# 5409057.net
KiCad netlist of a schematic drawn in EAGLE
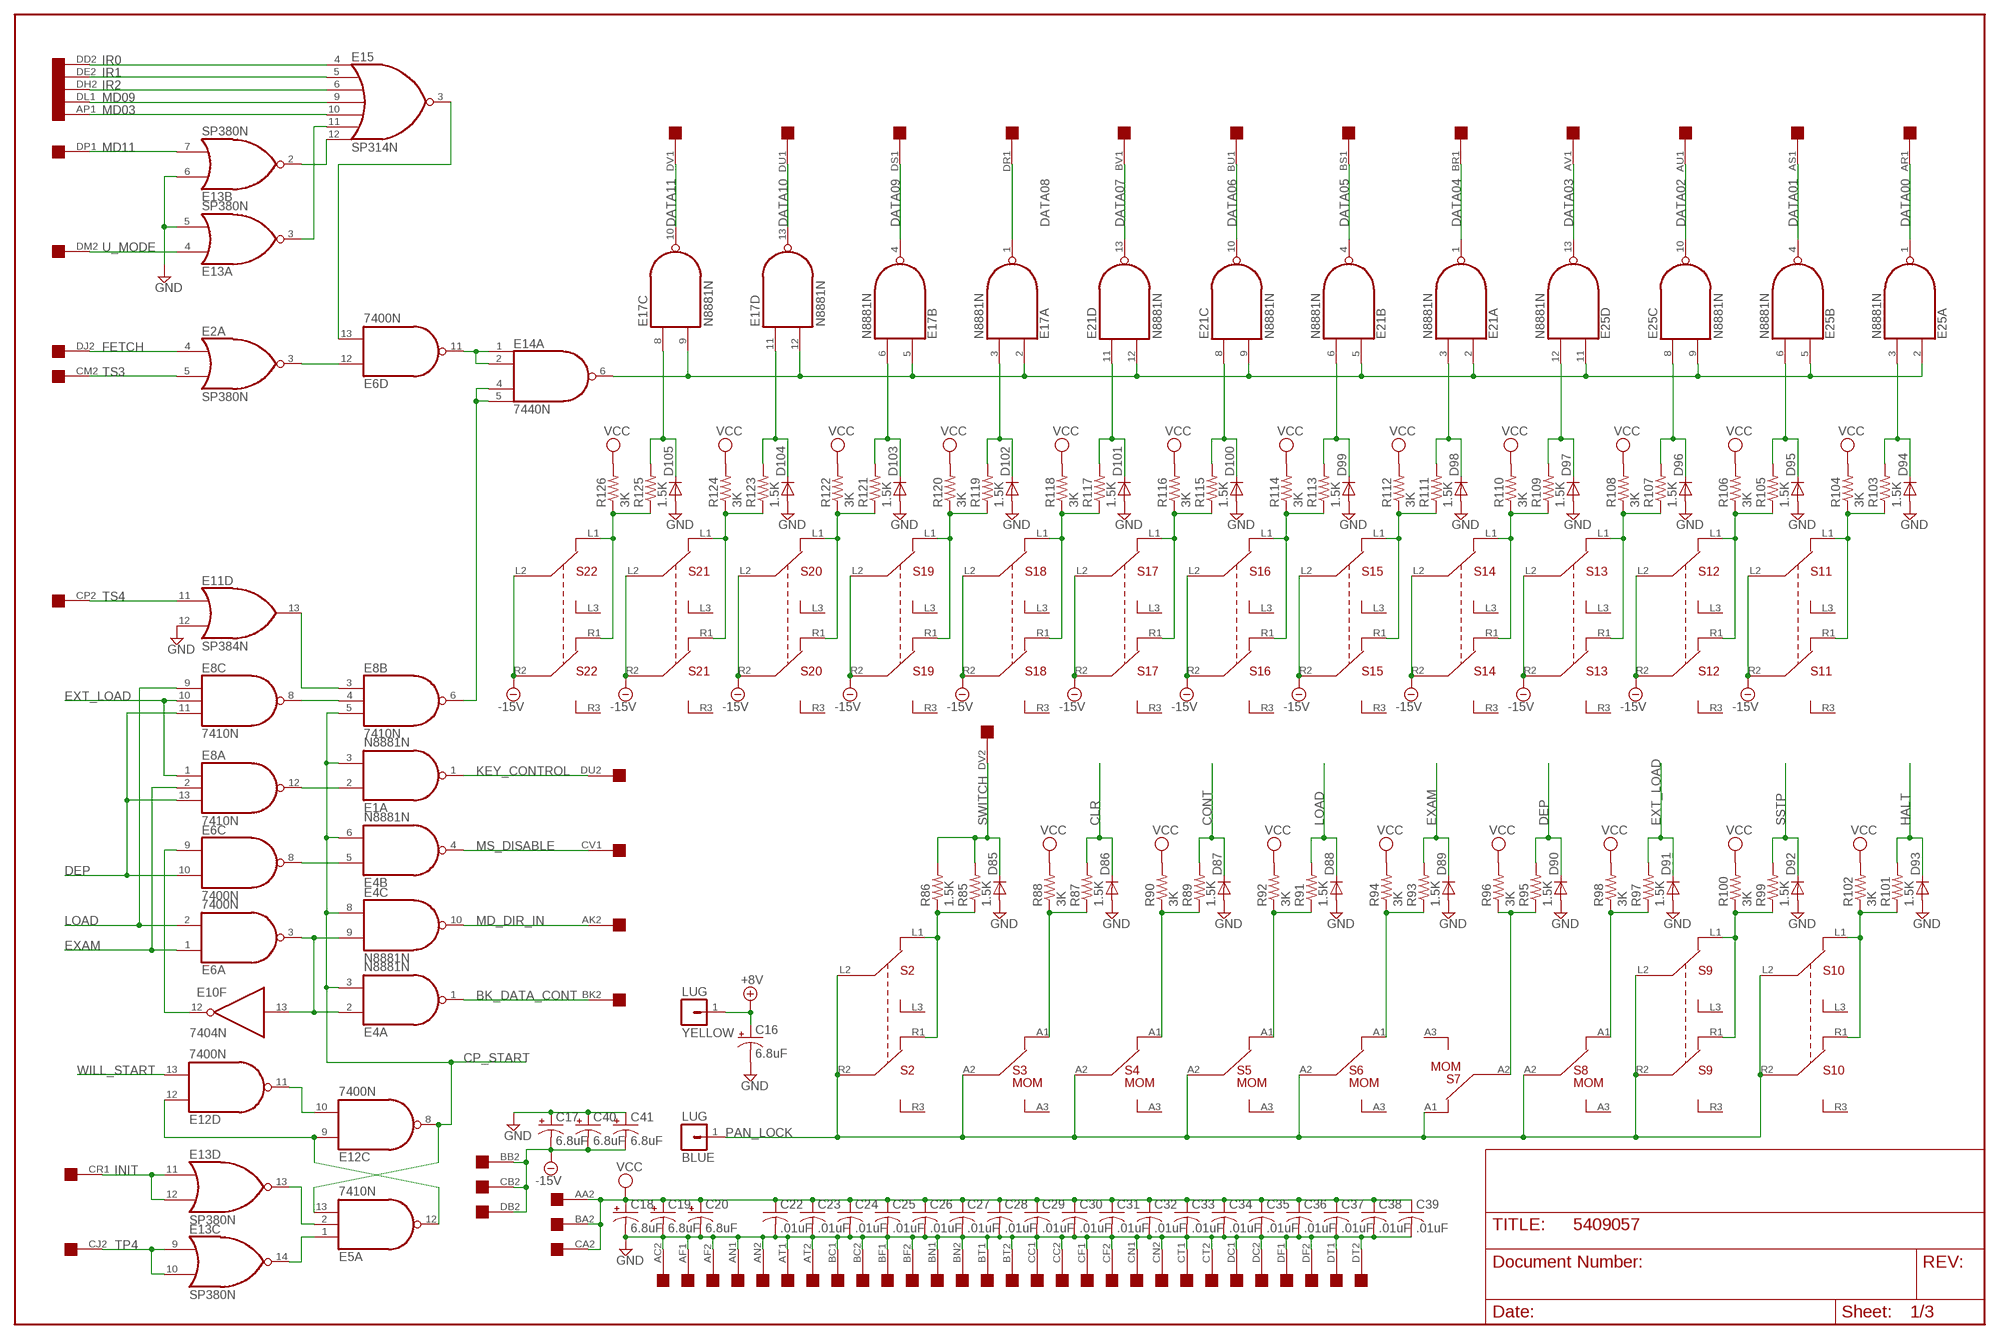
[diagram p0: schematic, sheet 1]
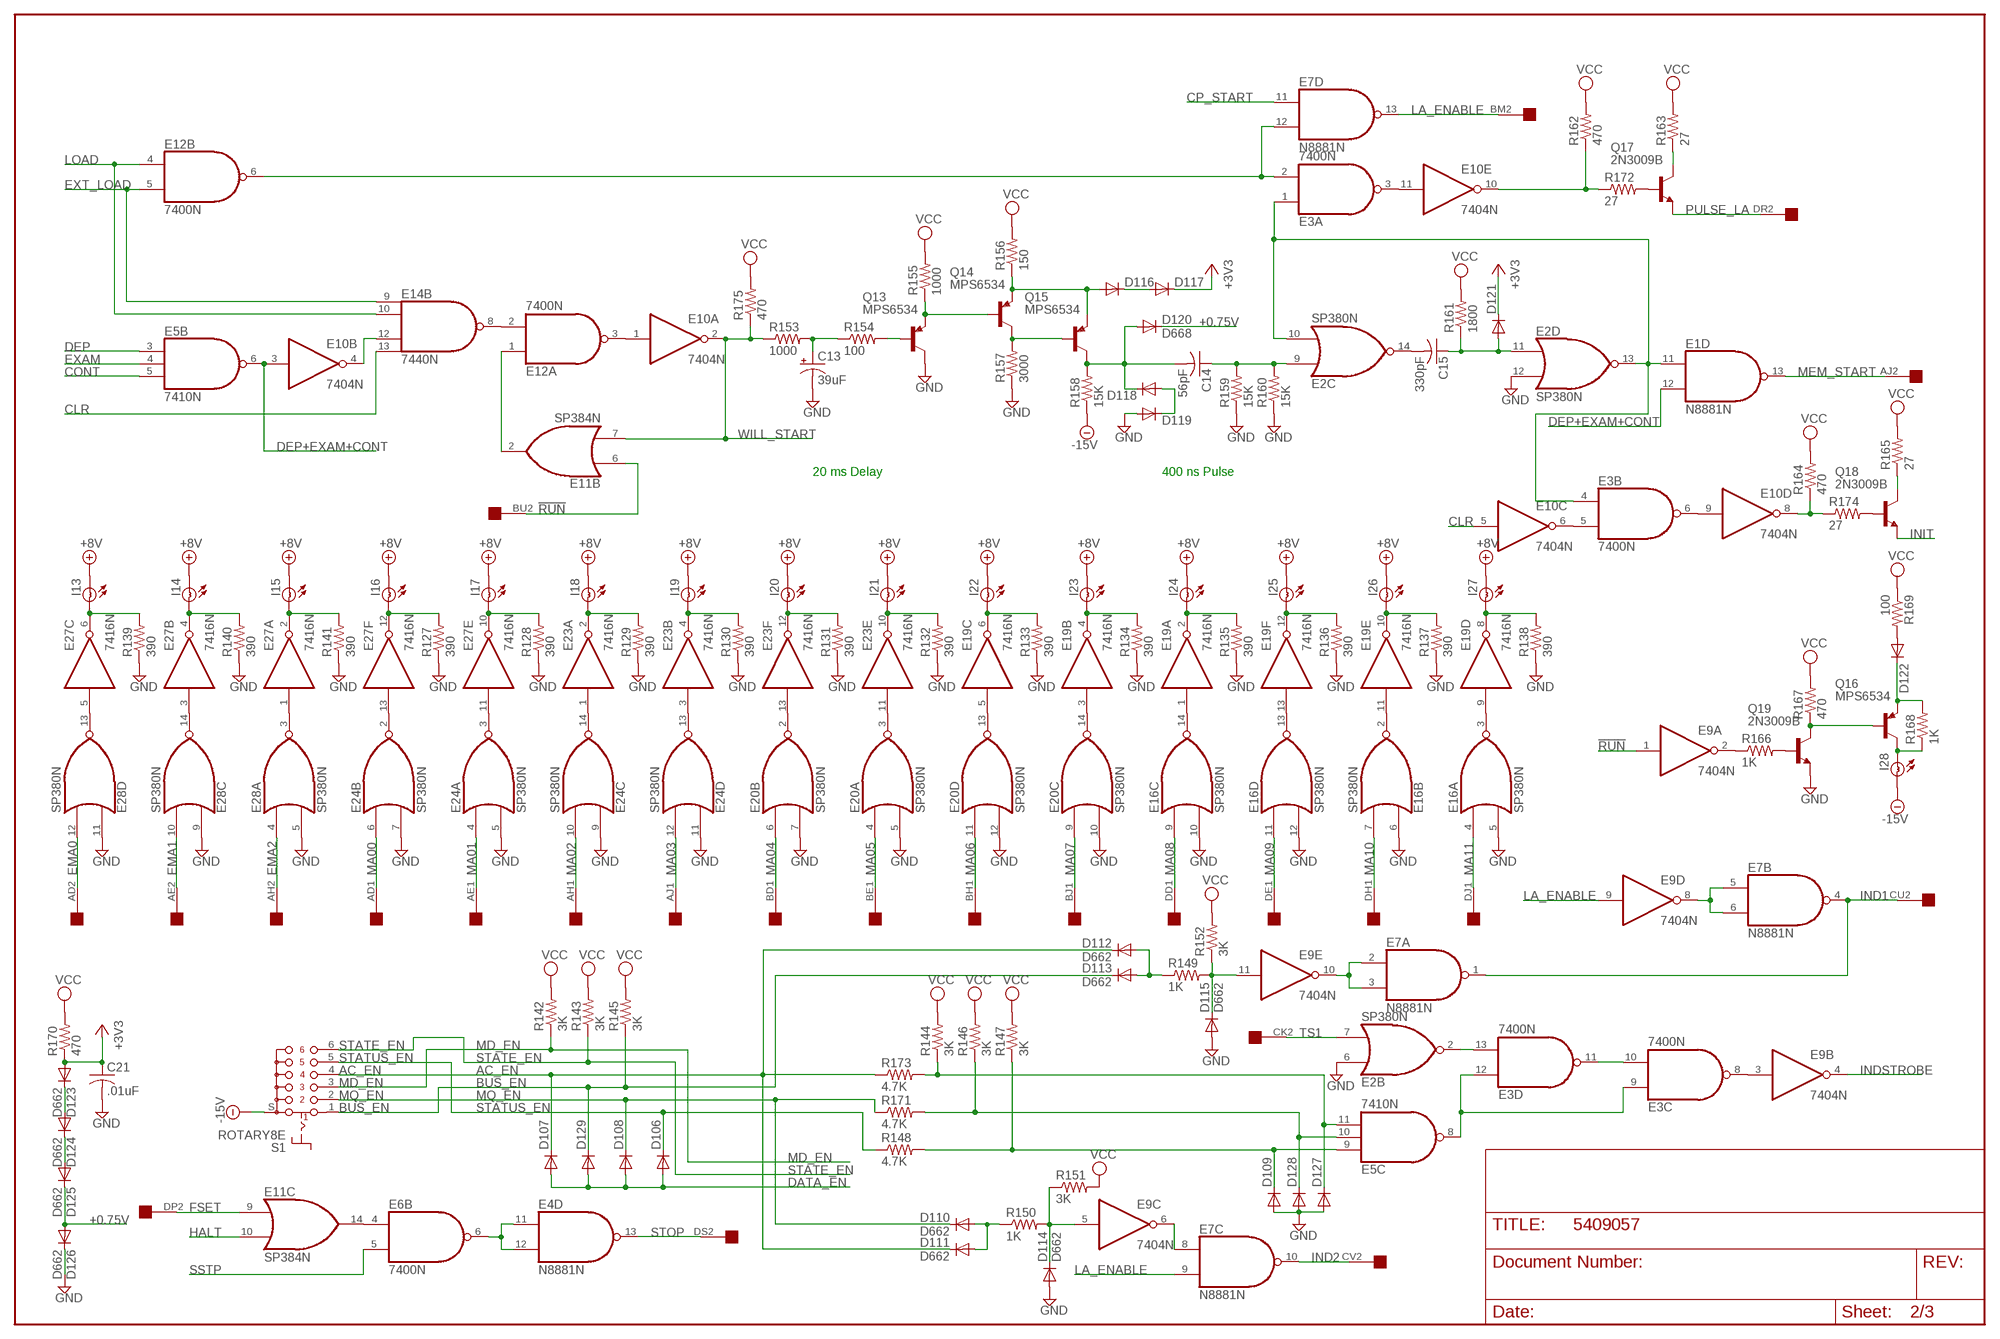
[diagram p1: schematic, sheet 2]
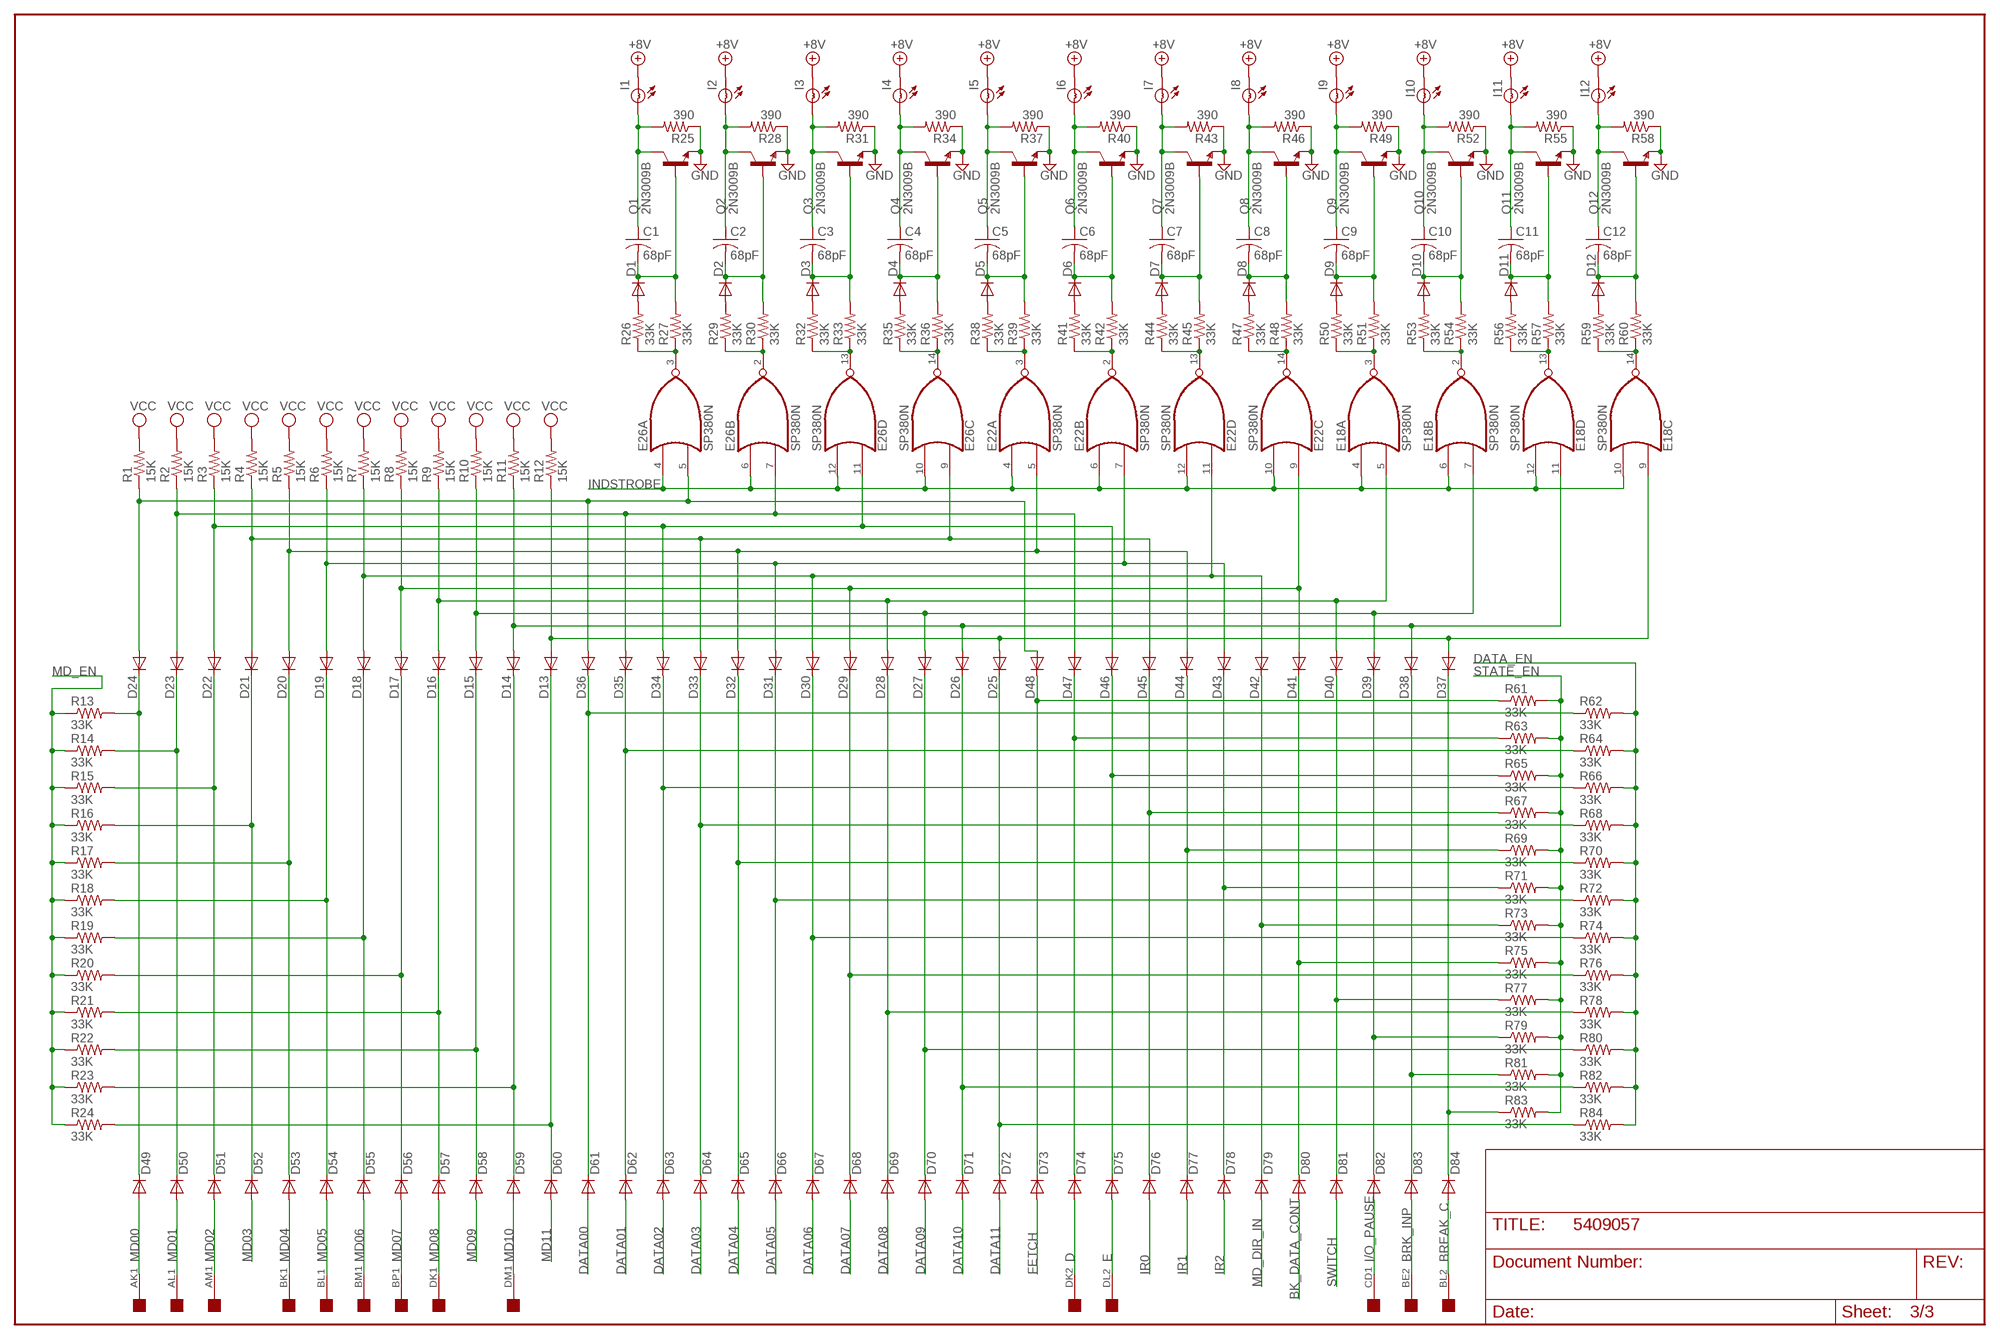
[diagram p2: schematic, sheet 3]

(export (version "E")
  (design (tool "Eeschema 10.0.6"))
  (components
    (comp (ref "C1")
      (value "68pF")
      (footprint "eagle-import:C050-025X075")
      (libsource (lib "eagle-import") (part "C-US050-025X075"))
    )
    (comp (ref "C2")
      (value "68pF")
      (footprint "eagle-import:C050-025X075")
      (libsource (lib "eagle-import") (part "C-US050-025X075"))
    )
    (comp (ref "C3")
      (value "68pF")
      (footprint "eagle-import:C050-025X075")
      (libsource (lib "eagle-import") (part "C-US050-025X075"))
    )
    (comp (ref "C4")
      (value "68pF")
      (footprint "eagle-import:C050-025X075")
      (libsource (lib "eagle-import") (part "C-US050-025X075"))
    )
    (comp (ref "C5")
      (value "68pF")
      (footprint "eagle-import:C050-025X075")
      (libsource (lib "eagle-import") (part "C-US050-025X075"))
    )
    (comp (ref "C6")
      (value "68pF")
      (footprint "eagle-import:C050-025X075")
      (libsource (lib "eagle-import") (part "C-US050-025X075"))
    )
    (comp (ref "C7")
      (value "68pF")
      (footprint "eagle-import:C050-025X075")
      (libsource (lib "eagle-import") (part "C-US050-025X075"))
    )
    (comp (ref "C8")
      (value "68pF")
      (footprint "eagle-import:C050-025X075")
      (libsource (lib "eagle-import") (part "C-US050-025X075"))
    )
    (comp (ref "C9")
      (value "68pF")
      (footprint "eagle-import:C050-025X075")
      (libsource (lib "eagle-import") (part "C-US050-025X075"))
    )
    (comp (ref "C10")
      (value "68pF")
      (footprint "eagle-import:C050-025X075")
      (libsource (lib "eagle-import") (part "C-US050-025X075"))
    )
    (comp (ref "C11")
      (value "68pF")
      (footprint "eagle-import:C050-025X075")
      (libsource (lib "eagle-import") (part "C-US050-025X075"))
    )
    (comp (ref "C12")
      (value "68pF")
      (footprint "eagle-import:C050-025X075")
      (libsource (lib "eagle-import") (part "C-US050-025X075"))
    )
    (comp (ref "D1")
      (value "1N4148")
      (footprint "eagle-import:DO35-10")
      (libsource (lib "eagle-import") (part "1N4148"))
    )
    (comp (ref "D2")
      (value "1N4148")
      (footprint "eagle-import:DO35-10")
      (libsource (lib "eagle-import") (part "1N4148"))
    )
    (comp (ref "D3")
      (value "1N4148")
      (footprint "eagle-import:DO35-10")
      (libsource (lib "eagle-import") (part "1N4148"))
    )
    (comp (ref "D4")
      (value "1N4148")
      (footprint "eagle-import:DO35-10")
      (libsource (lib "eagle-import") (part "1N4148"))
    )
    (comp (ref "D5")
      (value "1N4148")
      (footprint "eagle-import:DO35-10")
      (libsource (lib "eagle-import") (part "1N4148"))
    )
    (comp (ref "D6")
      (value "1N4148")
      (footprint "eagle-import:DO35-10")
      (libsource (lib "eagle-import") (part "1N4148"))
    )
    (comp (ref "D7")
      (value "1N4148")
      (footprint "eagle-import:DO35-10")
      (libsource (lib "eagle-import") (part "1N4148"))
    )
    (comp (ref "D8")
      (value "1N4148")
      (footprint "eagle-import:DO35-10")
      (libsource (lib "eagle-import") (part "1N4148"))
    )
    (comp (ref "D9")
      (value "1N4148")
      (footprint "eagle-import:DO35-10")
      (libsource (lib "eagle-import") (part "1N4148"))
    )
    (comp (ref "D10")
      (value "1N4148")
      (footprint "eagle-import:DO35-10")
      (libsource (lib "eagle-import") (part "1N4148"))
    )
    (comp (ref "D11")
      (value "1N4148")
      (footprint "eagle-import:DO35-10")
      (libsource (lib "eagle-import") (part "1N4148"))
    )
    (comp (ref "D12")
      (value "1N4148")
      (footprint "eagle-import:DO35-10")
      (libsource (lib "eagle-import") (part "1N4148"))
    )
    (comp (ref "D13")
      (value "1N4148")
      (footprint "eagle-import:DO35-10")
      (libsource (lib "eagle-import") (part "1N4148"))
    )
    (comp (ref "D14")
      (value "1N4148")
      (footprint "eagle-import:DO35-10")
      (libsource (lib "eagle-import") (part "1N4148"))
    )
    (comp (ref "D15")
      (value "1N4148")
      (footprint "eagle-import:DO35-10")
      (libsource (lib "eagle-import") (part "1N4148"))
    )
    (comp (ref "D16")
      (value "1N4148")
      (footprint "eagle-import:DO35-10")
      (libsource (lib "eagle-import") (part "1N4148"))
    )
    (comp (ref "D17")
      (value "1N4148")
      (footprint "eagle-import:DO35-10")
      (libsource (lib "eagle-import") (part "1N4148"))
    )
    (comp (ref "D18")
      (value "1N4148")
      (footprint "eagle-import:DO35-10")
      (libsource (lib "eagle-import") (part "1N4148"))
    )
    (comp (ref "D19")
      (value "1N4148")
      (footprint "eagle-import:DO35-10")
      (libsource (lib "eagle-import") (part "1N4148"))
    )
    (comp (ref "D20")
      (value "1N4148")
      (footprint "eagle-import:DO35-10")
      (libsource (lib "eagle-import") (part "1N4148"))
    )
    (comp (ref "D21")
      (value "1N4148")
      (footprint "eagle-import:DO35-10")
      (libsource (lib "eagle-import") (part "1N4148"))
    )
    (comp (ref "D22")
      (value "1N4148")
      (footprint "eagle-import:DO35-10")
      (libsource (lib "eagle-import") (part "1N4148"))
    )
    (comp (ref "D23")
      (value "1N4148")
      (footprint "eagle-import:DO35-10")
      (libsource (lib "eagle-import") (part "1N4148"))
    )
    (comp (ref "D24")
      (value "1N4148")
      (footprint "eagle-import:DO35-10")
      (libsource (lib "eagle-import") (part "1N4148"))
    )
    (comp (ref "D25")
      (value "1N4148")
      (footprint "eagle-import:DO35-10")
      (libsource (lib "eagle-import") (part "1N4148"))
    )
    (comp (ref "D26")
      (value "1N4148")
      (footprint "eagle-import:DO35-10")
      (libsource (lib "eagle-import") (part "1N4148"))
    )
    (comp (ref "D27")
      (value "1N4148")
      (footprint "eagle-import:DO35-10")
      (libsource (lib "eagle-import") (part "1N4148"))
    )
    (comp (ref "D28")
      (value "1N4148")
      (footprint "eagle-import:DO35-10")
      (libsource (lib "eagle-import") (part "1N4148"))
    )
    (comp (ref "D29")
      (value "1N4148")
      (footprint "eagle-import:DO35-10")
      (libsource (lib "eagle-import") (part "1N4148"))
    )
    (comp (ref "D30")
      (value "1N4148")
      (footprint "eagle-import:DO35-10")
      (libsource (lib "eagle-import") (part "1N4148"))
    )
    (comp (ref "D31")
      (value "1N4148")
      (footprint "eagle-import:DO35-10")
      (libsource (lib "eagle-import") (part "1N4148"))
    )
    (comp (ref "D32")
      (value "1N4148")
      (footprint "eagle-import:DO35-10")
      (libsource (lib "eagle-import") (part "1N4148"))
    )
    (comp (ref "D33")
      (value "1N4148")
      (footprint "eagle-import:DO35-10")
      (libsource (lib "eagle-import") (part "1N4148"))
    )
    (comp (ref "D34")
      (value "1N4148")
      (footprint "eagle-import:DO35-10")
      (libsource (lib "eagle-import") (part "1N4148"))
    )
    (comp (ref "D35")
      (value "1N4148")
      (footprint "eagle-import:DO35-10")
      (libsource (lib "eagle-import") (part "1N4148"))
    )
    (comp (ref "D36")
      (value "1N4148")
      (footprint "eagle-import:DO35-10")
      (libsource (lib "eagle-import") (part "1N4148"))
    )
    (comp (ref "D37")
      (value "1N4148")
      (footprint "eagle-import:DO35-10")
      (libsource (lib "eagle-import") (part "1N4148"))
    )
    (comp (ref "D38")
      (value "1N4148")
      (footprint "eagle-import:DO35-10")
      (libsource (lib "eagle-import") (part "1N4148"))
    )
    (comp (ref "D39")
      (value "1N4148")
      (footprint "eagle-import:DO35-10")
      (libsource (lib "eagle-import") (part "1N4148"))
    )
    (comp (ref "D40")
      (value "1N4148")
      (footprint "eagle-import:DO35-10")
      (libsource (lib "eagle-import") (part "1N4148"))
    )
    (comp (ref "D41")
      (value "1N4148")
      (footprint "eagle-import:DO35-10")
      (libsource (lib "eagle-import") (part "1N4148"))
    )
    (comp (ref "D42")
      (value "1N4148")
      (footprint "eagle-import:DO35-10")
      (libsource (lib "eagle-import") (part "1N4148"))
    )
    (comp (ref "D43")
      (value "1N4148")
      (footprint "eagle-import:DO35-10")
      (libsource (lib "eagle-import") (part "1N4148"))
    )
    (comp (ref "D44")
      (value "1N4148")
      (footprint "eagle-import:DO35-10")
      (libsource (lib "eagle-import") (part "1N4148"))
    )
    (comp (ref "D45")
      (value "1N4148")
      (footprint "eagle-import:DO35-10")
      (libsource (lib "eagle-import") (part "1N4148"))
    )
    (comp (ref "D46")
      (value "1N4148")
      (footprint "eagle-import:DO35-10")
      (libsource (lib "eagle-import") (part "1N4148"))
    )
    (comp (ref "D47")
      (value "1N4148")
      (footprint "eagle-import:DO35-10")
      (libsource (lib "eagle-import") (part "1N4148"))
    )
    (comp (ref "D48")
      (value "1N4148")
      (footprint "eagle-import:DO35-10")
      (libsource (lib "eagle-import") (part "1N4148"))
    )
    (comp (ref "D49")
      (value "1N4148")
      (footprint "eagle-import:DO35-10")
      (libsource (lib "eagle-import") (part "1N4148"))
    )
    (comp (ref "D50")
      (value "1N4148")
      (footprint "eagle-import:DO35-10")
      (libsource (lib "eagle-import") (part "1N4148"))
    )
    (comp (ref "D51")
      (value "1N4148")
      (footprint "eagle-import:DO35-10")
      (libsource (lib "eagle-import") (part "1N4148"))
    )
    (comp (ref "D52")
      (value "1N4148")
      (footprint "eagle-import:DO35-10")
      (libsource (lib "eagle-import") (part "1N4148"))
    )
    (comp (ref "D53")
      (value "1N4148")
      (footprint "eagle-import:DO35-10")
      (libsource (lib "eagle-import") (part "1N4148"))
    )
    (comp (ref "D54")
      (value "1N4148")
      (footprint "eagle-import:DO35-10")
      (libsource (lib "eagle-import") (part "1N4148"))
    )
    (comp (ref "D55")
      (value "1N4148")
      (footprint "eagle-import:DO35-10")
      (libsource (lib "eagle-import") (part "1N4148"))
    )
    (comp (ref "D56")
      (value "1N4148")
      (footprint "eagle-import:DO35-10")
      (libsource (lib "eagle-import") (part "1N4148"))
    )
    (comp (ref "D57")
      (value "1N4148")
      (footprint "eagle-import:DO35-10")
      (libsource (lib "eagle-import") (part "1N4148"))
    )
    (comp (ref "D58")
      (value "1N4148")
      (footprint "eagle-import:DO35-10")
      (libsource (lib "eagle-import") (part "1N4148"))
    )
    (comp (ref "D59")
      (value "1N4148")
      (footprint "eagle-import:DO35-10")
      (libsource (lib "eagle-import") (part "1N4148"))
    )
    (comp (ref "D60")
      (value "1N4148")
      (footprint "eagle-import:DO35-10")
      (libsource (lib "eagle-import") (part "1N4148"))
    )
    (comp (ref "D61")
      (value "1N4148")
      (footprint "eagle-import:DO35-10")
      (libsource (lib "eagle-import") (part "1N4148"))
    )
    (comp (ref "D62")
      (value "1N4148")
      (footprint "eagle-import:DO35-10")
      (libsource (lib "eagle-import") (part "1N4148"))
    )
    (comp (ref "D63")
      (value "1N4148")
      (footprint "eagle-import:DO35-10")
      (libsource (lib "eagle-import") (part "1N4148"))
    )
    (comp (ref "D64")
      (value "1N4148")
      (footprint "eagle-import:DO35-10")
      (libsource (lib "eagle-import") (part "1N4148"))
    )
    (comp (ref "D65")
      (value "1N4148")
      (footprint "eagle-import:DO35-10")
      (libsource (lib "eagle-import") (part "1N4148"))
    )
    (comp (ref "D66")
      (value "1N4148")
      (footprint "eagle-import:DO35-10")
      (libsource (lib "eagle-import") (part "1N4148"))
    )
    (comp (ref "D67")
      (value "1N4148")
      (footprint "eagle-import:DO35-10")
      (libsource (lib "eagle-import") (part "1N4148"))
    )
    (comp (ref "D68")
      (value "1N4148")
      (footprint "eagle-import:DO35-10")
      (libsource (lib "eagle-import") (part "1N4148"))
    )
    (comp (ref "D69")
      (value "1N4148")
      (footprint "eagle-import:DO35-10")
      (libsource (lib "eagle-import") (part "1N4148"))
    )
    (comp (ref "D70")
      (value "1N4148")
      (footprint "eagle-import:DO35-10")
      (libsource (lib "eagle-import") (part "1N4148"))
    )
    (comp (ref "D71")
      (value "1N4148")
      (footprint "eagle-import:DO35-10")
      (libsource (lib "eagle-import") (part "1N4148"))
    )
    (comp (ref "D72")
      (value "1N4148")
      (footprint "eagle-import:DO35-10")
      (libsource (lib "eagle-import") (part "1N4148"))
    )
    (comp (ref "D73")
      (value "1N4148")
      (footprint "eagle-import:DO35-10")
      (libsource (lib "eagle-import") (part "1N4148"))
    )
    (comp (ref "D74")
      (value "1N4148")
      (footprint "eagle-import:DO35-10")
      (libsource (lib "eagle-import") (part "1N4148"))
    )
    (comp (ref "D75")
      (value "1N4148")
      (footprint "eagle-import:DO35-10")
      (libsource (lib "eagle-import") (part "1N4148"))
    )
    (comp (ref "D76")
      (value "1N4148")
      (footprint "eagle-import:DO35-10")
      (libsource (lib "eagle-import") (part "1N4148"))
    )
    (comp (ref "D77")
      (value "1N4148")
      (footprint "eagle-import:DO35-10")
      (libsource (lib "eagle-import") (part "1N4148"))
    )
    (comp (ref "D78")
      (value "1N4148")
      (footprint "eagle-import:DO35-10")
      (libsource (lib "eagle-import") (part "1N4148"))
    )
    (comp (ref "D79")
      (value "1N4148")
      (footprint "eagle-import:DO35-10")
      (libsource (lib "eagle-import") (part "1N4148"))
    )
    (comp (ref "D80")
      (value "1N4148")
      (footprint "eagle-import:DO35-10")
      (libsource (lib "eagle-import") (part "1N4148"))
    )
    (comp (ref "D81")
      (value "1N4148")
      (footprint "eagle-import:DO35-10")
      (libsource (lib "eagle-import") (part "1N4148"))
    )
    (comp (ref "D82")
      (value "1N4148")
      (footprint "eagle-import:DO35-10")
      (libsource (lib "eagle-import") (part "1N4148"))
    )
    (comp (ref "D83")
      (value "1N4148")
      (footprint "eagle-import:DO35-10")
      (libsource (lib "eagle-import") (part "1N4148"))
    )
    (comp (ref "D84")
      (value "1N4148")
      (footprint "eagle-import:DO35-10")
      (libsource (lib "eagle-import") (part "1N4148"))
    )
    (comp (ref "E18")
      (value "SP380N")
      (footprint "eagle-import:DIL14")
      (libsource (lib "eagle-import") (part "SP380N"))
    )
    (comp (ref "E22")
      (value "SP380N")
      (footprint "eagle-import:DIL14")
      (libsource (lib "eagle-import") (part "SP380N"))
    )
    (comp (ref "E26")
      (value "SP380N")
      (footprint "eagle-import:DIL14")
      (libsource (lib "eagle-import") (part "SP380N"))
    )
    (comp (ref "I1")
      (value "BULB")
      (footprint "eagle-import:BULB")
      (libsource (lib "eagle-import") (part "BULB"))
    )
    (comp (ref "I2")
      (value "BULB")
      (footprint "eagle-import:BULB")
      (libsource (lib "eagle-import") (part "BULB"))
    )
    (comp (ref "I3")
      (value "BULB")
      (footprint "eagle-import:BULB")
      (libsource (lib "eagle-import") (part "BULB"))
    )
    (comp (ref "I4")
      (value "BULB")
      (footprint "eagle-import:BULB")
      (libsource (lib "eagle-import") (part "BULB"))
    )
    (comp (ref "I5")
      (value "BULB")
      (footprint "eagle-import:BULB")
      (libsource (lib "eagle-import") (part "BULB"))
    )
    (comp (ref "I6")
      (value "BULB")
      (footprint "eagle-import:BULB")
      (libsource (lib "eagle-import") (part "BULB"))
    )
    (comp (ref "I7")
      (value "BULB")
      (footprint "eagle-import:BULB")
      (libsource (lib "eagle-import") (part "BULB"))
    )
    (comp (ref "I8")
      (value "BULB")
      (footprint "eagle-import:BULB")
      (libsource (lib "eagle-import") (part "BULB"))
    )
    (comp (ref "I9")
      (value "BULB")
      (footprint "eagle-import:BULB")
      (libsource (lib "eagle-import") (part "BULB"))
    )
    (comp (ref "I10")
      (value "BULB")
      (footprint "eagle-import:BULB")
      (libsource (lib "eagle-import") (part "BULB"))
    )
    (comp (ref "I11")
      (value "BULB")
      (footprint "eagle-import:BULB")
      (libsource (lib "eagle-import") (part "BULB"))
    )
    (comp (ref "I12")
      (value "BULB")
      (footprint "eagle-import:BULB")
      (libsource (lib "eagle-import") (part "BULB"))
    )
    (comp (ref "Q1")
      (value "2N3009B")
      (footprint "eagle-import:TO39")
      (libsource (lib "eagle-import") (part "2N3019"))
    )
    (comp (ref "Q2")
      (value "2N3009B")
      (footprint "eagle-import:TO39")
      (libsource (lib "eagle-import") (part "2N3019"))
    )
    (comp (ref "Q3")
      (value "2N3009B")
      (footprint "eagle-import:TO39")
      (libsource (lib "eagle-import") (part "2N3019"))
    )
    (comp (ref "Q4")
      (value "2N3009B")
      (footprint "eagle-import:TO39")
      (libsource (lib "eagle-import") (part "2N3019"))
    )
    (comp (ref "Q5")
      (value "2N3009B")
      (footprint "eagle-import:TO39")
      (libsource (lib "eagle-import") (part "2N3019"))
    )
    (comp (ref "Q6")
      (value "2N3009B")
      (footprint "eagle-import:TO39")
      (libsource (lib "eagle-import") (part "2N3019"))
    )
    (comp (ref "Q7")
      (value "2N3009B")
      (footprint "eagle-import:TO39")
      (libsource (lib "eagle-import") (part "2N3019"))
    )
    (comp (ref "Q8")
      (value "2N3009B")
      (footprint "eagle-import:TO39")
      (libsource (lib "eagle-import") (part "2N3019"))
    )
    (comp (ref "Q9")
      (value "2N3009B")
      (footprint "eagle-import:TO39")
      (libsource (lib "eagle-import") (part "2N3019"))
    )
    (comp (ref "Q10")
      (value "2N3009B")
      (footprint "eagle-import:TO39")
      (libsource (lib "eagle-import") (part "2N3019"))
    )
    (comp (ref "Q11")
      (value "2N3009B")
      (footprint "eagle-import:TO39")
      (libsource (lib "eagle-import") (part "2N3019"))
    )
    (comp (ref "Q12")
      (value "2N3009B")
      (footprint "eagle-import:TO39")
      (libsource (lib "eagle-import") (part "2N3019"))
    )
    (comp (ref "R1")
      (value "15K")
      (footprint "eagle-import:0207_10")
      (libsource (lib "eagle-import") (part "R-US_0207/10"))
    )
    (comp (ref "R2")
      (value "15K")
      (footprint "eagle-import:0207_10")
      (libsource (lib "eagle-import") (part "R-US_0207/10"))
    )
    (comp (ref "R3")
      (value "15K")
      (footprint "eagle-import:0207_10")
      (libsource (lib "eagle-import") (part "R-US_0207/10"))
    )
    (comp (ref "R4")
      (value "15K")
      (footprint "eagle-import:0207_10")
      (libsource (lib "eagle-import") (part "R-US_0207/10"))
    )
    (comp (ref "R5")
      (value "15K")
      (footprint "eagle-import:0207_10")
      (libsource (lib "eagle-import") (part "R-US_0207/10"))
    )
    (comp (ref "R6")
      (value "15K")
      (footprint "eagle-import:0207_10")
      (libsource (lib "eagle-import") (part "R-US_0207/10"))
    )
    (comp (ref "R7")
      (value "15K")
      (footprint "eagle-import:0207_10")
      (libsource (lib "eagle-import") (part "R-US_0207/10"))
    )
    (comp (ref "R8")
      (value "15K")
      (footprint "eagle-import:0207_10")
      (libsource (lib "eagle-import") (part "R-US_0207/10"))
    )
    (comp (ref "R9")
      (value "15K")
      (footprint "eagle-import:0207_10")
      (libsource (lib "eagle-import") (part "R-US_0207/10"))
    )
    (comp (ref "R10")
      (value "15K")
      (footprint "eagle-import:0207_10")
      (libsource (lib "eagle-import") (part "R-US_0207/10"))
    )
    (comp (ref "R11")
      (value "15K")
      (footprint "eagle-import:0207_10")
      (libsource (lib "eagle-import") (part "R-US_0207/10"))
    )
    (comp (ref "R12")
      (value "15K")
      (footprint "eagle-import:0207_10")
      (libsource (lib "eagle-import") (part "R-US_0207/10"))
    )
    (comp (ref "R13")
      (value "33K")
      (footprint "eagle-import:0207_10")
      (libsource (lib "eagle-import") (part "R-US_0207/10"))
    )
    (comp (ref "R14")
      (value "33K")
      (footprint "eagle-import:0207_10")
      (libsource (lib "eagle-import") (part "R-US_0207/10"))
    )
    (comp (ref "R15")
      (value "33K")
      (footprint "eagle-import:0207_10")
      (libsource (lib "eagle-import") (part "R-US_0207/10"))
    )
    (comp (ref "R16")
      (value "33K")
      (footprint "eagle-import:0207_10")
      (libsource (lib "eagle-import") (part "R-US_0207/10"))
    )
    (comp (ref "R17")
      (value "33K")
      (footprint "eagle-import:0207_10")
      (libsource (lib "eagle-import") (part "R-US_0207/10"))
    )
    (comp (ref "R18")
      (value "33K")
      (footprint "eagle-import:0207_10")
      (libsource (lib "eagle-import") (part "R-US_0207/10"))
    )
    (comp (ref "R19")
      (value "33K")
      (footprint "eagle-import:0207_10")
      (libsource (lib "eagle-import") (part "R-US_0207/10"))
    )
    (comp (ref "R20")
      (value "33K")
      (footprint "eagle-import:0207_10")
      (libsource (lib "eagle-import") (part "R-US_0207/10"))
    )
    (comp (ref "R21")
      (value "33K")
      (footprint "eagle-import:0207_10")
      (libsource (lib "eagle-import") (part "R-US_0207/10"))
    )
    (comp (ref "R22")
      (value "33K")
      (footprint "eagle-import:0207_10")
      (libsource (lib "eagle-import") (part "R-US_0207/10"))
    )
    (comp (ref "R23")
      (value "33K")
      (footprint "eagle-import:0207_10")
      (libsource (lib "eagle-import") (part "R-US_0207/10"))
    )
    (comp (ref "R24")
      (value "33K")
      (footprint "eagle-import:0207_10")
      (libsource (lib "eagle-import") (part "R-US_0207/10"))
    )
    (comp (ref "R25")
      (value "390")
      (footprint "eagle-import:0207_10")
      (libsource (lib "eagle-import") (part "R-US_0207/10"))
    )
    (comp (ref "R26")
      (value "33K")
      (footprint "eagle-import:0207_10")
      (libsource (lib "eagle-import") (part "R-US_0207/10"))
    )
    (comp (ref "R27")
      (value "33K")
      (footprint "eagle-import:0207_10")
      (libsource (lib "eagle-import") (part "R-US_0207/10"))
    )
    (comp (ref "R28")
      (value "390")
      (footprint "eagle-import:0207_10")
      (libsource (lib "eagle-import") (part "R-US_0207/10"))
    )
    (comp (ref "R29")
      (value "33K")
      (footprint "eagle-import:0207_10")
      (libsource (lib "eagle-import") (part "R-US_0207/10"))
    )
    (comp (ref "R30")
      (value "33K")
      (footprint "eagle-import:0207_10")
      (libsource (lib "eagle-import") (part "R-US_0207/10"))
    )
    (comp (ref "R31")
      (value "390")
      (footprint "eagle-import:0207_10")
      (libsource (lib "eagle-import") (part "R-US_0207/10"))
    )
    (comp (ref "R32")
      (value "33K")
      (footprint "eagle-import:0207_10")
      (libsource (lib "eagle-import") (part "R-US_0207/10"))
    )
    (comp (ref "R33")
      (value "33K")
      (footprint "eagle-import:0207_10")
      (libsource (lib "eagle-import") (part "R-US_0207/10"))
    )
    (comp (ref "R34")
      (value "390")
      (footprint "eagle-import:0207_10")
      (libsource (lib "eagle-import") (part "R-US_0207/10"))
    )
    (comp (ref "R35")
      (value "33K")
      (footprint "eagle-import:0207_10")
      (libsource (lib "eagle-import") (part "R-US_0207/10"))
    )
    (comp (ref "R36")
      (value "33K")
      (footprint "eagle-import:0207_10")
      (libsource (lib "eagle-import") (part "R-US_0207/10"))
    )
    (comp (ref "R37")
      (value "390")
      (footprint "eagle-import:0207_10")
      (libsource (lib "eagle-import") (part "R-US_0207/10"))
    )
    (comp (ref "R38")
      (value "33K")
      (footprint "eagle-import:0207_10")
      (libsource (lib "eagle-import") (part "R-US_0207/10"))
    )
    (comp (ref "R39")
      (value "33K")
      (footprint "eagle-import:0207_10")
      (libsource (lib "eagle-import") (part "R-US_0207/10"))
    )
    (comp (ref "R40")
      (value "390")
      (footprint "eagle-import:0207_10")
      (libsource (lib "eagle-import") (part "R-US_0207/10"))
    )
    (comp (ref "R41")
      (value "33K")
      (footprint "eagle-import:0207_10")
      (libsource (lib "eagle-import") (part "R-US_0207/10"))
    )
    (comp (ref "R42")
      (value "33K")
      (footprint "eagle-import:0207_10")
      (libsource (lib "eagle-import") (part "R-US_0207/10"))
    )
    (comp (ref "R43")
      (value "390")
      (footprint "eagle-import:0207_10")
      (libsource (lib "eagle-import") (part "R-US_0207/10"))
    )
    (comp (ref "R44")
      (value "33K")
      (footprint "eagle-import:0207_10")
      (libsource (lib "eagle-import") (part "R-US_0207/10"))
    )
    (comp (ref "R45")
      (value "33K")
      (footprint "eagle-import:0207_10")
      (libsource (lib "eagle-import") (part "R-US_0207/10"))
    )
    (comp (ref "R46")
      (value "390")
      (footprint "eagle-import:0207_10")
      (libsource (lib "eagle-import") (part "R-US_0207/10"))
    )
    (comp (ref "R47")
      (value "33K")
      (footprint "eagle-import:0207_10")
      (libsource (lib "eagle-import") (part "R-US_0207/10"))
    )
    (comp (ref "R48")
      (value "33K")
      (footprint "eagle-import:0207_10")
      (libsource (lib "eagle-import") (part "R-US_0207/10"))
    )
    (comp (ref "R49")
      (value "390")
      (footprint "eagle-import:0207_10")
      (libsource (lib "eagle-import") (part "R-US_0207/10"))
    )
    (comp (ref "R50")
      (value "33K")
      (footprint "eagle-import:0207_10")
      (libsource (lib "eagle-import") (part "R-US_0207/10"))
    )
    (comp (ref "R51")
      (value "33K")
      (footprint "eagle-import:0207_10")
      (libsource (lib "eagle-import") (part "R-US_0207/10"))
    )
    (comp (ref "R52")
      (value "390")
      (footprint "eagle-import:0207_10")
      (libsource (lib "eagle-import") (part "R-US_0207/10"))
    )
    (comp (ref "R53")
      (value "33K")
      (footprint "eagle-import:0207_10")
      (libsource (lib "eagle-import") (part "R-US_0207/10"))
    )
    (comp (ref "R54")
      (value "33K")
      (footprint "eagle-import:0207_10")
      (libsource (lib "eagle-import") (part "R-US_0207/10"))
    )
    (comp (ref "R55")
      (value "390")
      (footprint "eagle-import:0207_10")
      (libsource (lib "eagle-import") (part "R-US_0207/10"))
    )
    (comp (ref "R56")
      (value "33K")
      (footprint "eagle-import:0207_10")
      (libsource (lib "eagle-import") (part "R-US_0207/10"))
    )
    (comp (ref "R57")
      (value "33K")
      (footprint "eagle-import:0207_10")
      (libsource (lib "eagle-import") (part "R-US_0207/10"))
    )
    (comp (ref "R58")
      (value "390")
      (footprint "eagle-import:0207_10")
      (libsource (lib "eagle-import") (part "R-US_0207/10"))
    )
    (comp (ref "R59")
      (value "33K")
      (footprint "eagle-import:0207_10")
      (libsource (lib "eagle-import") (part "R-US_0207/10"))
    )
    (comp (ref "R60")
      (value "33K")
      (footprint "eagle-import:0207_10")
      (libsource (lib "eagle-import") (part "R-US_0207/10"))
    )
    (comp (ref "R61")
      (value "33K")
      (footprint "eagle-import:0207_10")
      (libsource (lib "eagle-import") (part "R-US_0207/10"))
    )
    (comp (ref "R62")
      (value "33K")
      (footprint "eagle-import:0207_10")
      (libsource (lib "eagle-import") (part "R-US_0207/10"))
    )
    (comp (ref "R63")
      (value "33K")
      (footprint "eagle-import:0207_10")
      (libsource (lib "eagle-import") (part "R-US_0207/10"))
    )
    (comp (ref "R64")
      (value "33K")
      (footprint "eagle-import:0207_10")
      (libsource (lib "eagle-import") (part "R-US_0207/10"))
    )
    (comp (ref "R65")
      (value "33K")
      (footprint "eagle-import:0207_10")
      (libsource (lib "eagle-import") (part "R-US_0207/10"))
    )
    (comp (ref "R66")
      (value "33K")
      (footprint "eagle-import:0207_10")
      (libsource (lib "eagle-import") (part "R-US_0207/10"))
    )
    (comp (ref "R67")
      (value "33K")
      (footprint "eagle-import:0207_10")
      (libsource (lib "eagle-import") (part "R-US_0207/10"))
    )
    (comp (ref "R68")
      (value "33K")
      (footprint "eagle-import:0207_10")
      (libsource (lib "eagle-import") (part "R-US_0207/10"))
    )
    (comp (ref "R69")
      (value "33K")
      (footprint "eagle-import:0207_10")
      (libsource (lib "eagle-import") (part "R-US_0207/10"))
    )
    (comp (ref "R70")
      (value "33K")
      (footprint "eagle-import:0207_10")
      (libsource (lib "eagle-import") (part "R-US_0207/10"))
    )
    (comp (ref "R71")
      (value "33K")
      (footprint "eagle-import:0207_10")
      (libsource (lib "eagle-import") (part "R-US_0207/10"))
    )
    (comp (ref "R72")
      (value "33K")
      (footprint "eagle-import:0207_10")
      (libsource (lib "eagle-import") (part "R-US_0207/10"))
    )
    (comp (ref "R73")
      (value "33K")
      (footprint "eagle-import:0207_10")
      (libsource (lib "eagle-import") (part "R-US_0207/10"))
    )
    (comp (ref "R74")
      (value "33K")
      (footprint "eagle-import:0207_10")
      (libsource (lib "eagle-import") (part "R-US_0207/10"))
    )
    (comp (ref "R75")
      (value "33K")
      (footprint "eagle-import:0207_10")
      (libsource (lib "eagle-import") (part "R-US_0207/10"))
    )
    (comp (ref "R76")
      (value "33K")
      (footprint "eagle-import:0207_10")
      (libsource (lib "eagle-import") (part "R-US_0207/10"))
    )
    (comp (ref "R77")
      (value "33K")
      (footprint "eagle-import:0207_10")
      (libsource (lib "eagle-import") (part "R-US_0207/10"))
    )
    (comp (ref "R78")
      (value "33K")
      (footprint "eagle-import:0207_10")
      (libsource (lib "eagle-import") (part "R-US_0207/10"))
    )
    (comp (ref "R79")
      (value "33K")
      (footprint "eagle-import:0207_10")
      (libsource (lib "eagle-import") (part "R-US_0207/10"))
    )
    (comp (ref "R80")
      (value "33K")
      (footprint "eagle-import:0207_10")
      (libsource (lib "eagle-import") (part "R-US_0207/10"))
    )
    (comp (ref "R81")
      (value "33K")
      (footprint "eagle-import:0207_10")
      (libsource (lib "eagle-import") (part "R-US_0207/10"))
    )
    (comp (ref "R82")
      (value "33K")
      (footprint "eagle-import:0207_10")
      (libsource (lib "eagle-import") (part "R-US_0207/10"))
    )
    (comp (ref "R83")
      (value "33K")
      (footprint "eagle-import:0207_10")
      (libsource (lib "eagle-import") (part "R-US_0207/10"))
    )
    (comp (ref "R84")
      (value "33K")
      (footprint "eagle-import:0207_10")
      (libsource (lib "eagle-import") (part "R-US_0207/10"))
    )
    (comp (ref "U$2")
      (value "QUAD")
      (footprint "eagle-import:EDGE-CON8")
      (libsource (lib "eagle-import") (part "QUAD"))
    )
    (comp (ref "C13")
      (value "39uF")
      (footprint "eagle-import:E12-8")
      (libsource (lib "eagle-import") (part "CPOL-USE20-8AXIAL"))
    )
    (comp (ref "C14")
      (value "56pF")
      (footprint "eagle-import:C050-025X075")
      (libsource (lib "eagle-import") (part "C-US050-025X075"))
    )
    (comp (ref "C15")
      (value "330pF")
      (footprint "eagle-import:C050-025X075")
      (libsource (lib "eagle-import") (part "C-US050-025X075"))
    )
    (comp (ref "C21")
      (value ".01uF")
      (footprint "eagle-import:C050-025X075")
      (libsource (lib "eagle-import") (part "C-US050-025X075"))
    )
    (comp (ref "D106")
      (value "1N4148")
      (footprint "eagle-import:DO35-10")
      (libsource (lib "eagle-import") (part "1N4148"))
    )
    (comp (ref "D107")
      (value "1N4148")
      (footprint "eagle-import:DO35-10")
      (libsource (lib "eagle-import") (part "1N4148"))
    )
    (comp (ref "D108")
      (value "1N4148")
      (footprint "eagle-import:DO35-10")
      (libsource (lib "eagle-import") (part "1N4148"))
    )
    (comp (ref "D109")
      (value "1N4148")
      (footprint "eagle-import:DO35-10")
      (libsource (lib "eagle-import") (part "1N4148"))
    )
    (comp (ref "D110")
      (value "D662")
      (footprint "eagle-import:DO35-10")
      (libsource (lib "eagle-import") (part "1N4148"))
    )
    (comp (ref "D111")
      (value "D662")
      (footprint "eagle-import:DO35-10")
      (libsource (lib "eagle-import") (part "1N4148"))
    )
    (comp (ref "D112")
      (value "D662")
      (footprint "eagle-import:DO35-10")
      (libsource (lib "eagle-import") (part "1N4148"))
    )
    (comp (ref "D113")
      (value "D662")
      (footprint "eagle-import:DO35-10")
      (libsource (lib "eagle-import") (part "1N4148"))
    )
    (comp (ref "D114")
      (value "D662")
      (footprint "eagle-import:DO35-10")
      (libsource (lib "eagle-import") (part "1N4148"))
    )
    (comp (ref "D115")
      (value "D662")
      (footprint "eagle-import:DO35-10")
      (libsource (lib "eagle-import") (part "1N4148"))
    )
    (comp (ref "D116")
      (value "1N4148")
      (footprint "eagle-import:DO35-10")
      (libsource (lib "eagle-import") (part "1N4148"))
    )
    (comp (ref "D117")
      (value "1N4148")
      (footprint "eagle-import:DO35-10")
      (libsource (lib "eagle-import") (part "1N4148"))
    )
    (comp (ref "D118")
      (value "1N4148")
      (footprint "eagle-import:DO35-10")
      (libsource (lib "eagle-import") (part "1N4148"))
    )
    (comp (ref "D119")
      (value "1N4148")
      (footprint "eagle-import:DO35-10")
      (libsource (lib "eagle-import") (part "1N4148"))
    )
    (comp (ref "D120")
      (value "D668")
      (footprint "eagle-import:DO35-10")
      (libsource (lib "eagle-import") (part "1N4148"))
    )
    (comp (ref "D121")
      (value "1N4148")
      (footprint "eagle-import:DO35-10")
      (libsource (lib "eagle-import") (part "1N4148"))
    )
    (comp (ref "D122")
      (value "1N4148")
      (footprint "eagle-import:DO35-10")
      (libsource (lib "eagle-import") (part "1N4148"))
    )
    (comp (ref "D123")
      (value "D662")
      (footprint "eagle-import:DO35-10")
      (libsource (lib "eagle-import") (part "1N4148"))
    )
    (comp (ref "D124")
      (value "D662")
      (footprint "eagle-import:DO35-10")
      (libsource (lib "eagle-import") (part "1N4148"))
    )
    (comp (ref "D125")
      (value "D662")
      (footprint "eagle-import:DO35-10")
      (libsource (lib "eagle-import") (part "1N4148"))
    )
    (comp (ref "D126")
      (value "D662")
      (footprint "eagle-import:DO35-10")
      (libsource (lib "eagle-import") (part "1N4148"))
    )
    (comp (ref "D127")
      (value "1N4148")
      (footprint "eagle-import:DO35-10")
      (libsource (lib "eagle-import") (part "1N4148"))
    )
    (comp (ref "D128")
      (value "1N4148")
      (footprint "eagle-import:DO35-10")
      (libsource (lib "eagle-import") (part "1N4148"))
    )
    (comp (ref "D129")
      (value "1N4148")
      (footprint "eagle-import:DO35-10")
      (libsource (lib "eagle-import") (part "1N4148"))
    )
    (comp (ref "E1")
      (value "N8881N")
      (footprint "eagle-import:DIL14")
      (libsource (lib "eagle-import") (part "N8881N"))
    )
    (comp (ref "E2")
      (value "SP380N")
      (footprint "eagle-import:DIL14")
      (libsource (lib "eagle-import") (part "SP380N"))
    )
    (comp (ref "E3")
      (value "7400N")
      (footprint "eagle-import:DIL14")
      (libsource (lib "eagle-import") (part "7400N"))
    )
    (comp (ref "E4")
      (value "N8881N")
      (footprint "eagle-import:DIL14")
      (libsource (lib "eagle-import") (part "N8881N"))
    )
    (comp (ref "E5")
      (value "7410N")
      (footprint "eagle-import:DIL14")
      (libsource (lib "eagle-import") (part "7410N"))
    )
    (comp (ref "E6")
      (value "7400N")
      (footprint "eagle-import:DIL14")
      (libsource (lib "eagle-import") (part "7400N"))
    )
    (comp (ref "E7")
      (value "N8881N")
      (footprint "eagle-import:DIL14")
      (libsource (lib "eagle-import") (part "N8881N"))
    )
    (comp (ref "E9")
      (value "7404N")
      (footprint "eagle-import:DIL14")
      (libsource (lib "eagle-import") (part "7404N"))
    )
    (comp (ref "E10")
      (value "7404N")
      (footprint "eagle-import:DIL14")
      (libsource (lib "eagle-import") (part "7404N"))
    )
    (comp (ref "E11")
      (value "SP384N")
      (footprint "eagle-import:DIL14")
      (libsource (lib "eagle-import") (part "SP384N"))
    )
    (comp (ref "E12")
      (value "7400N")
      (footprint "eagle-import:DIL14")
      (libsource (lib "eagle-import") (part "7400N"))
    )
    (comp (ref "E14")
      (value "7440N")
      (footprint "eagle-import:DIL14")
      (libsource (lib "eagle-import") (part "7420NS"))
    )
    (comp (ref "E16")
      (value "SP380N")
      (footprint "eagle-import:DIL14")
      (libsource (lib "eagle-import") (part "SP380N"))
    )
    (comp (ref "E19")
      (value "7416N")
      (footprint "eagle-import:DIL14")
      (libsource (lib "eagle-import") (part "7416N"))
    )
    (comp (ref "E20")
      (value "SP380N")
      (footprint "eagle-import:DIL14")
      (libsource (lib "eagle-import") (part "SP380N"))
    )
    (comp (ref "E23")
      (value "7416N")
      (footprint "eagle-import:DIL14")
      (libsource (lib "eagle-import") (part "7416N"))
    )
    (comp (ref "E24")
      (value "SP380N")
      (footprint "eagle-import:DIL14")
      (libsource (lib "eagle-import") (part "SP380N"))
    )
    (comp (ref "E27")
      (value "7416N")
      (footprint "eagle-import:DIL14")
      (libsource (lib "eagle-import") (part "7416N"))
    )
    (comp (ref "E28")
      (value "SP380N")
      (footprint "eagle-import:DIL14")
      (libsource (lib "eagle-import") (part "SP380N"))
    )
    (comp (ref "I13")
      (value "BULB")
      (footprint "eagle-import:BULB")
      (libsource (lib "eagle-import") (part "BULB"))
    )
    (comp (ref "I14")
      (value "BULB")
      (footprint "eagle-import:BULB")
      (libsource (lib "eagle-import") (part "BULB"))
    )
    (comp (ref "I15")
      (value "BULB")
      (footprint "eagle-import:BULB")
      (libsource (lib "eagle-import") (part "BULB"))
    )
    (comp (ref "I16")
      (value "BULB")
      (footprint "eagle-import:BULB")
      (libsource (lib "eagle-import") (part "BULB"))
    )
    (comp (ref "I17")
      (value "BULB")
      (footprint "eagle-import:BULB")
      (libsource (lib "eagle-import") (part "BULB"))
    )
    (comp (ref "I18")
      (value "BULB")
      (footprint "eagle-import:BULB")
      (libsource (lib "eagle-import") (part "BULB"))
    )
    (comp (ref "I19")
      (value "BULB")
      (footprint "eagle-import:BULB")
      (libsource (lib "eagle-import") (part "BULB"))
    )
    (comp (ref "I20")
      (value "BULB")
      (footprint "eagle-import:BULB")
      (libsource (lib "eagle-import") (part "BULB"))
    )
    (comp (ref "I21")
      (value "BULB")
      (footprint "eagle-import:BULB")
      (libsource (lib "eagle-import") (part "BULB"))
    )
    (comp (ref "I22")
      (value "BULB")
      (footprint "eagle-import:BULB")
      (libsource (lib "eagle-import") (part "BULB"))
    )
    (comp (ref "I23")
      (value "BULB")
      (footprint "eagle-import:BULB")
      (libsource (lib "eagle-import") (part "BULB"))
    )
    (comp (ref "I24")
      (value "BULB")
      (footprint "eagle-import:BULB")
      (libsource (lib "eagle-import") (part "BULB"))
    )
    (comp (ref "I25")
      (value "BULB")
      (footprint "eagle-import:BULB")
      (libsource (lib "eagle-import") (part "BULB"))
    )
    (comp (ref "I26")
      (value "BULB")
      (footprint "eagle-import:BULB")
      (libsource (lib "eagle-import") (part "BULB"))
    )
    (comp (ref "I27")
      (value "BULB")
      (footprint "eagle-import:BULB")
      (libsource (lib "eagle-import") (part "BULB"))
    )
    (comp (ref "I28")
      (value "BULB")
      (footprint "eagle-import:BULB")
      (libsource (lib "eagle-import") (part "BULB"))
    )
    (comp (ref "Q13")
      (value "MPS6534")
      (footprint "eagle-import:TO39")
      (libsource (lib "eagle-import") (part "2N3637"))
    )
    (comp (ref "Q14")
      (value "MPS6534")
      (footprint "eagle-import:TO39")
      (libsource (lib "eagle-import") (part "2N3637"))
    )
    (comp (ref "Q15")
      (value "MPS6534")
      (footprint "eagle-import:TO39")
      (libsource (lib "eagle-import") (part "2N3637"))
    )
    (comp (ref "Q16")
      (value "MPS6534")
      (footprint "eagle-import:TO39")
      (libsource (lib "eagle-import") (part "2N3637"))
    )
    (comp (ref "Q17")
      (value "2N3009B")
      (footprint "eagle-import:TO39")
      (libsource (lib "eagle-import") (part "2N3019"))
    )
    (comp (ref "Q18")
      (value "2N3009B")
      (footprint "eagle-import:TO39")
      (libsource (lib "eagle-import") (part "2N3019"))
    )
    (comp (ref "Q19")
      (value "2N3009B")
      (footprint "eagle-import:TO39")
      (libsource (lib "eagle-import") (part "2N3019"))
    )
    (comp (ref "R127")
      (value "390")
      (footprint "eagle-import:0207_10")
      (libsource (lib "eagle-import") (part "R-US_0207/10"))
    )
    (comp (ref "R128")
      (value "390")
      (footprint "eagle-import:0207_10")
      (libsource (lib "eagle-import") (part "R-US_0207/10"))
    )
    (comp (ref "R129")
      (value "390")
      (footprint "eagle-import:0207_10")
      (libsource (lib "eagle-import") (part "R-US_0207/10"))
    )
    (comp (ref "R130")
      (value "390")
      (footprint "eagle-import:0207_10")
      (libsource (lib "eagle-import") (part "R-US_0207/10"))
    )
    (comp (ref "R131")
      (value "390")
      (footprint "eagle-import:0207_10")
      (libsource (lib "eagle-import") (part "R-US_0207/10"))
    )
    (comp (ref "R132")
      (value "390")
      (footprint "eagle-import:0207_10")
      (libsource (lib "eagle-import") (part "R-US_0207/10"))
    )
    (comp (ref "R133")
      (value "390")
      (footprint "eagle-import:0207_10")
      (libsource (lib "eagle-import") (part "R-US_0207/10"))
    )
    (comp (ref "R134")
      (value "390")
      (footprint "eagle-import:0207_10")
      (libsource (lib "eagle-import") (part "R-US_0207/10"))
    )
    (comp (ref "R135")
      (value "390")
      (footprint "eagle-import:0207_10")
      (libsource (lib "eagle-import") (part "R-US_0207/10"))
    )
    (comp (ref "R136")
      (value "390")
      (footprint "eagle-import:0207_10")
      (libsource (lib "eagle-import") (part "R-US_0207/10"))
    )
    (comp (ref "R137")
      (value "390")
      (footprint "eagle-import:0207_10")
      (libsource (lib "eagle-import") (part "R-US_0207/10"))
    )
    (comp (ref "R138")
      (value "390")
      (footprint "eagle-import:0207_10")
      (libsource (lib "eagle-import") (part "R-US_0207/10"))
    )
    (comp (ref "R139")
      (value "390")
      (footprint "eagle-import:0207_10")
      (libsource (lib "eagle-import") (part "R-US_0207/10"))
    )
    (comp (ref "R140")
      (value "390")
      (footprint "eagle-import:0207_10")
      (libsource (lib "eagle-import") (part "R-US_0207/10"))
    )
    (comp (ref "R141")
      (value "390")
      (footprint "eagle-import:0207_10")
      (libsource (lib "eagle-import") (part "R-US_0207/10"))
    )
    (comp (ref "R142")
      (value "3K")
      (footprint "eagle-import:0207_10")
      (libsource (lib "eagle-import") (part "R-US_0207/10"))
    )
    (comp (ref "R143")
      (value "3K")
      (footprint "eagle-import:0207_10")
      (libsource (lib "eagle-import") (part "R-US_0207/10"))
    )
    (comp (ref "R144")
      (value "3K")
      (footprint "eagle-import:0207_10")
      (libsource (lib "eagle-import") (part "R-US_0207/10"))
    )
    (comp (ref "R145")
      (value "3K")
      (footprint "eagle-import:0207_10")
      (libsource (lib "eagle-import") (part "R-US_0207/10"))
    )
    (comp (ref "R146")
      (value "3K")
      (footprint "eagle-import:0207_10")
      (libsource (lib "eagle-import") (part "R-US_0207/10"))
    )
    (comp (ref "R147")
      (value "3K")
      (footprint "eagle-import:0207_10")
      (libsource (lib "eagle-import") (part "R-US_0207/10"))
    )
    (comp (ref "R148")
      (value "4.7K")
      (footprint "eagle-import:0207_10")
      (libsource (lib "eagle-import") (part "R-US_0207/10"))
    )
    (comp (ref "R149")
      (value "1K")
      (footprint "eagle-import:0207_10")
      (libsource (lib "eagle-import") (part "R-US_0207/10"))
    )
    (comp (ref "R150")
      (value "1K")
      (footprint "eagle-import:0207_10")
      (libsource (lib "eagle-import") (part "R-US_0207/10"))
    )
    (comp (ref "R151")
      (value "3K")
      (footprint "eagle-import:0207_10")
      (libsource (lib "eagle-import") (part "R-US_0207/10"))
    )
    (comp (ref "R152")
      (value "3K")
      (footprint "eagle-import:0207_10")
      (libsource (lib "eagle-import") (part "R-US_0207/10"))
    )
    (comp (ref "R153")
      (value "1000")
      (footprint "eagle-import:0207_10")
      (libsource (lib "eagle-import") (part "R-US_0207/10"))
    )
    (comp (ref "R154")
      (value "100")
      (footprint "eagle-import:0207_10")
      (libsource (lib "eagle-import") (part "R-US_0207/10"))
    )
    (comp (ref "R155")
      (value "1000")
      (footprint "eagle-import:0207_10")
      (libsource (lib "eagle-import") (part "R-US_0207/10"))
    )
    (comp (ref "R156")
      (value "150")
      (footprint "eagle-import:0207_10")
      (libsource (lib "eagle-import") (part "R-US_0207/10"))
    )
    (comp (ref "R157")
      (value "3000")
      (footprint "eagle-import:0207_10")
      (libsource (lib "eagle-import") (part "R-US_0207/10"))
    )
    (comp (ref "R158")
      (value "15K")
      (footprint "eagle-import:0207_10")
      (libsource (lib "eagle-import") (part "R-US_0207/10"))
    )
    (comp (ref "R159")
      (value "15K")
      (footprint "eagle-import:0207_10")
      (libsource (lib "eagle-import") (part "R-US_0207/10"))
    )
    (comp (ref "R160")
      (value "15K")
      (footprint "eagle-import:0207_10")
      (libsource (lib "eagle-import") (part "R-US_0207/10"))
    )
    (comp (ref "R161")
      (value "1800")
      (footprint "eagle-import:0207_10")
      (libsource (lib "eagle-import") (part "R-US_0207/10"))
    )
    (comp (ref "R162")
      (value "470")
      (footprint "eagle-import:0207_10")
      (libsource (lib "eagle-import") (part "R-US_0207/10"))
    )
    (comp (ref "R163")
      (value "27")
      (footprint "eagle-import:0207_10")
      (libsource (lib "eagle-import") (part "R-US_0207/10"))
    )
    (comp (ref "R164")
      (value "470")
      (footprint "eagle-import:0207_10")
      (libsource (lib "eagle-import") (part "R-US_0207/10"))
    )
    (comp (ref "R165")
      (value "27")
      (footprint "eagle-import:0207_10")
      (libsource (lib "eagle-import") (part "R-US_0207/10"))
    )
    (comp (ref "R166")
      (value "1K")
      (footprint "eagle-import:0207_10")
      (libsource (lib "eagle-import") (part "R-US_0207/10"))
    )
    (comp (ref "R167")
      (value "470")
      (footprint "eagle-import:0207_10")
      (libsource (lib "eagle-import") (part "R-US_0207/10"))
    )
    (comp (ref "R168")
      (value "1K")
      (footprint "eagle-import:0207_10")
      (libsource (lib "eagle-import") (part "R-US_0207/10"))
    )
    (comp (ref "R169")
      (value "100")
      (footprint "eagle-import:0207_10")
      (libsource (lib "eagle-import") (part "R-US_0207/10"))
    )
    (comp (ref "R170")
      (value "470")
      (footprint "eagle-import:0207_10")
      (libsource (lib "eagle-import") (part "R-US_0207/10"))
    )
    (comp (ref "R171")
      (value "4.7K")
      (footprint "eagle-import:0207_10")
      (libsource (lib "eagle-import") (part "R-US_0207/10"))
    )
    (comp (ref "R172")
      (value "27")
      (footprint "eagle-import:0207_10")
      (libsource (lib "eagle-import") (part "R-US_0207/10"))
    )
    (comp (ref "R173")
      (value "4.7K")
      (footprint "eagle-import:0207_10")
      (libsource (lib "eagle-import") (part "R-US_0207/10"))
    )
    (comp (ref "R174")
      (value "27")
      (footprint "eagle-import:0207_10")
      (libsource (lib "eagle-import") (part "R-US_0207/10"))
    )
    (comp (ref "R175")
      (value "470")
      (footprint "eagle-import:0204_7")
      (libsource (lib "eagle-import") (part "R-US_0204/7"))
    )
    (comp (ref "S1")
      (value "ROTARY8E")
      (footprint "eagle-import:ROTARY-8E")
      (libsource (lib "eagle-import") (part "ROTARY8E"))
    )
    (comp (ref "BLUE")
      (value "LUG")
      (footprint "eagle-import:SPADELUG")
      (libsource (lib "eagle-import") (part "LUG"))
    )
    (comp (ref "C16")
      (value "6.8uF")
      (footprint "eagle-import:E12-8")
      (libsource (lib "eagle-import") (part "CPOL-USE20-8AXIAL"))
    )
    (comp (ref "C17")
      (value "6.8uF")
      (footprint "eagle-import:E12-8")
      (libsource (lib "eagle-import") (part "CPOL-USE20-8AXIAL"))
    )
    (comp (ref "C18")
      (value "6.8uF")
      (footprint "eagle-import:E12-8")
      (libsource (lib "eagle-import") (part "CPOL-USE20-8AXIAL"))
    )
    (comp (ref "C19")
      (value "6.8uF")
      (footprint "eagle-import:E12-8")
      (libsource (lib "eagle-import") (part "CPOL-USE20-8AXIAL"))
    )
    (comp (ref "C20")
      (value "6.8uF")
      (footprint "eagle-import:E12-8")
      (libsource (lib "eagle-import") (part "CPOL-USE20-8AXIAL"))
    )
    (comp (ref "C22")
      (value ".01uF")
      (footprint "eagle-import:C050-025X075")
      (libsource (lib "eagle-import") (part "C-US050-025X075"))
    )
    (comp (ref "C23")
      (value ".01uF")
      (footprint "eagle-import:C050-025X075")
      (libsource (lib "eagle-import") (part "C-US050-025X075"))
    )
    (comp (ref "C24")
      (value ".01uF")
      (footprint "eagle-import:C050-025X075")
      (libsource (lib "eagle-import") (part "C-US050-025X075"))
    )
    (comp (ref "C25")
      (value ".01uF")
      (footprint "eagle-import:C050-025X075")
      (libsource (lib "eagle-import") (part "C-US050-025X075"))
    )
    (comp (ref "C26")
      (value ".01uF")
      (footprint "eagle-import:C050-025X075")
      (libsource (lib "eagle-import") (part "C-US050-025X075"))
    )
    (comp (ref "C27")
      (value ".01uF")
      (footprint "eagle-import:C050-025X075")
      (libsource (lib "eagle-import") (part "C-US050-025X075"))
    )
    (comp (ref "C28")
      (value ".01uF")
      (footprint "eagle-import:C050-025X075")
      (libsource (lib "eagle-import") (part "C-US050-025X075"))
    )
    (comp (ref "C29")
      (value ".01uF")
      (footprint "eagle-import:C050-025X075")
      (libsource (lib "eagle-import") (part "C-US050-025X075"))
    )
    (comp (ref "C30")
      (value ".01uF")
      (footprint "eagle-import:C050-025X075")
      (libsource (lib "eagle-import") (part "C-US050-025X075"))
    )
    (comp (ref "C31")
      (value ".01uF")
      (footprint "eagle-import:C050-025X075")
      (libsource (lib "eagle-import") (part "C-US050-025X075"))
    )
    (comp (ref "C32")
      (value ".01uF")
      (footprint "eagle-import:C050-025X075")
      (libsource (lib "eagle-import") (part "C-US050-025X075"))
    )
    (comp (ref "C33")
      (value ".01uF")
      (footprint "eagle-import:C050-025X075")
      (libsource (lib "eagle-import") (part "C-US050-025X075"))
    )
    (comp (ref "C34")
      (value ".01uF")
      (footprint "eagle-import:C050-025X075")
      (libsource (lib "eagle-import") (part "C-US050-025X075"))
    )
    (comp (ref "C35")
      (value ".01uF")
      (footprint "eagle-import:C050-025X075")
      (libsource (lib "eagle-import") (part "C-US050-025X075"))
    )
    (comp (ref "C36")
      (value ".01uF")
      (footprint "eagle-import:C050-025X075")
      (libsource (lib "eagle-import") (part "C-US050-025X075"))
    )
    (comp (ref "C37")
      (value ".01uF")
      (footprint "eagle-import:C050-025X075")
      (libsource (lib "eagle-import") (part "C-US050-025X075"))
    )
    (comp (ref "C38")
      (value ".01uF")
      (footprint "eagle-import:C050-025X075")
      (libsource (lib "eagle-import") (part "C-US050-025X075"))
    )
    (comp (ref "C39")
      (value ".01uF")
      (footprint "eagle-import:C050-025X075")
      (libsource (lib "eagle-import") (part "C-US050-025X075"))
    )
    (comp (ref "C40")
      (value "6.8uF")
      (footprint "eagle-import:E12-8")
      (libsource (lib "eagle-import") (part "CPOL-USE20-8AXIAL"))
    )
    (comp (ref "C41")
      (value "6.8uF")
      (footprint "eagle-import:E12-8")
      (libsource (lib "eagle-import") (part "CPOL-USE20-8AXIAL"))
    )
    (comp (ref "D85")
      (value "1N4148")
      (footprint "eagle-import:DO35-10")
      (libsource (lib "eagle-import") (part "1N4148"))
    )
    (comp (ref "D86")
      (value "1N4148")
      (footprint "eagle-import:DO35-10")
      (libsource (lib "eagle-import") (part "1N4148"))
    )
    (comp (ref "D87")
      (value "1N4148")
      (footprint "eagle-import:DO35-10")
      (libsource (lib "eagle-import") (part "1N4148"))
    )
    (comp (ref "D88")
      (value "1N4148")
      (footprint "eagle-import:DO35-10")
      (libsource (lib "eagle-import") (part "1N4148"))
    )
    (comp (ref "D89")
      (value "1N4148")
      (footprint "eagle-import:DO35-10")
      (libsource (lib "eagle-import") (part "1N4148"))
    )
    (comp (ref "D90")
      (value "1N4148")
      (footprint "eagle-import:DO35-10")
      (libsource (lib "eagle-import") (part "1N4148"))
    )
    (comp (ref "D91")
      (value "1N4148")
      (footprint "eagle-import:DO35-10")
      (libsource (lib "eagle-import") (part "1N4148"))
    )
    (comp (ref "D92")
      (value "1N4148")
      (footprint "eagle-import:DO35-10")
      (libsource (lib "eagle-import") (part "1N4148"))
    )
    (comp (ref "D93")
      (value "1N4148")
      (footprint "eagle-import:DO35-10")
      (libsource (lib "eagle-import") (part "1N4148"))
    )
    (comp (ref "D94")
      (value "1N4148")
      (footprint "eagle-import:DO35-10")
      (libsource (lib "eagle-import") (part "1N4148"))
    )
    (comp (ref "D95")
      (value "1N4148")
      (footprint "eagle-import:DO35-10")
      (libsource (lib "eagle-import") (part "1N4148"))
    )
    (comp (ref "D96")
      (value "1N4148")
      (footprint "eagle-import:DO35-10")
      (libsource (lib "eagle-import") (part "1N4148"))
    )
    (comp (ref "D97")
      (value "1N4148")
      (footprint "eagle-import:DO35-10")
      (libsource (lib "eagle-import") (part "1N4148"))
    )
    (comp (ref "D98")
      (value "1N4148")
      (footprint "eagle-import:DO35-10")
      (libsource (lib "eagle-import") (part "1N4148"))
    )
    (comp (ref "D99")
      (value "1N4148")
      (footprint "eagle-import:DO35-10")
      (libsource (lib "eagle-import") (part "1N4148"))
    )
    (comp (ref "D100")
      (value "1N4148")
      (footprint "eagle-import:DO35-10")
      (libsource (lib "eagle-import") (part "1N4148"))
    )
    (comp (ref "D101")
      (value "1N4148")
      (footprint "eagle-import:DO35-10")
      (libsource (lib "eagle-import") (part "1N4148"))
    )
    (comp (ref "D102")
      (value "1N4148")
      (footprint "eagle-import:DO35-10")
      (libsource (lib "eagle-import") (part "1N4148"))
    )
    (comp (ref "D103")
      (value "1N4148")
      (footprint "eagle-import:DO35-10")
      (libsource (lib "eagle-import") (part "1N4148"))
    )
    (comp (ref "D104")
      (value "1N4148")
      (footprint "eagle-import:DO35-10")
      (libsource (lib "eagle-import") (part "1N4148"))
    )
    (comp (ref "D105")
      (value "1N4148")
      (footprint "eagle-import:DO35-10")
      (libsource (lib "eagle-import") (part "1N4148"))
    )
    (comp (ref "E8")
      (value "7410N")
      (footprint "eagle-import:DIL14")
      (libsource (lib "eagle-import") (part "7410N"))
    )
    (comp (ref "E13")
      (value "SP380N")
      (footprint "eagle-import:DIL14")
      (libsource (lib "eagle-import") (part "SP380N"))
    )
    (comp (ref "E15")
      (value "SP314N")
      (footprint "eagle-import:DIL14")
      (libsource (lib "eagle-import") (part "SP314N"))
    )
    (comp (ref "E17")
      (value "N8881N")
      (footprint "eagle-import:DIL14")
      (libsource (lib "eagle-import") (part "N8881N"))
    )
    (comp (ref "E21")
      (value "N8881N")
      (footprint "eagle-import:DIL14")
      (libsource (lib "eagle-import") (part "N8881N"))
    )
    (comp (ref "E25")
      (value "N8881N")
      (footprint "eagle-import:DIL14")
      (libsource (lib "eagle-import") (part "N8881N"))
    )
    (comp (ref "R85")
      (value "1.5K")
      (footprint "eagle-import:0207_10")
      (libsource (lib "eagle-import") (part "R-US_0207/10"))
    )
    (comp (ref "R86")
      (value "1.5K")
      (footprint "eagle-import:0207_10")
      (libsource (lib "eagle-import") (part "R-US_0207/10"))
    )
    (comp (ref "R87")
      (value "1.5K")
      (footprint "eagle-import:0207_10")
      (libsource (lib "eagle-import") (part "R-US_0207/10"))
    )
    (comp (ref "R88")
      (value "3K")
      (footprint "eagle-import:0207_10")
      (libsource (lib "eagle-import") (part "R-US_0207/10"))
    )
    (comp (ref "R89")
      (value "1.5K")
      (footprint "eagle-import:0207_10")
      (libsource (lib "eagle-import") (part "R-US_0207/10"))
    )
    (comp (ref "R90")
      (value "3K")
      (footprint "eagle-import:0207_10")
      (libsource (lib "eagle-import") (part "R-US_0207/10"))
    )
    (comp (ref "R91")
      (value "1.5K")
      (footprint "eagle-import:0207_10")
      (libsource (lib "eagle-import") (part "R-US_0207/10"))
    )
    (comp (ref "R92")
      (value "3K")
      (footprint "eagle-import:0207_10")
      (libsource (lib "eagle-import") (part "R-US_0207/10"))
    )
    (comp (ref "R93")
      (value "1.5K")
      (footprint "eagle-import:0207_10")
      (libsource (lib "eagle-import") (part "R-US_0207/10"))
    )
    (comp (ref "R94")
      (value "3K")
      (footprint "eagle-import:0207_10")
      (libsource (lib "eagle-import") (part "R-US_0207/10"))
    )
    (comp (ref "R95")
      (value "1.5K")
      (footprint "eagle-import:0207_10")
      (libsource (lib "eagle-import") (part "R-US_0207/10"))
    )
    (comp (ref "R96")
      (value "3K")
      (footprint "eagle-import:0207_10")
      (libsource (lib "eagle-import") (part "R-US_0207/10"))
    )
    (comp (ref "R97")
      (value "1.5K")
      (footprint "eagle-import:0207_10")
      (libsource (lib "eagle-import") (part "R-US_0207/10"))
    )
    (comp (ref "R98")
      (value "3K")
      (footprint "eagle-import:0207_10")
      (libsource (lib "eagle-import") (part "R-US_0207/10"))
    )
    (comp (ref "R99")
      (value "1.5K")
      (footprint "eagle-import:0207_10")
      (libsource (lib "eagle-import") (part "R-US_0207/10"))
    )
    (comp (ref "R100")
      (value "3K")
      (footprint "eagle-import:0207_10")
      (libsource (lib "eagle-import") (part "R-US_0207/10"))
    )
    (comp (ref "R101")
      (value "1.5K")
      (footprint "eagle-import:0207_10")
      (libsource (lib "eagle-import") (part "R-US_0207/10"))
    )
    (comp (ref "R102")
      (value "3K")
      (footprint "eagle-import:0207_10")
      (libsource (lib "eagle-import") (part "R-US_0207/10"))
    )
    (comp (ref "R103")
      (value "1.5K")
      (footprint "eagle-import:0207_10")
      (libsource (lib "eagle-import") (part "R-US_0207/10"))
    )
    (comp (ref "R104")
      (value "3K")
      (footprint "eagle-import:0207_10")
      (libsource (lib "eagle-import") (part "R-US_0207/10"))
    )
    (comp (ref "R105")
      (value "1.5K")
      (footprint "eagle-import:0207_10")
      (libsource (lib "eagle-import") (part "R-US_0207/10"))
    )
    (comp (ref "R106")
      (value "3K")
      (footprint "eagle-import:0207_10")
      (libsource (lib "eagle-import") (part "R-US_0207/10"))
    )
    (comp (ref "R107")
      (value "1.5K")
      (footprint "eagle-import:0207_10")
      (libsource (lib "eagle-import") (part "R-US_0207/10"))
    )
    (comp (ref "R108")
      (value "3K")
      (footprint "eagle-import:0207_10")
      (libsource (lib "eagle-import") (part "R-US_0207/10"))
    )
    (comp (ref "R109")
      (value "1.5K")
      (footprint "eagle-import:0207_10")
      (libsource (lib "eagle-import") (part "R-US_0207/10"))
    )
    (comp (ref "R110")
      (value "3K")
      (footprint "eagle-import:0207_10")
      (libsource (lib "eagle-import") (part "R-US_0207/10"))
    )
    (comp (ref "R111")
      (value "1.5K")
      (footprint "eagle-import:0207_10")
      (libsource (lib "eagle-import") (part "R-US_0207/10"))
    )
    (comp (ref "R112")
      (value "3K")
      (footprint "eagle-import:0207_10")
      (libsource (lib "eagle-import") (part "R-US_0207/10"))
    )
    (comp (ref "R113")
      (value "1.5K")
      (footprint "eagle-import:0207_10")
      (libsource (lib "eagle-import") (part "R-US_0207/10"))
    )
    (comp (ref "R114")
      (value "3K")
      (footprint "eagle-import:0207_10")
      (libsource (lib "eagle-import") (part "R-US_0207/10"))
    )
    (comp (ref "R115")
      (value "1.5K")
      (footprint "eagle-import:0207_10")
      (libsource (lib "eagle-import") (part "R-US_0207/10"))
    )
    (comp (ref "R116")
      (value "3K")
      (footprint "eagle-import:0207_10")
      (libsource (lib "eagle-import") (part "R-US_0207/10"))
    )
    (comp (ref "R117")
      (value "1.5K")
      (footprint "eagle-import:0207_10")
      (libsource (lib "eagle-import") (part "R-US_0207/10"))
    )
    (comp (ref "R118")
      (value "3K")
      (footprint "eagle-import:0207_10")
      (libsource (lib "eagle-import") (part "R-US_0207/10"))
    )
    (comp (ref "R119")
      (value "1.5K")
      (footprint "eagle-import:0207_10")
      (libsource (lib "eagle-import") (part "R-US_0207/10"))
    )
    (comp (ref "R120")
      (value "3K")
      (footprint "eagle-import:0207_10")
      (libsource (lib "eagle-import") (part "R-US_0207/10"))
    )
    (comp (ref "R121")
      (value "1.5K")
      (footprint "eagle-import:0207_10")
      (libsource (lib "eagle-import") (part "R-US_0207/10"))
    )
    (comp (ref "R122")
      (value "3K")
      (footprint "eagle-import:0207_10")
      (libsource (lib "eagle-import") (part "R-US_0207/10"))
    )
    (comp (ref "R123")
      (value "1.5K")
      (footprint "eagle-import:0207_10")
      (libsource (lib "eagle-import") (part "R-US_0207/10"))
    )
    (comp (ref "R124")
      (value "3K")
      (footprint "eagle-import:0207_10")
      (libsource (lib "eagle-import") (part "R-US_0207/10"))
    )
    (comp (ref "R125")
      (value "1.5K")
      (footprint "eagle-import:0207_10")
      (libsource (lib "eagle-import") (part "R-US_0207/10"))
    )
    (comp (ref "R126")
      (value "3K")
      (footprint "eagle-import:0207_10")
      (libsource (lib "eagle-import") (part "R-US_0207/10"))
    )
    (comp (ref "S2")
      (value "DPDT8I")
      (footprint "eagle-import:DPDT8I")
      (libsource (lib "eagle-import") (part "DPDT8I"))
    )
    (comp (ref "S3")
      (value "SPDT8I")
      (footprint "eagle-import:SPDT8I")
      (libsource (lib "eagle-import") (part "SPDT8I"))
    )
    (comp (ref "S4")
      (value "SPDT8I")
      (footprint "eagle-import:SPDT8I")
      (libsource (lib "eagle-import") (part "SPDT8I"))
    )
    (comp (ref "S5")
      (value "SPDT8I")
      (footprint "eagle-import:SPDT8I")
      (libsource (lib "eagle-import") (part "SPDT8I"))
    )
    (comp (ref "S6")
      (value "SPDT8I")
      (footprint "eagle-import:SPDT8I")
      (libsource (lib "eagle-import") (part "SPDT8I"))
    )
    (comp (ref "S7")
      (value "SPDT8I")
      (footprint "eagle-import:SPDT8I")
      (libsource (lib "eagle-import") (part "SPDT8I"))
    )
    (comp (ref "S8")
      (value "SPDT8I")
      (footprint "eagle-import:SPDT8I")
      (libsource (lib "eagle-import") (part "SPDT8I"))
    )
    (comp (ref "S9")
      (value "DPDT8I")
      (footprint "eagle-import:DPDT8I")
      (libsource (lib "eagle-import") (part "DPDT8I"))
    )
    (comp (ref "S10")
      (value "DPDT8I")
      (footprint "eagle-import:DPDT8I")
      (libsource (lib "eagle-import") (part "DPDT8I"))
    )
    (comp (ref "S11")
      (value "DPDT8I")
      (footprint "eagle-import:DPDT8I")
      (libsource (lib "eagle-import") (part "DPDT8I"))
    )
    (comp (ref "S12")
      (value "DPDT8I")
      (footprint "eagle-import:DPDT8I")
      (libsource (lib "eagle-import") (part "DPDT8I"))
    )
    (comp (ref "S13")
      (value "DPDT8I")
      (footprint "eagle-import:DPDT8I")
      (libsource (lib "eagle-import") (part "DPDT8I"))
    )
    (comp (ref "S14")
      (value "DPDT8I")
      (footprint "eagle-import:DPDT8I")
      (libsource (lib "eagle-import") (part "DPDT8I"))
    )
    (comp (ref "S15")
      (value "DPDT8I")
      (footprint "eagle-import:DPDT8I")
      (libsource (lib "eagle-import") (part "DPDT8I"))
    )
    (comp (ref "S16")
      (value "DPDT8I")
      (footprint "eagle-import:DPDT8I")
      (libsource (lib "eagle-import") (part "DPDT8I"))
    )
    (comp (ref "S17")
      (value "DPDT8I")
      (footprint "eagle-import:DPDT8I")
      (libsource (lib "eagle-import") (part "DPDT8I"))
    )
    (comp (ref "S18")
      (value "DPDT8I")
      (footprint "eagle-import:DPDT8I")
      (libsource (lib "eagle-import") (part "DPDT8I"))
    )
    (comp (ref "S19")
      (value "DPDT8I")
      (footprint "eagle-import:DPDT8I")
      (libsource (lib "eagle-import") (part "DPDT8I"))
    )
    (comp (ref "S20")
      (value "DPDT8I")
      (footprint "eagle-import:DPDT8I")
      (libsource (lib "eagle-import") (part "DPDT8I"))
    )
    (comp (ref "S21")
      (value "DPDT8I")
      (footprint "eagle-import:DPDT8I")
      (libsource (lib "eagle-import") (part "DPDT8I"))
    )
    (comp (ref "S22")
      (value "DPDT8I")
      (footprint "eagle-import:DPDT8I")
      (libsource (lib "eagle-import") (part "DPDT8I"))
    )
    (comp (ref "YELLOW")
      (value "LUG")
      (footprint "eagle-import:SPADELUG")
      (libsource (lib "eagle-import") (part "LUG"))
    )
  )
  (nets
    (net (code "1") (name "+0.75V") (class "Default")
      (node (ref "D120") (pin "C") (pinfunction "C_C") (pintype "passive"))
      (node (ref "D125") (pin "C") (pinfunction "C_C") (pintype "passive"))
      (node (ref "D126") (pin "A") (pinfunction "A_A") (pintype "passive"))
    )
    (net (code "2") (name "+3V3") (class "Default")
      (node (ref "C21") (pin "1") (pinfunction "1_1") (pintype "passive"))
      (node (ref "D117") (pin "C") (pinfunction "C_C") (pintype "passive"))
      (node (ref "D121") (pin "C") (pinfunction "C_C") (pintype "passive"))
      (node (ref "D123") (pin "A") (pinfunction "A_A") (pintype "passive"))
      (node (ref "R170") (pin "1") (pinfunction "1_1") (pintype "passive"))
    )
    (net (code "3") (name "+8V") (class "Default")
      (node (ref "C16") (pin "+") (pinfunction "+_+") (pintype "passive"))
      (node (ref "I1") (pin "B") (pinfunction "B_B") (pintype "passive"))
      (node (ref "I10") (pin "B") (pinfunction "B_B") (pintype "passive"))
      (node (ref "I11") (pin "B") (pinfunction "B_B") (pintype "passive"))
      (node (ref "I12") (pin "B") (pinfunction "B_B") (pintype "passive"))
      (node (ref "I13") (pin "B") (pinfunction "B_B") (pintype "passive"))
      (node (ref "I14") (pin "B") (pinfunction "B_B") (pintype "passive"))
      (node (ref "I15") (pin "B") (pinfunction "B_B") (pintype "passive"))
      (node (ref "I16") (pin "B") (pinfunction "B_B") (pintype "passive"))
      (node (ref "I17") (pin "B") (pinfunction "B_B") (pintype "passive"))
      (node (ref "I18") (pin "B") (pinfunction "B_B") (pintype "passive"))
      (node (ref "I19") (pin "B") (pinfunction "B_B") (pintype "passive"))
      (node (ref "I2") (pin "B") (pinfunction "B_B") (pintype "passive"))
      (node (ref "I20") (pin "B") (pinfunction "B_B") (pintype "passive"))
      (node (ref "I21") (pin "B") (pinfunction "B_B") (pintype "passive"))
      (node (ref "I22") (pin "B") (pinfunction "B_B") (pintype "passive"))
      (node (ref "I23") (pin "B") (pinfunction "B_B") (pintype "passive"))
      (node (ref "I24") (pin "B") (pinfunction "B_B") (pintype "passive"))
      (node (ref "I25") (pin "B") (pinfunction "B_B") (pintype "passive"))
      (node (ref "I26") (pin "B") (pinfunction "B_B") (pintype "passive"))
      (node (ref "I27") (pin "B") (pinfunction "B_B") (pintype "passive"))
      (node (ref "I3") (pin "B") (pinfunction "B_B") (pintype "passive"))
      (node (ref "I4") (pin "B") (pinfunction "B_B") (pintype "passive"))
      (node (ref "I5") (pin "B") (pinfunction "B_B") (pintype "passive"))
      (node (ref "I6") (pin "B") (pinfunction "B_B") (pintype "passive"))
      (node (ref "I7") (pin "B") (pinfunction "B_B") (pintype "passive"))
      (node (ref "I8") (pin "B") (pinfunction "B_B") (pintype "passive"))
      (node (ref "I9") (pin "B") (pinfunction "B_B") (pintype "passive"))
      (node (ref "YELLOW") (pin "1") (pinfunction "1_1") (pintype "passive"))
    )
    (net (code "4") (name "-15V") (class "Default")
      (node (ref "C17") (pin "-") (pinfunction "-_-") (pintype "passive"))
      (node (ref "C40") (pin "-") (pinfunction "-_-") (pintype "passive"))
      (node (ref "C41") (pin "-") (pinfunction "-_-") (pintype "passive"))
      (node (ref "I28") (pin "A") (pinfunction "A_A") (pintype "passive"))
      (node (ref "R158") (pin "1") (pinfunction "1_1") (pintype "passive"))
      (node (ref "S1") (pin "S") (pinfunction "S_S") (pintype "passive"))
      (node (ref "S11") (pin "L2") (pinfunction "A2_L2") (pintype "bidirectional"))
      (node (ref "S11") (pin "R2") (pinfunction "B2_R2") (pintype "bidirectional"))
      (node (ref "S12") (pin "L2") (pinfunction "A2_L2") (pintype "bidirectional"))
      (node (ref "S12") (pin "R2") (pinfunction "B2_R2") (pintype "bidirectional"))
      (node (ref "S13") (pin "L2") (pinfunction "A2_L2") (pintype "bidirectional"))
      (node (ref "S13") (pin "R2") (pinfunction "B2_R2") (pintype "bidirectional"))
      (node (ref "S14") (pin "L2") (pinfunction "A2_L2") (pintype "bidirectional"))
      (node (ref "S14") (pin "R2") (pinfunction "B2_R2") (pintype "bidirectional"))
      (node (ref "S15") (pin "L2") (pinfunction "A2_L2") (pintype "bidirectional"))
      (node (ref "S15") (pin "R2") (pinfunction "B2_R2") (pintype "bidirectional"))
      (node (ref "S16") (pin "L2") (pinfunction "A2_L2") (pintype "bidirectional"))
      (node (ref "S16") (pin "R2") (pinfunction "B2_R2") (pintype "bidirectional"))
      (node (ref "S17") (pin "L2") (pinfunction "A2_L2") (pintype "bidirectional"))
      (node (ref "S17") (pin "R2") (pinfunction "B2_R2") (pintype "bidirectional"))
      (node (ref "S18") (pin "L2") (pinfunction "A2_L2") (pintype "bidirectional"))
      (node (ref "S18") (pin "R2") (pinfunction "B2_R2") (pintype "bidirectional"))
      (node (ref "S19") (pin "L2") (pinfunction "A2_L2") (pintype "bidirectional"))
      (node (ref "S19") (pin "R2") (pinfunction "B2_R2") (pintype "bidirectional"))
      (node (ref "S20") (pin "L2") (pinfunction "A2_L2") (pintype "bidirectional"))
      (node (ref "S20") (pin "R2") (pinfunction "B2_R2") (pintype "bidirectional"))
      (node (ref "S21") (pin "L2") (pinfunction "A2_L2") (pintype "bidirectional"))
      (node (ref "S21") (pin "R2") (pinfunction "B2_R2") (pintype "bidirectional"))
      (node (ref "S22") (pin "L2") (pinfunction "A2_L2") (pintype "bidirectional"))
      (node (ref "S22") (pin "R2") (pinfunction "B2_R2") (pintype "bidirectional"))
      (node (ref "U$2") (pin "BB2") (pinfunction "1_BB2") (pintype "bidirectional"))
      (node (ref "U$2") (pin "CB2") (pinfunction "1_CB2") (pintype "bidirectional"))
      (node (ref "U$2") (pin "DB2") (pinfunction "1_DB2") (pintype "bidirectional"))
    )
    (net (code "5") (name "AC_EN") (class "Default")
      (node (ref "D107") (pin "C") (pinfunction "C_C") (pintype "passive"))
      (node (ref "D111") (pin "C") (pinfunction "C_C") (pintype "passive"))
      (node (ref "D112") (pin "C") (pinfunction "C_C") (pintype "passive"))
      (node (ref "R173") (pin "1") (pinfunction "1_1") (pintype "passive"))
      (node (ref "S1") (pin "4") (pinfunction "4_4") (pintype "passive"))
    )
    (net (code "6") (name "BK_DATA_CONT") (class "Default")
      (node (ref "D80") (pin "A") (pinfunction "A_A") (pintype "passive"))
      (node (ref "E4") (pin "1") (pinfunction "O_1") (pintype "open_collector"))
      (node (ref "U$2") (pin "BK2") (pinfunction "1_BK2") (pintype "bidirectional"))
    )
    (net (code "7") (name "BREAK_C") (class "Default")
      (node (ref "D84") (pin "A") (pinfunction "A_A") (pintype "passive"))
      (node (ref "U$2") (pin "BL2") (pinfunction "1_BL2") (pintype "bidirectional"))
    )
    (net (code "8") (name "BRK_INP") (class "Default")
      (node (ref "D83") (pin "A") (pinfunction "A_A") (pintype "passive"))
      (node (ref "U$2") (pin "BE2") (pinfunction "1_BE2") (pintype "bidirectional"))
    )
    (net (code "9") (name "BUS_EN") (class "Default")
      (node (ref "D113") (pin "C") (pinfunction "C_C") (pintype "passive"))
      (node (ref "D129") (pin "C") (pinfunction "C_C") (pintype "passive"))
      (node (ref "R145") (pin "1") (pinfunction "1_1") (pintype "passive"))
      (node (ref "S1") (pin "1") (pinfunction "1_1") (pintype "passive"))
    )
    (net (code "10") (name "CLR") (class "Default")
      (node (ref "D86") (pin "C") (pinfunction "C_C") (pintype "passive"))
      (node (ref "E10") (pin "5") (pinfunction "I_5") (pintype "input"))
      (node (ref "E14") (pin "13") (pinfunction "I3_13") (pintype "input"))
      (node (ref "R87") (pin "2") (pinfunction "2_2") (pintype "passive"))
    )
    (net (code "11") (name "CONT") (class "Default")
      (node (ref "D87") (pin "C") (pinfunction "C_C") (pintype "passive"))
      (node (ref "E5") (pin "5") (pinfunction "I2_5") (pintype "input"))
      (node (ref "R89") (pin "2") (pinfunction "2_2") (pintype "passive"))
    )
    (net (code "12") (name "CP_START") (class "Default")
      (node (ref "E1") (pin "3") (pinfunction "I1_3") (pintype "input"))
      (node (ref "E12") (pin "8") (pinfunction "O_8") (pintype "output"))
      (node (ref "E4") (pin "3") (pinfunction "I1_3") (pintype "input"))
      (node (ref "E4") (pin "6") (pinfunction "I1_6") (pintype "input"))
      (node (ref "E4") (pin "8") (pinfunction "I0_8") (pintype "input"))
      (node (ref "E5") (pin "13") (pinfunction "I2_13") (pintype "input"))
      (node (ref "E7") (pin "11") (pinfunction "I0_11") (pintype "input"))
      (node (ref "E8") (pin "5") (pinfunction "I2_5") (pintype "input"))
    )
    (net (code "13") (name "D") (class "Default")
      (node (ref "D74") (pin "A") (pinfunction "A_A") (pintype "passive"))
      (node (ref "U$2") (pin "DK2") (pinfunction "1_DK2") (pintype "bidirectional"))
    )
    (net (code "14") (name "DATA00") (class "Default")
      (node (ref "D61") (pin "A") (pinfunction "A_A") (pintype "passive"))
      (node (ref "E25") (pin "1") (pinfunction "O_1") (pintype "open_collector"))
      (node (ref "U$2") (pin "AR1") (pinfunction "1_AR1") (pintype "bidirectional"))
    )
    (net (code "15") (name "DATA01") (class "Default")
      (node (ref "D62") (pin "A") (pinfunction "A_A") (pintype "passive"))
      (node (ref "E25") (pin "4") (pinfunction "O_4") (pintype "open_collector"))
      (node (ref "U$2") (pin "AS1") (pinfunction "1_AS1") (pintype "bidirectional"))
    )
    (net (code "16") (name "DATA02") (class "Default")
      (node (ref "D63") (pin "A") (pinfunction "A_A") (pintype "passive"))
      (node (ref "E25") (pin "10") (pinfunction "O_10") (pintype "open_collector"))
      (node (ref "U$2") (pin "AU1") (pinfunction "1_AU1") (pintype "bidirectional"))
    )
    (net (code "17") (name "DATA03") (class "Default")
      (node (ref "D64") (pin "A") (pinfunction "A_A") (pintype "passive"))
      (node (ref "E25") (pin "13") (pinfunction "O_13") (pintype "open_collector"))
      (node (ref "U$2") (pin "AV1") (pinfunction "1_AV1") (pintype "bidirectional"))
    )
    (net (code "18") (name "DATA04") (class "Default")
      (node (ref "D65") (pin "A") (pinfunction "A_A") (pintype "passive"))
      (node (ref "E21") (pin "1") (pinfunction "O_1") (pintype "open_collector"))
      (node (ref "U$2") (pin "BR1") (pinfunction "1_BR1") (pintype "bidirectional"))
    )
    (net (code "19") (name "DATA05") (class "Default")
      (node (ref "D66") (pin "A") (pinfunction "A_A") (pintype "passive"))
      (node (ref "E21") (pin "4") (pinfunction "O_4") (pintype "open_collector"))
      (node (ref "U$2") (pin "BS1") (pinfunction "1_BS1") (pintype "bidirectional"))
    )
    (net (code "20") (name "DATA06") (class "Default")
      (node (ref "D67") (pin "A") (pinfunction "A_A") (pintype "passive"))
      (node (ref "E21") (pin "10") (pinfunction "O_10") (pintype "open_collector"))
      (node (ref "U$2") (pin "BU1") (pinfunction "1_BU1") (pintype "bidirectional"))
    )
    (net (code "21") (name "DATA07") (class "Default")
      (node (ref "D68") (pin "A") (pinfunction "A_A") (pintype "passive"))
      (node (ref "E21") (pin "13") (pinfunction "O_13") (pintype "open_collector"))
      (node (ref "U$2") (pin "BV1") (pinfunction "1_BV1") (pintype "bidirectional"))
    )
    (net (code "22") (name "DATA08") (class "Default")
      (node (ref "D69") (pin "A") (pinfunction "A_A") (pintype "passive"))
      (node (ref "E17") (pin "1") (pinfunction "O_1") (pintype "open_collector"))
      (node (ref "U$2") (pin "DR1") (pinfunction "1_DR1") (pintype "bidirectional"))
    )
    (net (code "23") (name "DATA09") (class "Default")
      (node (ref "D70") (pin "A") (pinfunction "A_A") (pintype "passive"))
      (node (ref "E17") (pin "4") (pinfunction "O_4") (pintype "open_collector"))
      (node (ref "U$2") (pin "DS1") (pinfunction "1_DS1") (pintype "bidirectional"))
    )
    (net (code "24") (name "DATA10") (class "Default")
      (node (ref "D71") (pin "A") (pinfunction "A_A") (pintype "passive"))
      (node (ref "E17") (pin "13") (pinfunction "O_13") (pintype "open_collector"))
      (node (ref "U$2") (pin "DU1") (pinfunction "1_DU1") (pintype "bidirectional"))
    )
    (net (code "25") (name "DATA11") (class "Default")
      (node (ref "D72") (pin "A") (pinfunction "A_A") (pintype "passive"))
      (node (ref "E17") (pin "10") (pinfunction "O_10") (pintype "open_collector"))
      (node (ref "U$2") (pin "DV1") (pinfunction "1_DV1") (pintype "bidirectional"))
    )
    (net (code "26") (name "DATA_EN") (class "Default")
      (node (ref "D106") (pin "A") (pinfunction "A_A") (pintype "passive"))
      (node (ref "D107") (pin "A") (pinfunction "A_A") (pintype "passive"))
      (node (ref "D108") (pin "A") (pinfunction "A_A") (pintype "passive"))
      (node (ref "D129") (pin "A") (pinfunction "A_A") (pintype "passive"))
      (node (ref "R62") (pin "2") (pinfunction "2_2") (pintype "passive"))
      (node (ref "R64") (pin "2") (pinfunction "2_2") (pintype "passive"))
      (node (ref "R66") (pin "2") (pinfunction "2_2") (pintype "passive"))
      (node (ref "R68") (pin "2") (pinfunction "2_2") (pintype "passive"))
      (node (ref "R70") (pin "2") (pinfunction "2_2") (pintype "passive"))
      (node (ref "R72") (pin "2") (pinfunction "2_2") (pintype "passive"))
      (node (ref "R74") (pin "2") (pinfunction "2_2") (pintype "passive"))
      (node (ref "R76") (pin "2") (pinfunction "2_2") (pintype "passive"))
      (node (ref "R78") (pin "2") (pinfunction "2_2") (pintype "passive"))
      (node (ref "R80") (pin "2") (pinfunction "2_2") (pintype "passive"))
      (node (ref "R82") (pin "2") (pinfunction "2_2") (pintype "passive"))
      (node (ref "R84") (pin "2") (pinfunction "2_2") (pintype "passive"))
    )
    (net (code "27") (name "DEP") (class "Default")
      (node (ref "D90") (pin "C") (pinfunction "C_C") (pintype "passive"))
      (node (ref "E5") (pin "3") (pinfunction "I0_3") (pintype "input"))
      (node (ref "E6") (pin "10") (pinfunction "I1_10") (pintype "input"))
      (node (ref "E8") (pin "11") (pinfunction "I2_11") (pintype "input"))
      (node (ref "E8") (pin "13") (pinfunction "I2_13") (pintype "input"))
      (node (ref "R95") (pin "2") (pinfunction "2_2") (pintype "passive"))
    )
    (net (code "28") (name "DEP+EXAM+CONT") (class "Default")
      (node (ref "E1") (pin "12") (pinfunction "I1_12") (pintype "input"))
      (node (ref "E10") (pin "3") (pinfunction "I_3") (pintype "input"))
      (node (ref "E5") (pin "6") (pinfunction "O_6") (pintype "output"))
    )
    (net (code "29") (name "E") (class "Default")
      (node (ref "D75") (pin "A") (pinfunction "A_A") (pintype "passive"))
      (node (ref "U$2") (pin "DL2") (pinfunction "1_DL2") (pintype "bidirectional"))
    )
    (net (code "30") (name "EMA0") (class "Default")
      (node (ref "E28") (pin "12") (pinfunction "I1_12") (pintype "input"))
      (node (ref "U$2") (pin "AD2") (pinfunction "1_AD2") (pintype "bidirectional"))
    )
    (net (code "31") (name "EMA1") (class "Default")
      (node (ref "E28") (pin "10") (pinfunction "I1_10") (pintype "input"))
      (node (ref "U$2") (pin "AE2") (pinfunction "1_AE2") (pintype "bidirectional"))
    )
    (net (code "32") (name "EMA2") (class "Default")
      (node (ref "E28") (pin "4") (pinfunction "I0_4") (pintype "input"))
      (node (ref "U$2") (pin "AH2") (pinfunction "1_AH2") (pintype "bidirectional"))
    )
    (net (code "33") (name "EXAM") (class "Default")
      (node (ref "D89") (pin "C") (pinfunction "C_C") (pintype "passive"))
      (node (ref "E5") (pin "4") (pinfunction "I1_4") (pintype "input"))
      (node (ref "E6") (pin "1") (pinfunction "I0_1") (pintype "input"))
      (node (ref "E8") (pin "2") (pinfunction "I1_2") (pintype "input"))
      (node (ref "R93") (pin "2") (pinfunction "2_2") (pintype "passive"))
    )
    (net (code "34") (name "EXT_LOAD") (class "Default")
      (node (ref "D91") (pin "C") (pinfunction "C_C") (pintype "passive"))
      (node (ref "E12") (pin "5") (pinfunction "I1_5") (pintype "input"))
      (node (ref "E14") (pin "9") (pinfunction "I0_9") (pintype "input"))
      (node (ref "E8") (pin "1") (pinfunction "I0_1") (pintype "input"))
      (node (ref "E8") (pin "10") (pinfunction "I1_10") (pintype "input"))
      (node (ref "R97") (pin "2") (pinfunction "2_2") (pintype "passive"))
    )
    (net (code "35") (name "FETCH") (class "Default")
      (node (ref "D73") (pin "A") (pinfunction "A_A") (pintype "passive"))
      (node (ref "E2") (pin "4") (pinfunction "I0_4") (pintype "input"))
      (node (ref "U$2") (pin "DJ2") (pinfunction "1_DJ2") (pintype "bidirectional"))
    )
    (net (code "36") (name "FSET") (class "Default")
      (node (ref "E11") (pin "9") (pinfunction "I0_9") (pintype "input"))
      (node (ref "U$2") (pin "DP2") (pinfunction "1_DP2") (pintype "bidirectional"))
    )
    (net (code "37") (name "GND") (class "Default")
      (node (ref "C13") (pin "-") (pinfunction "-_-") (pintype "passive"))
      (node (ref "C16") (pin "-") (pinfunction "-_-") (pintype "passive"))
      (node (ref "C17") (pin "+") (pinfunction "+_+") (pintype "passive"))
      (node (ref "C18") (pin "-") (pinfunction "-_-") (pintype "passive"))
      (node (ref "C19") (pin "-") (pinfunction "-_-") (pintype "passive"))
      (node (ref "C20") (pin "-") (pinfunction "-_-") (pintype "passive"))
      (node (ref "C21") (pin "2") (pinfunction "2_2") (pintype "passive"))
      (node (ref "C22") (pin "2") (pinfunction "2_2") (pintype "passive"))
      (node (ref "C23") (pin "2") (pinfunction "2_2") (pintype "passive"))
      (node (ref "C24") (pin "2") (pinfunction "2_2") (pintype "passive"))
      (node (ref "C25") (pin "2") (pinfunction "2_2") (pintype "passive"))
      (node (ref "C26") (pin "2") (pinfunction "2_2") (pintype "passive"))
      (node (ref "C27") (pin "2") (pinfunction "2_2") (pintype "passive"))
      (node (ref "C28") (pin "2") (pinfunction "2_2") (pintype "passive"))
      (node (ref "C29") (pin "2") (pinfunction "2_2") (pintype "passive"))
      (node (ref "C30") (pin "2") (pinfunction "2_2") (pintype "passive"))
      (node (ref "C31") (pin "2") (pinfunction "2_2") (pintype "passive"))
      (node (ref "C32") (pin "2") (pinfunction "2_2") (pintype "passive"))
      (node (ref "C33") (pin "2") (pinfunction "2_2") (pintype "passive"))
      (node (ref "C34") (pin "2") (pinfunction "2_2") (pintype "passive"))
      (node (ref "C35") (pin "2") (pinfunction "2_2") (pintype "passive"))
      (node (ref "C36") (pin "2") (pinfunction "2_2") (pintype "passive"))
      (node (ref "C37") (pin "2") (pinfunction "2_2") (pintype "passive"))
      (node (ref "C38") (pin "2") (pinfunction "2_2") (pintype "passive"))
      (node (ref "C39") (pin "2") (pinfunction "2_2") (pintype "passive"))
      (node (ref "C40") (pin "+") (pinfunction "+_+") (pintype "passive"))
      (node (ref "C41") (pin "+") (pinfunction "+_+") (pintype "passive"))
      (node (ref "D100") (pin "A") (pinfunction "A_A") (pintype "passive"))
      (node (ref "D101") (pin "A") (pinfunction "A_A") (pintype "passive"))
      (node (ref "D102") (pin "A") (pinfunction "A_A") (pintype "passive"))
      (node (ref "D103") (pin "A") (pinfunction "A_A") (pintype "passive"))
      (node (ref "D104") (pin "A") (pinfunction "A_A") (pintype "passive"))
      (node (ref "D105") (pin "A") (pinfunction "A_A") (pintype "passive"))
      (node (ref "D109") (pin "A") (pinfunction "A_A") (pintype "passive"))
      (node (ref "D114") (pin "A") (pinfunction "A_A") (pintype "passive"))
      (node (ref "D115") (pin "A") (pinfunction "A_A") (pintype "passive"))
      (node (ref "D119") (pin "A") (pinfunction "A_A") (pintype "passive"))
      (node (ref "D126") (pin "C") (pinfunction "C_C") (pintype "passive"))
      (node (ref "D127") (pin "A") (pinfunction "A_A") (pintype "passive"))
      (node (ref "D128") (pin "A") (pinfunction "A_A") (pintype "passive"))
      (node (ref "D85") (pin "A") (pinfunction "A_A") (pintype "passive"))
      (node (ref "D86") (pin "A") (pinfunction "A_A") (pintype "passive"))
      (node (ref "D87") (pin "A") (pinfunction "A_A") (pintype "passive"))
      (node (ref "D88") (pin "A") (pinfunction "A_A") (pintype "passive"))
      (node (ref "D89") (pin "A") (pinfunction "A_A") (pintype "passive"))
      (node (ref "D90") (pin "A") (pinfunction "A_A") (pintype "passive"))
      (node (ref "D91") (pin "A") (pinfunction "A_A") (pintype "passive"))
      (node (ref "D92") (pin "A") (pinfunction "A_A") (pintype "passive"))
      (node (ref "D93") (pin "A") (pinfunction "A_A") (pintype "passive"))
      (node (ref "D94") (pin "A") (pinfunction "A_A") (pintype "passive"))
      (node (ref "D95") (pin "A") (pinfunction "A_A") (pintype "passive"))
      (node (ref "D96") (pin "A") (pinfunction "A_A") (pintype "passive"))
      (node (ref "D97") (pin "A") (pinfunction "A_A") (pintype "passive"))
      (node (ref "D98") (pin "A") (pinfunction "A_A") (pintype "passive"))
      (node (ref "D99") (pin "A") (pinfunction "A_A") (pintype "passive"))
      (node (ref "E11") (pin "12") (pinfunction "I1_12") (pintype "input"))
      (node (ref "E13") (pin "5") (pinfunction "I1_5") (pintype "input"))
      (node (ref "E13") (pin "6") (pinfunction "I0_6") (pintype "input"))
      (node (ref "E16") (pin "10") (pinfunction "I1_10") (pintype "input"))
      (node (ref "E16") (pin "12") (pinfunction "I1_12") (pintype "input"))
      (node (ref "E16") (pin "5") (pinfunction "I1_5") (pintype "input"))
      (node (ref "E16") (pin "6") (pinfunction "I0_6") (pintype "input"))
      (node (ref "E2") (pin "12") (pinfunction "I1_12") (pintype "input"))
      (node (ref "E2") (pin "6") (pinfunction "I0_6") (pintype "input"))
      (node (ref "E20") (pin "10") (pinfunction "I1_10") (pintype "input"))
      (node (ref "E20") (pin "12") (pinfunction "I1_12") (pintype "input"))
      (node (ref "E20") (pin "5") (pinfunction "I1_5") (pintype "input"))
      (node (ref "E20") (pin "7") (pinfunction "I1_7") (pintype "input"))
      (node (ref "E24") (pin "11") (pinfunction "I0_11") (pintype "input"))
      (node (ref "E24") (pin "5") (pinfunction "I1_5") (pintype "input"))
      (node (ref "E24") (pin "7") (pinfunction "I1_7") (pintype "input"))
      (node (ref "E24") (pin "9") (pinfunction "I0_9") (pintype "input"))
      (node (ref "E28") (pin "11") (pinfunction "I0_11") (pintype "input"))
      (node (ref "E28") (pin "5") (pinfunction "I1_5") (pintype "input"))
      (node (ref "E28") (pin "9") (pinfunction "I0_9") (pintype "input"))
      (node (ref "Q1") (pin "1") (pinfunction "E_1") (pintype "passive"))
      (node (ref "Q10") (pin "1") (pinfunction "E_1") (pintype "passive"))
      (node (ref "Q11") (pin "1") (pinfunction "E_1") (pintype "passive"))
      (node (ref "Q12") (pin "1") (pinfunction "E_1") (pintype "passive"))
      (node (ref "Q13") (pin "3") (pinfunction "C_3") (pintype "passive"))
      (node (ref "Q19") (pin "1") (pinfunction "E_1") (pintype "passive"))
      (node (ref "Q2") (pin "1") (pinfunction "E_1") (pintype "passive"))
      (node (ref "Q3") (pin "1") (pinfunction "E_1") (pintype "passive"))
      (node (ref "Q4") (pin "1") (pinfunction "E_1") (pintype "passive"))
      (node (ref "Q5") (pin "1") (pinfunction "E_1") (pintype "passive"))
      (node (ref "Q6") (pin "1") (pinfunction "E_1") (pintype "passive"))
      (node (ref "Q7") (pin "1") (pinfunction "E_1") (pintype "passive"))
      (node (ref "Q8") (pin "1") (pinfunction "E_1") (pintype "passive"))
      (node (ref "Q9") (pin "1") (pinfunction "E_1") (pintype "passive"))
      (node (ref "R127") (pin "1") (pinfunction "1_1") (pintype "passive"))
      (node (ref "R128") (pin "1") (pinfunction "1_1") (pintype "passive"))
      (node (ref "R129") (pin "1") (pinfunction "1_1") (pintype "passive"))
      (node (ref "R130") (pin "1") (pinfunction "1_1") (pintype "passive"))
      (node (ref "R131") (pin "1") (pinfunction "1_1") (pintype "passive"))
      (node (ref "R132") (pin "1") (pinfunction "1_1") (pintype "passive"))
      (node (ref "R133") (pin "1") (pinfunction "1_1") (pintype "passive"))
      (node (ref "R134") (pin "1") (pinfunction "1_1") (pintype "passive"))
      (node (ref "R135") (pin "1") (pinfunction "1_1") (pintype "passive"))
      (node (ref "R136") (pin "1") (pinfunction "1_1") (pintype "passive"))
      (node (ref "R137") (pin "1") (pinfunction "1_1") (pintype "passive"))
      (node (ref "R138") (pin "1") (pinfunction "1_1") (pintype "passive"))
      (node (ref "R139") (pin "1") (pinfunction "1_1") (pintype "passive"))
      (node (ref "R140") (pin "1") (pinfunction "1_1") (pintype "passive"))
      (node (ref "R141") (pin "1") (pinfunction "1_1") (pintype "passive"))
      (node (ref "R157") (pin "1") (pinfunction "1_1") (pintype "passive"))
      (node (ref "R159") (pin "1") (pinfunction "1_1") (pintype "passive"))
      (node (ref "R160") (pin "1") (pinfunction "1_1") (pintype "passive"))
      (node (ref "R25") (pin "1") (pinfunction "1_1") (pintype "passive"))
      (node (ref "R28") (pin "1") (pinfunction "1_1") (pintype "passive"))
      (node (ref "R31") (pin "1") (pinfunction "1_1") (pintype "passive"))
      (node (ref "R34") (pin "1") (pinfunction "1_1") (pintype "passive"))
      (node (ref "R37") (pin "1") (pinfunction "1_1") (pintype "passive"))
      (node (ref "R40") (pin "1") (pinfunction "1_1") (pintype "passive"))
      (node (ref "R43") (pin "1") (pinfunction "1_1") (pintype "passive"))
      (node (ref "R46") (pin "1") (pinfunction "1_1") (pintype "passive"))
      (node (ref "R49") (pin "1") (pinfunction "1_1") (pintype "passive"))
      (node (ref "R52") (pin "1") (pinfunction "1_1") (pintype "passive"))
      (node (ref "R55") (pin "1") (pinfunction "1_1") (pintype "passive"))
      (node (ref "R58") (pin "1") (pinfunction "1_1") (pintype "passive"))
      (node (ref "U$2") (pin "AC2") (pinfunction "1_AC2") (pintype "bidirectional"))
      (node (ref "U$2") (pin "AF1") (pinfunction "1_AF1") (pintype "bidirectional"))
      (node (ref "U$2") (pin "AF2") (pinfunction "1_AF2") (pintype "bidirectional"))
      (node (ref "U$2") (pin "AN1") (pinfunction "1_AN1") (pintype "bidirectional"))
      (node (ref "U$2") (pin "AN2") (pinfunction "1_AN2") (pintype "bidirectional"))
      (node (ref "U$2") (pin "AT1") (pinfunction "1_AT1") (pintype "bidirectional"))
      (node (ref "U$2") (pin "AT2") (pinfunction "1_AT2") (pintype "bidirectional"))
      (node (ref "U$2") (pin "BC1") (pinfunction "1_BC1") (pintype "bidirectional"))
      (node (ref "U$2") (pin "BC2") (pinfunction "1_BC2") (pintype "bidirectional"))
      (node (ref "U$2") (pin "BF1") (pinfunction "1_BF1") (pintype "bidirectional"))
      (node (ref "U$2") (pin "BF2") (pinfunction "1_BF2") (pintype "bidirectional"))
      (node (ref "U$2") (pin "BN1") (pinfunction "1_BN1") (pintype "bidirectional"))
      (node (ref "U$2") (pin "BN2") (pinfunction "1_BN2") (pintype "bidirectional"))
      (node (ref "U$2") (pin "BT1") (pinfunction "1_BT1") (pintype "bidirectional"))
      (node (ref "U$2") (pin "BT2") (pinfunction "1_BT2") (pintype "bidirectional"))
      (node (ref "U$2") (pin "CC1") (pinfunction "1_CC1") (pintype "bidirectional"))
      (node (ref "U$2") (pin "CC2") (pinfunction "1_CC2") (pintype "bidirectional"))
      (node (ref "U$2") (pin "CF1") (pinfunction "1_CF1") (pintype "bidirectional"))
      (node (ref "U$2") (pin "CF2") (pinfunction "1_CF2") (pintype "bidirectional"))
      (node (ref "U$2") (pin "CN1") (pinfunction "1_CN1") (pintype "bidirectional"))
      (node (ref "U$2") (pin "CN2") (pinfunction "1_CN2") (pintype "bidirectional"))
      (node (ref "U$2") (pin "CT1") (pinfunction "1_CT1") (pintype "bidirectional"))
      (node (ref "U$2") (pin "CT2") (pinfunction "1_CT2") (pintype "bidirectional"))
      (node (ref "U$2") (pin "DC1") (pinfunction "1_DC1") (pintype "bidirectional"))
      (node (ref "U$2") (pin "DC2") (pinfunction "1_DC2") (pintype "bidirectional"))
      (node (ref "U$2") (pin "DF1") (pinfunction "1_DF1") (pintype "bidirectional"))
      (node (ref "U$2") (pin "DF2") (pinfunction "1_DF2") (pintype "bidirectional"))
      (node (ref "U$2") (pin "DT1") (pinfunction "1_DT1") (pintype "bidirectional"))
      (node (ref "U$2") (pin "DT2") (pinfunction "1_DT2") (pintype "bidirectional"))
    )
    (net (code "38") (name "HALT") (class "Default")
      (node (ref "D93") (pin "C") (pinfunction "C_C") (pintype "passive"))
      (node (ref "E11") (pin "10") (pinfunction "I1_10") (pintype "input"))
      (node (ref "R101") (pin "2") (pinfunction "2_2") (pintype "passive"))
    )
    (net (code "39") (name "IND1") (class "Default")
      (node (ref "E7") (pin "1") (pinfunction "O_1") (pintype "open_collector"))
      (node (ref "E7") (pin "4") (pinfunction "O_4") (pintype "open_collector"))
      (node (ref "U$2") (pin "CU2") (pinfunction "1_CU2") (pintype "bidirectional"))
    )
    (net (code "40") (name "IND2") (class "Default")
      (node (ref "E7") (pin "10") (pinfunction "O_10") (pintype "open_collector"))
      (node (ref "U$2") (pin "CV2") (pinfunction "1_CV2") (pintype "bidirectional"))
    )
    (net (code "41") (name "INDSTROBE") (class "Default")
      (node (ref "E18") (pin "10") (pinfunction "I1_10") (pintype "input"))
      (node (ref "E18") (pin "12") (pinfunction "I1_12") (pintype "input"))
      (node (ref "E18") (pin "4") (pinfunction "I0_4") (pintype "input"))
      (node (ref "E18") (pin "6") (pinfunction "I0_6") (pintype "input"))
      (node (ref "E22") (pin "10") (pinfunction "I1_10") (pintype "input"))
      (node (ref "E22") (pin "12") (pinfunction "I1_12") (pintype "input"))
      (node (ref "E22") (pin "4") (pinfunction "I0_4") (pintype "input"))
      (node (ref "E22") (pin "6") (pinfunction "I0_6") (pintype "input"))
      (node (ref "E26") (pin "10") (pinfunction "I1_10") (pintype "input"))
      (node (ref "E26") (pin "12") (pinfunction "I1_12") (pintype "input"))
      (node (ref "E26") (pin "4") (pinfunction "I0_4") (pintype "input"))
      (node (ref "E26") (pin "6") (pinfunction "I0_6") (pintype "input"))
      (node (ref "E9") (pin "4") (pinfunction "O_4") (pintype "output"))
    )
    (net (code "42") (name "INIT") (class "Default")
      (node (ref "E13") (pin "11") (pinfunction "I0_11") (pintype "input"))
      (node (ref "E13") (pin "12") (pinfunction "I1_12") (pintype "input"))
      (node (ref "Q18") (pin "1") (pinfunction "E_1") (pintype "passive"))
      (node (ref "U$2") (pin "CR1") (pinfunction "1_CR1") (pintype "bidirectional"))
    )
    (net (code "43") (name "IR0") (class "Default")
      (node (ref "D76") (pin "A") (pinfunction "A_A") (pintype "passive"))
      (node (ref "E15") (pin "4") (pinfunction "I0_4") (pintype "input"))
      (node (ref "U$2") (pin "DD2") (pinfunction "1_DD2") (pintype "bidirectional"))
    )
    (net (code "44") (name "IR1") (class "Default")
      (node (ref "D77") (pin "A") (pinfunction "A_A") (pintype "passive"))
      (node (ref "E15") (pin "5") (pinfunction "I1_5") (pintype "input"))
      (node (ref "U$2") (pin "DE2") (pinfunction "1_DE2") (pintype "bidirectional"))
    )
    (net (code "45") (name "IR2") (class "Default")
      (node (ref "D78") (pin "A") (pinfunction "A_A") (pintype "passive"))
      (node (ref "E15") (pin "6") (pinfunction "I2_6") (pintype "input"))
      (node (ref "U$2") (pin "DH2") (pinfunction "1_DH2") (pintype "bidirectional"))
    )
    (net (code "46") (name "I{slash}O_PAUSE") (class "Default")
      (node (ref "D82") (pin "A") (pinfunction "A_A") (pintype "passive"))
      (node (ref "U$2") (pin "CD1") (pinfunction "1_CD1") (pintype "bidirectional"))
    )
    (net (code "47") (name "KEY_CONTROL") (class "Default")
      (node (ref "E1") (pin "1") (pinfunction "O_1") (pintype "open_collector"))
      (node (ref "U$2") (pin "DU2") (pinfunction "1_DU2") (pintype "bidirectional"))
    )
    (net (code "48") (name "LA_ENABLE") (class "Default")
      (node (ref "E7") (pin "13") (pinfunction "O_13") (pintype "open_collector"))
      (node (ref "E7") (pin "9") (pinfunction "I1_9") (pintype "input"))
      (node (ref "E9") (pin "9") (pinfunction "I_9") (pintype "input"))
      (node (ref "U$2") (pin "BM2") (pinfunction "1_BM2") (pintype "bidirectional"))
    )
    (net (code "49") (name "LOAD") (class "Default")
      (node (ref "D88") (pin "C") (pinfunction "C_C") (pintype "passive"))
      (node (ref "E12") (pin "4") (pinfunction "I0_4") (pintype "input"))
      (node (ref "E14") (pin "10") (pinfunction "I1_10") (pintype "input"))
      (node (ref "E6") (pin "2") (pinfunction "I1_2") (pintype "input"))
      (node (ref "E8") (pin "9") (pinfunction "I0_9") (pintype "input"))
      (node (ref "R91") (pin "2") (pinfunction "2_2") (pintype "passive"))
    )
    (net (code "50") (name "MA00") (class "Default")
      (node (ref "E24") (pin "6") (pinfunction "I0_6") (pintype "input"))
      (node (ref "U$2") (pin "AD1") (pinfunction "1_AD1") (pintype "bidirectional"))
    )
    (net (code "51") (name "MA01") (class "Default")
      (node (ref "E24") (pin "4") (pinfunction "I0_4") (pintype "input"))
      (node (ref "U$2") (pin "AE1") (pinfunction "1_AE1") (pintype "bidirectional"))
    )
    (net (code "52") (name "MA02") (class "Default")
      (node (ref "E24") (pin "10") (pinfunction "I1_10") (pintype "input"))
      (node (ref "U$2") (pin "AH1") (pinfunction "1_AH1") (pintype "bidirectional"))
    )
    (net (code "53") (name "MA03") (class "Default")
      (node (ref "E24") (pin "12") (pinfunction "I1_12") (pintype "input"))
      (node (ref "U$2") (pin "AJ1") (pinfunction "1_AJ1") (pintype "bidirectional"))
    )
    (net (code "54") (name "MA04") (class "Default")
      (node (ref "E20") (pin "6") (pinfunction "I0_6") (pintype "input"))
      (node (ref "U$2") (pin "BD1") (pinfunction "1_BD1") (pintype "bidirectional"))
    )
    (net (code "55") (name "MA05") (class "Default")
      (node (ref "E20") (pin "4") (pinfunction "I0_4") (pintype "input"))
      (node (ref "U$2") (pin "BE1") (pinfunction "1_BE1") (pintype "bidirectional"))
    )
    (net (code "56") (name "MA06") (class "Default")
      (node (ref "E20") (pin "11") (pinfunction "I0_11") (pintype "input"))
      (node (ref "U$2") (pin "BH1") (pinfunction "1_BH1") (pintype "bidirectional"))
    )
    (net (code "57") (name "MA07") (class "Default")
      (node (ref "E20") (pin "9") (pinfunction "I0_9") (pintype "input"))
      (node (ref "U$2") (pin "BJ1") (pinfunction "1_BJ1") (pintype "bidirectional"))
    )
    (net (code "58") (name "MA08") (class "Default")
      (node (ref "E16") (pin "9") (pinfunction "I0_9") (pintype "input"))
      (node (ref "U$2") (pin "DD1") (pinfunction "1_DD1") (pintype "bidirectional"))
    )
    (net (code "59") (name "MA09") (class "Default")
      (node (ref "E16") (pin "11") (pinfunction "I0_11") (pintype "input"))
      (node (ref "U$2") (pin "DE1") (pinfunction "1_DE1") (pintype "bidirectional"))
    )
    (net (code "60") (name "MA10") (class "Default")
      (node (ref "E16") (pin "7") (pinfunction "I1_7") (pintype "input"))
      (node (ref "U$2") (pin "DH1") (pinfunction "1_DH1") (pintype "bidirectional"))
    )
    (net (code "61") (name "MA11") (class "Default")
      (node (ref "E16") (pin "4") (pinfunction "I0_4") (pintype "input"))
      (node (ref "U$2") (pin "DJ1") (pinfunction "1_DJ1") (pintype "bidirectional"))
    )
    (net (code "62") (name "MD00") (class "Default")
      (node (ref "D49") (pin "A") (pinfunction "A_A") (pintype "passive"))
      (node (ref "U$2") (pin "AK1") (pinfunction "1_AK1") (pintype "bidirectional"))
    )
    (net (code "63") (name "MD01") (class "Default")
      (node (ref "D50") (pin "A") (pinfunction "A_A") (pintype "passive"))
      (node (ref "U$2") (pin "AL1") (pinfunction "1_AL1") (pintype "bidirectional"))
    )
    (net (code "64") (name "MD02") (class "Default")
      (node (ref "D51") (pin "A") (pinfunction "A_A") (pintype "passive"))
      (node (ref "U$2") (pin "AM1") (pinfunction "1_AM1") (pintype "bidirectional"))
    )
    (net (code "65") (name "MD03") (class "Default")
      (node (ref "D52") (pin "A") (pinfunction "A_A") (pintype "passive"))
      (node (ref "E15") (pin "10") (pinfunction "I4_10") (pintype "input"))
      (node (ref "U$2") (pin "AP1") (pinfunction "1_AP1") (pintype "bidirectional"))
    )
    (net (code "66") (name "MD04") (class "Default")
      (node (ref "D53") (pin "A") (pinfunction "A_A") (pintype "passive"))
      (node (ref "U$2") (pin "BK1") (pinfunction "1_BK1") (pintype "bidirectional"))
    )
    (net (code "67") (name "MD05") (class "Default")
      (node (ref "D54") (pin "A") (pinfunction "A_A") (pintype "passive"))
      (node (ref "U$2") (pin "BL1") (pinfunction "1_BL1") (pintype "bidirectional"))
    )
    (net (code "68") (name "MD06") (class "Default")
      (node (ref "D55") (pin "A") (pinfunction "A_A") (pintype "passive"))
      (node (ref "U$2") (pin "BM1") (pinfunction "1_BM1") (pintype "bidirectional"))
    )
    (net (code "69") (name "MD07") (class "Default")
      (node (ref "D56") (pin "A") (pinfunction "A_A") (pintype "passive"))
      (node (ref "U$2") (pin "BP1") (pinfunction "1_BP1") (pintype "bidirectional"))
    )
    (net (code "70") (name "MD08") (class "Default")
      (node (ref "D57") (pin "A") (pinfunction "A_A") (pintype "passive"))
      (node (ref "U$2") (pin "DK1") (pinfunction "1_DK1") (pintype "bidirectional"))
    )
    (net (code "71") (name "MD09") (class "Default")
      (node (ref "D58") (pin "A") (pinfunction "A_A") (pintype "passive"))
      (node (ref "E15") (pin "9") (pinfunction "I3_9") (pintype "input"))
      (node (ref "U$2") (pin "DL1") (pinfunction "1_DL1") (pintype "bidirectional"))
    )
    (net (code "72") (name "MD10") (class "Default")
      (node (ref "D59") (pin "A") (pinfunction "A_A") (pintype "passive"))
      (node (ref "U$2") (pin "DM1") (pinfunction "1_DM1") (pintype "bidirectional"))
    )
    (net (code "73") (name "MD11") (class "Default")
      (node (ref "D60") (pin "A") (pinfunction "A_A") (pintype "passive"))
      (node (ref "E13") (pin "7") (pinfunction "I1_7") (pintype "input"))
      (node (ref "U$2") (pin "DP1") (pinfunction "1_DP1") (pintype "bidirectional"))
    )
    (net (code "74") (name "MD_DIR_IN") (class "Default")
      (node (ref "D79") (pin "A") (pinfunction "A_A") (pintype "passive"))
      (node (ref "E4") (pin "10") (pinfunction "O_10") (pintype "open_collector"))
      (node (ref "U$2") (pin "AK2") (pinfunction "1_AK2") (pintype "bidirectional"))
    )
    (net (code "75") (name "MD_EN") (class "Default")
      (node (ref "R13") (pin "1") (pinfunction "1_1") (pintype "passive"))
      (node (ref "R14") (pin "1") (pinfunction "1_1") (pintype "passive"))
      (node (ref "R142") (pin "1") (pinfunction "1_1") (pintype "passive"))
      (node (ref "R15") (pin "1") (pinfunction "1_1") (pintype "passive"))
      (node (ref "R16") (pin "1") (pinfunction "1_1") (pintype "passive"))
      (node (ref "R17") (pin "1") (pinfunction "1_1") (pintype "passive"))
      (node (ref "R18") (pin "1") (pinfunction "1_1") (pintype "passive"))
      (node (ref "R19") (pin "1") (pinfunction "1_1") (pintype "passive"))
      (node (ref "R20") (pin "1") (pinfunction "1_1") (pintype "passive"))
      (node (ref "R21") (pin "1") (pinfunction "1_1") (pintype "passive"))
      (node (ref "R22") (pin "1") (pinfunction "1_1") (pintype "passive"))
      (node (ref "R23") (pin "1") (pinfunction "1_1") (pintype "passive"))
      (node (ref "R24") (pin "1") (pinfunction "1_1") (pintype "passive"))
      (node (ref "S1") (pin "3") (pinfunction "3_3") (pintype "passive"))
    )
    (net (code "76") (name "MEM_START") (class "Default")
      (node (ref "E1") (pin "13") (pinfunction "O_13") (pintype "open_collector"))
      (node (ref "U$2") (pin "AJ2") (pinfunction "1_AJ2") (pintype "bidirectional"))
    )
    (net (code "77") (name "MQ_EN") (class "Default")
      (node (ref "D108") (pin "C") (pinfunction "C_C") (pintype "passive"))
      (node (ref "D110") (pin "C") (pinfunction "C_C") (pintype "passive"))
      (node (ref "R171") (pin "1") (pinfunction "1_1") (pintype "passive"))
      (node (ref "S1") (pin "2") (pinfunction "2_2") (pintype "passive"))
    )
    (net (code "78") (name "MS_DISABLE") (class "Default")
      (node (ref "E4") (pin "4") (pinfunction "O_4") (pintype "open_collector"))
      (node (ref "U$2") (pin "CV1") (pinfunction "1_CV1") (pintype "bidirectional"))
    )
    (net (code "79") (name "Net-(C13-Pad+)") (class "Default")
      (node (ref "C13") (pin "+") (pinfunction "+_+") (pintype "passive"))
      (node (ref "R153") (pin "2") (pinfunction "2_2") (pintype "passive"))
      (node (ref "R154") (pin "1") (pinfunction "1_1") (pintype "passive"))
    )
    (net (code "80") (name "Net-(D1-PadA)") (class "Default")
      (node (ref "D1") (pin "A") (pinfunction "A_A") (pintype "passive"))
      (node (ref "R26") (pin "2") (pinfunction "2_2") (pintype "passive"))
    )
    (net (code "81") (name "Net-(D2-PadA)") (class "Default")
      (node (ref "D2") (pin "A") (pinfunction "A_A") (pintype "passive"))
      (node (ref "R29") (pin "2") (pinfunction "2_2") (pintype "passive"))
    )
    (net (code "82") (name "Net-(D3-PadA)") (class "Default")
      (node (ref "D3") (pin "A") (pinfunction "A_A") (pintype "passive"))
      (node (ref "R32") (pin "2") (pinfunction "2_2") (pintype "passive"))
    )
    (net (code "83") (name "Net-(D4-PadA)") (class "Default")
      (node (ref "D4") (pin "A") (pinfunction "A_A") (pintype "passive"))
      (node (ref "R35") (pin "2") (pinfunction "2_2") (pintype "passive"))
    )
    (net (code "84") (name "Net-(D5-PadA)") (class "Default")
      (node (ref "D5") (pin "A") (pinfunction "A_A") (pintype "passive"))
      (node (ref "R38") (pin "2") (pinfunction "2_2") (pintype "passive"))
    )
    (net (code "85") (name "Net-(D6-PadA)") (class "Default")
      (node (ref "D6") (pin "A") (pinfunction "A_A") (pintype "passive"))
      (node (ref "R41") (pin "2") (pinfunction "2_2") (pintype "passive"))
    )
    (net (code "86") (name "Net-(D7-PadA)") (class "Default")
      (node (ref "D7") (pin "A") (pinfunction "A_A") (pintype "passive"))
      (node (ref "R44") (pin "2") (pinfunction "2_2") (pintype "passive"))
    )
    (net (code "87") (name "Net-(D8-PadA)") (class "Default")
      (node (ref "D8") (pin "A") (pinfunction "A_A") (pintype "passive"))
      (node (ref "R47") (pin "2") (pinfunction "2_2") (pintype "passive"))
    )
    (net (code "88") (name "Net-(D9-PadA)") (class "Default")
      (node (ref "D9") (pin "A") (pinfunction "A_A") (pintype "passive"))
      (node (ref "R50") (pin "2") (pinfunction "2_2") (pintype "passive"))
    )
    (net (code "89") (name "Net-(D10-PadA)") (class "Default")
      (node (ref "D10") (pin "A") (pinfunction "A_A") (pintype "passive"))
      (node (ref "R53") (pin "2") (pinfunction "2_2") (pintype "passive"))
    )
    (net (code "90") (name "Net-(D11-PadA)") (class "Default")
      (node (ref "D11") (pin "A") (pinfunction "A_A") (pintype "passive"))
      (node (ref "R56") (pin "2") (pinfunction "2_2") (pintype "passive"))
    )
    (net (code "91") (name "Net-(D12-PadA)") (class "Default")
      (node (ref "D12") (pin "A") (pinfunction "A_A") (pintype "passive"))
      (node (ref "R59") (pin "2") (pinfunction "2_2") (pintype "passive"))
    )
    (net (code "92") (name "Net-(D13-PadC)") (class "Default")
      (node (ref "D13") (pin "C") (pinfunction "C_C") (pintype "passive"))
      (node (ref "D60") (pin "C") (pinfunction "C_C") (pintype "passive"))
      (node (ref "R24") (pin "2") (pinfunction "2_2") (pintype "passive"))
    )
    (net (code "93") (name "Net-(D14-PadC)") (class "Default")
      (node (ref "D14") (pin "C") (pinfunction "C_C") (pintype "passive"))
      (node (ref "D59") (pin "C") (pinfunction "C_C") (pintype "passive"))
      (node (ref "R23") (pin "2") (pinfunction "2_2") (pintype "passive"))
    )
    (net (code "94") (name "Net-(D15-PadC)") (class "Default")
      (node (ref "D15") (pin "C") (pinfunction "C_C") (pintype "passive"))
      (node (ref "D58") (pin "C") (pinfunction "C_C") (pintype "passive"))
      (node (ref "R22") (pin "2") (pinfunction "2_2") (pintype "passive"))
    )
    (net (code "95") (name "Net-(D16-PadC)") (class "Default")
      (node (ref "D16") (pin "C") (pinfunction "C_C") (pintype "passive"))
      (node (ref "D57") (pin "C") (pinfunction "C_C") (pintype "passive"))
      (node (ref "R21") (pin "2") (pinfunction "2_2") (pintype "passive"))
    )
    (net (code "96") (name "Net-(D17-PadC)") (class "Default")
      (node (ref "D17") (pin "C") (pinfunction "C_C") (pintype "passive"))
      (node (ref "D56") (pin "C") (pinfunction "C_C") (pintype "passive"))
      (node (ref "R20") (pin "2") (pinfunction "2_2") (pintype "passive"))
    )
    (net (code "97") (name "Net-(D18-PadC)") (class "Default")
      (node (ref "D18") (pin "C") (pinfunction "C_C") (pintype "passive"))
      (node (ref "D55") (pin "C") (pinfunction "C_C") (pintype "passive"))
      (node (ref "R19") (pin "2") (pinfunction "2_2") (pintype "passive"))
    )
    (net (code "98") (name "Net-(D19-PadC)") (class "Default")
      (node (ref "D19") (pin "C") (pinfunction "C_C") (pintype "passive"))
      (node (ref "D54") (pin "C") (pinfunction "C_C") (pintype "passive"))
      (node (ref "R18") (pin "2") (pinfunction "2_2") (pintype "passive"))
    )
    (net (code "99") (name "Net-(D20-PadC)") (class "Default")
      (node (ref "D20") (pin "C") (pinfunction "C_C") (pintype "passive"))
      (node (ref "D53") (pin "C") (pinfunction "C_C") (pintype "passive"))
      (node (ref "R17") (pin "2") (pinfunction "2_2") (pintype "passive"))
    )
    (net (code "100") (name "Net-(D21-PadC)") (class "Default")
      (node (ref "D21") (pin "C") (pinfunction "C_C") (pintype "passive"))
      (node (ref "D52") (pin "C") (pinfunction "C_C") (pintype "passive"))
      (node (ref "R16") (pin "2") (pinfunction "2_2") (pintype "passive"))
    )
    (net (code "101") (name "Net-(D22-PadC)") (class "Default")
      (node (ref "D22") (pin "C") (pinfunction "C_C") (pintype "passive"))
      (node (ref "D51") (pin "C") (pinfunction "C_C") (pintype "passive"))
      (node (ref "R15") (pin "2") (pinfunction "2_2") (pintype "passive"))
    )
    (net (code "102") (name "Net-(D23-PadC)") (class "Default")
      (node (ref "D23") (pin "C") (pinfunction "C_C") (pintype "passive"))
      (node (ref "D50") (pin "C") (pinfunction "C_C") (pintype "passive"))
      (node (ref "R14") (pin "2") (pinfunction "2_2") (pintype "passive"))
    )
    (net (code "103") (name "Net-(D24-PadC)") (class "Default")
      (node (ref "D24") (pin "C") (pinfunction "C_C") (pintype "passive"))
      (node (ref "D49") (pin "C") (pinfunction "C_C") (pintype "passive"))
      (node (ref "R13") (pin "2") (pinfunction "2_2") (pintype "passive"))
    )
    (net (code "104") (name "Net-(D25-PadC)") (class "Default")
      (node (ref "D25") (pin "C") (pinfunction "C_C") (pintype "passive"))
      (node (ref "D72") (pin "C") (pinfunction "C_C") (pintype "passive"))
      (node (ref "R84") (pin "1") (pinfunction "1_1") (pintype "passive"))
    )
    (net (code "105") (name "Net-(D26-PadC)") (class "Default")
      (node (ref "D26") (pin "C") (pinfunction "C_C") (pintype "passive"))
      (node (ref "D71") (pin "C") (pinfunction "C_C") (pintype "passive"))
      (node (ref "R82") (pin "1") (pinfunction "1_1") (pintype "passive"))
    )
    (net (code "106") (name "Net-(D27-PadC)") (class "Default")
      (node (ref "D27") (pin "C") (pinfunction "C_C") (pintype "passive"))
      (node (ref "D70") (pin "C") (pinfunction "C_C") (pintype "passive"))
      (node (ref "R80") (pin "1") (pinfunction "1_1") (pintype "passive"))
    )
    (net (code "107") (name "Net-(D28-PadC)") (class "Default")
      (node (ref "D28") (pin "C") (pinfunction "C_C") (pintype "passive"))
      (node (ref "D69") (pin "C") (pinfunction "C_C") (pintype "passive"))
      (node (ref "R78") (pin "1") (pinfunction "1_1") (pintype "passive"))
    )
    (net (code "108") (name "Net-(D29-PadC)") (class "Default")
      (node (ref "D29") (pin "C") (pinfunction "C_C") (pintype "passive"))
      (node (ref "D68") (pin "C") (pinfunction "C_C") (pintype "passive"))
      (node (ref "R76") (pin "1") (pinfunction "1_1") (pintype "passive"))
    )
    (net (code "109") (name "Net-(D30-PadC)") (class "Default")
      (node (ref "D30") (pin "C") (pinfunction "C_C") (pintype "passive"))
      (node (ref "D67") (pin "C") (pinfunction "C_C") (pintype "passive"))
      (node (ref "R74") (pin "1") (pinfunction "1_1") (pintype "passive"))
    )
    (net (code "110") (name "Net-(D31-PadC)") (class "Default")
      (node (ref "D31") (pin "C") (pinfunction "C_C") (pintype "passive"))
      (node (ref "D66") (pin "C") (pinfunction "C_C") (pintype "passive"))
      (node (ref "R72") (pin "1") (pinfunction "1_1") (pintype "passive"))
    )
    (net (code "111") (name "Net-(D32-PadC)") (class "Default")
      (node (ref "D32") (pin "C") (pinfunction "C_C") (pintype "passive"))
      (node (ref "D65") (pin "C") (pinfunction "C_C") (pintype "passive"))
      (node (ref "R70") (pin "1") (pinfunction "1_1") (pintype "passive"))
    )
    (net (code "112") (name "Net-(D33-PadC)") (class "Default")
      (node (ref "D33") (pin "C") (pinfunction "C_C") (pintype "passive"))
      (node (ref "D64") (pin "C") (pinfunction "C_C") (pintype "passive"))
      (node (ref "R68") (pin "1") (pinfunction "1_1") (pintype "passive"))
    )
    (net (code "113") (name "Net-(D34-PadC)") (class "Default")
      (node (ref "D34") (pin "C") (pinfunction "C_C") (pintype "passive"))
      (node (ref "D63") (pin "C") (pinfunction "C_C") (pintype "passive"))
      (node (ref "R66") (pin "1") (pinfunction "1_1") (pintype "passive"))
    )
    (net (code "114") (name "Net-(D35-PadC)") (class "Default")
      (node (ref "D35") (pin "C") (pinfunction "C_C") (pintype "passive"))
      (node (ref "D62") (pin "C") (pinfunction "C_C") (pintype "passive"))
      (node (ref "R64") (pin "1") (pinfunction "1_1") (pintype "passive"))
    )
    (net (code "115") (name "Net-(D36-PadC)") (class "Default")
      (node (ref "D36") (pin "C") (pinfunction "C_C") (pintype "passive"))
      (node (ref "D61") (pin "C") (pinfunction "C_C") (pintype "passive"))
      (node (ref "R62") (pin "1") (pinfunction "1_1") (pintype "passive"))
    )
    (net (code "116") (name "Net-(D37-PadC)") (class "Default")
      (node (ref "D37") (pin "C") (pinfunction "C_C") (pintype "passive"))
      (node (ref "D84") (pin "C") (pinfunction "C_C") (pintype "passive"))
      (node (ref "R83") (pin "1") (pinfunction "1_1") (pintype "passive"))
    )
    (net (code "117") (name "Net-(D38-PadC)") (class "Default")
      (node (ref "D38") (pin "C") (pinfunction "C_C") (pintype "passive"))
      (node (ref "D83") (pin "C") (pinfunction "C_C") (pintype "passive"))
      (node (ref "R81") (pin "1") (pinfunction "1_1") (pintype "passive"))
    )
    (net (code "118") (name "Net-(D39-PadC)") (class "Default")
      (node (ref "D39") (pin "C") (pinfunction "C_C") (pintype "passive"))
      (node (ref "D82") (pin "C") (pinfunction "C_C") (pintype "passive"))
      (node (ref "R79") (pin "1") (pinfunction "1_1") (pintype "passive"))
    )
    (net (code "119") (name "Net-(D40-PadC)") (class "Default")
      (node (ref "D40") (pin "C") (pinfunction "C_C") (pintype "passive"))
      (node (ref "D81") (pin "C") (pinfunction "C_C") (pintype "passive"))
      (node (ref "R77") (pin "1") (pinfunction "1_1") (pintype "passive"))
    )
    (net (code "120") (name "Net-(D41-PadC)") (class "Default")
      (node (ref "D41") (pin "C") (pinfunction "C_C") (pintype "passive"))
      (node (ref "D80") (pin "C") (pinfunction "C_C") (pintype "passive"))
      (node (ref "R75") (pin "1") (pinfunction "1_1") (pintype "passive"))
    )
    (net (code "121") (name "Net-(D42-PadC)") (class "Default")
      (node (ref "D42") (pin "C") (pinfunction "C_C") (pintype "passive"))
      (node (ref "D79") (pin "C") (pinfunction "C_C") (pintype "passive"))
      (node (ref "R73") (pin "1") (pinfunction "1_1") (pintype "passive"))
    )
    (net (code "122") (name "Net-(D43-PadC)") (class "Default")
      (node (ref "D43") (pin "C") (pinfunction "C_C") (pintype "passive"))
      (node (ref "D78") (pin "C") (pinfunction "C_C") (pintype "passive"))
      (node (ref "R71") (pin "1") (pinfunction "1_1") (pintype "passive"))
    )
    (net (code "123") (name "Net-(D44-PadC)") (class "Default")
      (node (ref "D44") (pin "C") (pinfunction "C_C") (pintype "passive"))
      (node (ref "D77") (pin "C") (pinfunction "C_C") (pintype "passive"))
      (node (ref "R69") (pin "1") (pinfunction "1_1") (pintype "passive"))
    )
    (net (code "124") (name "Net-(D45-PadC)") (class "Default")
      (node (ref "D45") (pin "C") (pinfunction "C_C") (pintype "passive"))
      (node (ref "D76") (pin "C") (pinfunction "C_C") (pintype "passive"))
      (node (ref "R67") (pin "1") (pinfunction "1_1") (pintype "passive"))
    )
    (net (code "125") (name "Net-(D46-PadC)") (class "Default")
      (node (ref "D46") (pin "C") (pinfunction "C_C") (pintype "passive"))
      (node (ref "D75") (pin "C") (pinfunction "C_C") (pintype "passive"))
      (node (ref "R65") (pin "1") (pinfunction "1_1") (pintype "passive"))
    )
    (net (code "126") (name "Net-(D47-PadC)") (class "Default")
      (node (ref "D47") (pin "C") (pinfunction "C_C") (pintype "passive"))
      (node (ref "D74") (pin "C") (pinfunction "C_C") (pintype "passive"))
      (node (ref "R63") (pin "1") (pinfunction "1_1") (pintype "passive"))
    )
    (net (code "127") (name "Net-(D48-PadC)") (class "Default")
      (node (ref "D48") (pin "C") (pinfunction "C_C") (pintype "passive"))
      (node (ref "D73") (pin "C") (pinfunction "C_C") (pintype "passive"))
      (node (ref "R61") (pin "1") (pinfunction "1_1") (pintype "passive"))
    )
    (net (code "128") (name "Net-(D110-PadA)") (class "Default")
      (node (ref "D110") (pin "A") (pinfunction "A_A") (pintype "passive"))
      (node (ref "D111") (pin "A") (pinfunction "A_A") (pintype "passive"))
      (node (ref "R150") (pin "1") (pinfunction "1_1") (pintype "passive"))
    )
    (net (code "129") (name "Net-(D112-PadA)") (class "Default")
      (node (ref "D112") (pin "A") (pinfunction "A_A") (pintype "passive"))
      (node (ref "D113") (pin "A") (pinfunction "A_A") (pintype "passive"))
      (node (ref "R149") (pin "1") (pinfunction "1_1") (pintype "passive"))
    )
    (net (code "130") (name "Net-(D116-PadC)") (class "Default")
      (node (ref "D116") (pin "C") (pinfunction "C_C") (pintype "passive"))
      (node (ref "D117") (pin "A") (pinfunction "A_A") (pintype "passive"))
    )
    (net (code "131") (name "Net-(D118-PadA)") (class "Default")
      (node (ref "D118") (pin "A") (pinfunction "A_A") (pintype "passive"))
      (node (ref "D119") (pin "C") (pinfunction "C_C") (pintype "passive"))
    )
    (net (code "132") (name "Net-(D122-PadA)") (class "Default")
      (node (ref "D122") (pin "A") (pinfunction "A_A") (pintype "passive"))
      (node (ref "R169") (pin "2") (pinfunction "2_2") (pintype "passive"))
    )
    (net (code "133") (name "Net-(D123-PadC)") (class "Default")
      (node (ref "D123") (pin "C") (pinfunction "C_C") (pintype "passive"))
      (node (ref "D124") (pin "A") (pinfunction "A_A") (pintype "passive"))
    )
    (net (code "134") (name "Net-(D124-PadC)") (class "Default")
      (node (ref "D124") (pin "C") (pinfunction "C_C") (pintype "passive"))
      (node (ref "D125") (pin "A") (pinfunction "A_A") (pintype "passive"))
    )
    (net (code "135") (name "Net-(E1A-I0)") (class "Default")
      (node (ref "E1") (pin "2") (pinfunction "I0_2") (pintype "input"))
      (node (ref "E8") (pin "12") (pinfunction "O_12") (pintype "output"))
    )
    (net (code "136") (name "Net-(E1D-I0)") (class "Default")
      (node (ref "E1") (pin "11") (pinfunction "I0_11") (pintype "input"))
      (node (ref "E2") (pin "10") (pinfunction "I1_10") (pintype "input"))
      (node (ref "E2") (pin "13") (pinfunction "O_13") (pintype "output"))
      (node (ref "E3") (pin "1") (pinfunction "I0_1") (pintype "input"))
      (node (ref "E3") (pin "4") (pinfunction "I0_4") (pintype "input"))
    )
    (net (code "137") (name "Net-(E2A-O)") (class "Default")
      (node (ref "E2") (pin "3") (pinfunction "O_3") (pintype "output"))
      (node (ref "E6") (pin "12") (pinfunction "I0_12") (pintype "input"))
    )
    (net (code "138") (name "Net-(E2B-O)") (class "Default")
      (node (ref "E2") (pin "2") (pinfunction "O_2") (pintype "output"))
      (node (ref "E3") (pin "13") (pinfunction "I1_13") (pintype "input"))
    )
    (net (code "139") (name "Net-(E2C-I0)") (class "Default")
      (node (ref "C14") (pin "1") (pinfunction "1_1") (pintype "passive"))
      (node (ref "E2") (pin "9") (pinfunction "I0_9") (pintype "input"))
      (node (ref "R159") (pin "2") (pinfunction "2_2") (pintype "passive"))
      (node (ref "R160") (pin "2") (pinfunction "2_2") (pintype "passive"))
    )
    (net (code "140") (name "Net-(E2C-O)") (class "Default")
      (node (ref "C15") (pin "2") (pinfunction "2_2") (pintype "passive"))
      (node (ref "E2") (pin "14") (pinfunction "O_14") (pintype "output"))
    )
    (net (code "141") (name "Net-(E2D-I0)") (class "Default")
      (node (ref "C15") (pin "1") (pinfunction "1_1") (pintype "passive"))
      (node (ref "D121") (pin "A") (pinfunction "A_A") (pintype "passive"))
      (node (ref "E2") (pin "11") (pinfunction "I0_11") (pintype "input"))
      (node (ref "R161") (pin "1") (pinfunction "1_1") (pintype "passive"))
    )
    (net (code "142") (name "Net-(E3C-I0)") (class "Default")
      (node (ref "E3") (pin "12") (pinfunction "I0_12") (pintype "input"))
      (node (ref "E3") (pin "9") (pinfunction "I0_9") (pintype "input"))
      (node (ref "E5") (pin "8") (pinfunction "O_8") (pintype "output"))
    )
    (net (code "143") (name "Net-(E3C-I1)") (class "Default")
      (node (ref "E3") (pin "10") (pinfunction "I1_10") (pintype "input"))
      (node (ref "E3") (pin "11") (pinfunction "O_11") (pintype "output"))
    )
    (net (code "144") (name "Net-(E3C-O)") (class "Default")
      (node (ref "E3") (pin "8") (pinfunction "O_8") (pintype "output"))
      (node (ref "E9") (pin "3") (pinfunction "I_3") (pintype "input"))
    )
    (net (code "145") (name "Net-(E4B-I0)") (class "Default")
      (node (ref "E4") (pin "5") (pinfunction "I0_5") (pintype "input"))
      (node (ref "E6") (pin "8") (pinfunction "O_8") (pintype "output"))
    )
    (net (code "146") (name "Net-(E4D-I0)") (class "Default")
      (node (ref "E4") (pin "11") (pinfunction "I0_11") (pintype "input"))
      (node (ref "E4") (pin "12") (pinfunction "I1_12") (pintype "input"))
      (node (ref "E6") (pin "6") (pinfunction "O_6") (pintype "output"))
    )
    (net (code "147") (name "Net-(E5C-I0)") (class "Default")
      (node (ref "D109") (pin "C") (pinfunction "C_C") (pintype "passive"))
      (node (ref "E5") (pin "9") (pinfunction "I0_9") (pintype "input"))
      (node (ref "R147") (pin "1") (pinfunction "1_1") (pintype "passive"))
      (node (ref "R148") (pin "2") (pinfunction "2_2") (pintype "passive"))
    )
    (net (code "148") (name "Net-(E5C-I1)") (class "Default")
      (node (ref "D128") (pin "C") (pinfunction "C_C") (pintype "passive"))
      (node (ref "E5") (pin "10") (pinfunction "I1_10") (pintype "input"))
      (node (ref "R146") (pin "1") (pinfunction "1_1") (pintype "passive"))
      (node (ref "R171") (pin "2") (pinfunction "2_2") (pintype "passive"))
    )
    (net (code "149") (name "Net-(E5C-I2)") (class "Default")
      (node (ref "D127") (pin "C") (pinfunction "C_C") (pintype "passive"))
      (node (ref "E5") (pin "11") (pinfunction "I2_11") (pintype "input"))
      (node (ref "R144") (pin "1") (pinfunction "1_1") (pintype "passive"))
      (node (ref "R173") (pin "2") (pinfunction "2_2") (pintype "passive"))
    )
    (net (code "150") (name "Net-(E7A-I0)") (class "Default")
      (node (ref "E7") (pin "2") (pinfunction "I0_2") (pintype "input"))
      (node (ref "E7") (pin "3") (pinfunction "I1_3") (pintype "input"))
      (node (ref "E9") (pin "10") (pinfunction "O_10") (pintype "output"))
    )
    (net (code "151") (name "Net-(E7B-I0)") (class "Default")
      (node (ref "E7") (pin "5") (pinfunction "I0_5") (pintype "input"))
      (node (ref "E7") (pin "6") (pinfunction "I1_6") (pintype "input"))
      (node (ref "E9") (pin "8") (pinfunction "O_8") (pintype "output"))
    )
    (net (code "152") (name "Net-(E7C-I0)") (class "Default")
      (node (ref "E7") (pin "8") (pinfunction "I0_8") (pintype "input"))
      (node (ref "E9") (pin "6") (pinfunction "O_6") (pintype "output"))
    )
    (net (code "153") (name "Net-(E8B-I1)") (class "Default")
      (node (ref "E8") (pin "4") (pinfunction "I1_4") (pintype "input"))
      (node (ref "E8") (pin "8") (pinfunction "O_8") (pintype "output"))
    )
    (net (code "154") (name "Net-(E9A-O)") (class "Default")
      (node (ref "E9") (pin "2") (pinfunction "O_2") (pintype "output"))
      (node (ref "R166") (pin "1") (pinfunction "1_1") (pintype "passive"))
    )
    (net (code "155") (name "Net-(E9C-I)") (class "Default")
      (node (ref "D114") (pin "C") (pinfunction "C_C") (pintype "passive"))
      (node (ref "E9") (pin "5") (pinfunction "I_5") (pintype "input"))
      (node (ref "R150") (pin "2") (pinfunction "2_2") (pintype "passive"))
      (node (ref "R151") (pin "1") (pinfunction "1_1") (pintype "passive"))
    )
    (net (code "156") (name "Net-(E9E-I)") (class "Default")
      (node (ref "D115") (pin "C") (pinfunction "C_C") (pintype "passive"))
      (node (ref "E9") (pin "11") (pinfunction "I_11") (pintype "input"))
      (node (ref "R149") (pin "2") (pinfunction "2_2") (pintype "passive"))
      (node (ref "R152") (pin "1") (pinfunction "1_1") (pintype "passive"))
    )
    (net (code "157") (name "Net-(E10A-I)") (class "Default")
      (node (ref "E10") (pin "1") (pinfunction "I_1") (pintype "input"))
      (node (ref "E12") (pin "3") (pinfunction "O_3") (pintype "output"))
    )
    (net (code "158") (name "Net-(E10B-O)") (class "Default")
      (node (ref "E10") (pin "4") (pinfunction "O_4") (pintype "output"))
      (node (ref "E14") (pin "12") (pinfunction "I2_12") (pintype "input"))
    )
    (net (code "159") (name "Net-(E10C-O)") (class "Default")
      (node (ref "E10") (pin "6") (pinfunction "O_6") (pintype "output"))
      (node (ref "E3") (pin "5") (pinfunction "I1_5") (pintype "input"))
    )
    (net (code "160") (name "Net-(E10D-I)") (class "Default")
      (node (ref "E10") (pin "9") (pinfunction "I_9") (pintype "input"))
      (node (ref "E3") (pin "6") (pinfunction "O_6") (pintype "output"))
    )
    (net (code "161") (name "Net-(E10D-O)") (class "Default")
      (node (ref "E10") (pin "8") (pinfunction "O_8") (pintype "output"))
      (node (ref "R164") (pin "1") (pinfunction "1_1") (pintype "passive"))
      (node (ref "R174") (pin "1") (pinfunction "1_1") (pintype "passive"))
    )
    (net (code "162") (name "Net-(E10E-I)") (class "Default")
      (node (ref "E10") (pin "11") (pinfunction "I_11") (pintype "input"))
      (node (ref "E3") (pin "3") (pinfunction "O_3") (pintype "output"))
    )
    (net (code "163") (name "Net-(E10E-O)") (class "Default")
      (node (ref "E10") (pin "10") (pinfunction "O_10") (pintype "output"))
      (node (ref "R162") (pin "1") (pinfunction "1_1") (pintype "passive"))
      (node (ref "R172") (pin "1") (pinfunction "1_1") (pintype "passive"))
    )
    (net (code "164") (name "Net-(E10F-I)") (class "Default")
      (node (ref "E10") (pin "13") (pinfunction "I_13") (pintype "input"))
      (node (ref "E4") (pin "2") (pinfunction "I0_2") (pintype "input"))
      (node (ref "E4") (pin "9") (pinfunction "I1_9") (pintype "input"))
      (node (ref "E6") (pin "3") (pinfunction "O_3") (pintype "output"))
    )
    (net (code "165") (name "Net-(E10F-O)") (class "Default")
      (node (ref "E10") (pin "12") (pinfunction "O_12") (pintype "output"))
      (node (ref "E6") (pin "9") (pinfunction "I0_9") (pintype "input"))
    )
    (net (code "166") (name "Net-(E11B-O)") (class "Default")
      (node (ref "E11") (pin "2") (pinfunction "O_2") (pintype "output"))
      (node (ref "E12") (pin "1") (pinfunction "I0_1") (pintype "input"))
    )
    (net (code "167") (name "Net-(E11C-O)") (class "Default")
      (node (ref "E11") (pin "14") (pinfunction "O_14") (pintype "output"))
      (node (ref "E6") (pin "4") (pinfunction "I0_4") (pintype "input"))
    )
    (net (code "168") (name "Net-(E11D-O)") (class "Default")
      (node (ref "E11") (pin "13") (pinfunction "O_13") (pintype "output"))
      (node (ref "E8") (pin "3") (pinfunction "I0_3") (pintype "input"))
    )
    (net (code "169") (name "Net-(E12A-I1)") (class "Default")
      (node (ref "E12") (pin "2") (pinfunction "I1_2") (pintype "input"))
      (node (ref "E14") (pin "8") (pinfunction "O_8") (pintype "output"))
    )
    (net (code "170") (name "Net-(E12B-O)") (class "Default")
      (node (ref "E12") (pin "6") (pinfunction "O_6") (pintype "output"))
      (node (ref "E3") (pin "2") (pinfunction "I1_2") (pintype "input"))
      (node (ref "E7") (pin "12") (pinfunction "I1_12") (pintype "input"))
    )
    (net (code "171") (name "Net-(E12C-I0)") (class "Default")
      (node (ref "E12") (pin "12") (pinfunction "I0_12") (pintype "input"))
      (node (ref "E12") (pin "9") (pinfunction "I0_9") (pintype "input"))
      (node (ref "E5") (pin "12") (pinfunction "O_12") (pintype "output"))
    )
    (net (code "172") (name "Net-(E12C-I1)") (class "Default")
      (node (ref "E12") (pin "10") (pinfunction "I1_10") (pintype "input"))
      (node (ref "E12") (pin "11") (pinfunction "O_11") (pintype "output"))
    )
    (net (code "173") (name "Net-(E13A-O)") (class "Default")
      (node (ref "E13") (pin "3") (pinfunction "O_3") (pintype "output"))
      (node (ref "E15") (pin "11") (pinfunction "I5_11") (pintype "input"))
    )
    (net (code "174") (name "Net-(E13B-O)") (class "Default")
      (node (ref "E13") (pin "2") (pinfunction "O_2") (pintype "output"))
      (node (ref "E15") (pin "12") (pinfunction "I6_12") (pintype "input"))
    )
    (net (code "175") (name "Net-(E13C-O)") (class "Default")
      (node (ref "E13") (pin "14") (pinfunction "O_14") (pintype "output"))
      (node (ref "E5") (pin "1") (pinfunction "I0_1") (pintype "input"))
    )
    (net (code "176") (name "Net-(E13D-O)") (class "Default")
      (node (ref "E13") (pin "13") (pinfunction "O_13") (pintype "output"))
      (node (ref "E5") (pin "2") (pinfunction "I1_2") (pintype "input"))
    )
    (net (code "177") (name "Net-(E14A-I0)") (class "Default")
      (node (ref "E14") (pin "1") (pinfunction "I0_1") (pintype "input"))
      (node (ref "E14") (pin "2") (pinfunction "I1_2") (pintype "input"))
      (node (ref "E6") (pin "11") (pinfunction "O_11") (pintype "output"))
    )
    (net (code "178") (name "Net-(E14A-I2)") (class "Default")
      (node (ref "E14") (pin "4") (pinfunction "I2_4") (pintype "input"))
      (node (ref "E14") (pin "5") (pinfunction "I3_5") (pintype "input"))
      (node (ref "E8") (pin "6") (pinfunction "O_6") (pintype "output"))
    )
    (net (code "179") (name "Net-(E14A-O)") (class "Default")
      (node (ref "E14") (pin "6") (pinfunction "O_6") (pintype "output"))
      (node (ref "E17") (pin "12") (pinfunction "I1_12") (pintype "input"))
      (node (ref "E17") (pin "2") (pinfunction "I0_2") (pintype "input"))
      (node (ref "E17") (pin "5") (pinfunction "I0_5") (pintype "input"))
      (node (ref "E17") (pin "9") (pinfunction "I1_9") (pintype "input"))
      (node (ref "E21") (pin "12") (pinfunction "I1_12") (pintype "input"))
      (node (ref "E21") (pin "2") (pinfunction "I0_2") (pintype "input"))
      (node (ref "E21") (pin "5") (pinfunction "I0_5") (pintype "input"))
      (node (ref "E21") (pin "9") (pinfunction "I1_9") (pintype "input"))
      (node (ref "E25") (pin "11") (pinfunction "I0_11") (pintype "input"))
      (node (ref "E25") (pin "2") (pinfunction "I0_2") (pintype "input"))
      (node (ref "E25") (pin "5") (pinfunction "I0_5") (pintype "input"))
      (node (ref "E25") (pin "9") (pinfunction "I1_9") (pintype "input"))
    )
    (net (code "180") (name "Net-(E15A-O)") (class "Default")
      (node (ref "E15") (pin "3") (pinfunction "O_3") (pintype "output"))
      (node (ref "E6") (pin "13") (pinfunction "I1_13") (pintype "input"))
    )
    (net (code "181") (name "Net-(E16A-O)") (class "Default")
      (node (ref "E16") (pin "3") (pinfunction "O_3") (pintype "output"))
      (node (ref "E19") (pin "9") (pinfunction "I_9") (pintype "input"))
    )
    (net (code "182") (name "Net-(E16B-O)") (class "Default")
      (node (ref "E16") (pin "2") (pinfunction "O_2") (pintype "output"))
      (node (ref "E19") (pin "11") (pinfunction "I_11") (pintype "input"))
    )
    (net (code "183") (name "Net-(E16C-O)") (class "Default")
      (node (ref "E16") (pin "14") (pinfunction "O_14") (pintype "output"))
      (node (ref "E19") (pin "1") (pinfunction "I_1") (pintype "input"))
    )
    (net (code "184") (name "Net-(E16D-O)") (class "Default")
      (node (ref "E16") (pin "13") (pinfunction "O_13") (pintype "output"))
      (node (ref "E19") (pin "13") (pinfunction "I_13") (pintype "input"))
    )
    (net (code "185") (name "Net-(E17A-I1)") (class "Default")
      (node (ref "D102") (pin "C") (pinfunction "C_C") (pintype "passive"))
      (node (ref "E17") (pin "3") (pinfunction "I1_3") (pintype "input"))
      (node (ref "R119") (pin "2") (pinfunction "2_2") (pintype "passive"))
    )
    (net (code "186") (name "Net-(E17B-I1)") (class "Default")
      (node (ref "D103") (pin "C") (pinfunction "C_C") (pintype "passive"))
      (node (ref "E17") (pin "6") (pinfunction "I1_6") (pintype "input"))
      (node (ref "R121") (pin "2") (pinfunction "2_2") (pintype "passive"))
    )
    (net (code "187") (name "Net-(E17C-I0)") (class "Default")
      (node (ref "D105") (pin "C") (pinfunction "C_C") (pintype "passive"))
      (node (ref "E17") (pin "8") (pinfunction "I0_8") (pintype "input"))
      (node (ref "R125") (pin "2") (pinfunction "2_2") (pintype "passive"))
    )
    (net (code "188") (name "Net-(E17D-I0)") (class "Default")
      (node (ref "D104") (pin "C") (pinfunction "C_C") (pintype "passive"))
      (node (ref "E17") (pin "11") (pinfunction "I0_11") (pintype "input"))
      (node (ref "R123") (pin "2") (pinfunction "2_2") (pintype "passive"))
    )
    (net (code "189") (name "Net-(E18A-I1)") (class "Default")
      (node (ref "D16") (pin "A") (pinfunction "A_A") (pintype "passive"))
      (node (ref "D28") (pin "A") (pinfunction "A_A") (pintype "passive"))
      (node (ref "D40") (pin "A") (pinfunction "A_A") (pintype "passive"))
      (node (ref "E18") (pin "5") (pinfunction "I1_5") (pintype "input"))
      (node (ref "R9") (pin "1") (pinfunction "1_1") (pintype "passive"))
    )
    (net (code "190") (name "Net-(E18A-O)") (class "Default")
      (node (ref "E18") (pin "3") (pinfunction "O_3") (pintype "output"))
      (node (ref "R50") (pin "1") (pinfunction "1_1") (pintype "passive"))
      (node (ref "R51") (pin "1") (pinfunction "1_1") (pintype "passive"))
    )
    (net (code "191") (name "Net-(E18B-I1)") (class "Default")
      (node (ref "D15") (pin "A") (pinfunction "A_A") (pintype "passive"))
      (node (ref "D27") (pin "A") (pinfunction "A_A") (pintype "passive"))
      (node (ref "D39") (pin "A") (pinfunction "A_A") (pintype "passive"))
      (node (ref "E18") (pin "7") (pinfunction "I1_7") (pintype "input"))
      (node (ref "R10") (pin "1") (pinfunction "1_1") (pintype "passive"))
    )
    (net (code "192") (name "Net-(E18B-O)") (class "Default")
      (node (ref "E18") (pin "2") (pinfunction "O_2") (pintype "output"))
      (node (ref "R53") (pin "1") (pinfunction "1_1") (pintype "passive"))
      (node (ref "R54") (pin "1") (pinfunction "1_1") (pintype "passive"))
    )
    (net (code "193") (name "Net-(E18C-I0)") (class "Default")
      (node (ref "D13") (pin "A") (pinfunction "A_A") (pintype "passive"))
      (node (ref "D25") (pin "A") (pinfunction "A_A") (pintype "passive"))
      (node (ref "D37") (pin "A") (pinfunction "A_A") (pintype "passive"))
      (node (ref "E18") (pin "9") (pinfunction "I0_9") (pintype "input"))
      (node (ref "R12") (pin "1") (pinfunction "1_1") (pintype "passive"))
    )
    (net (code "194") (name "Net-(E18C-O)") (class "Default")
      (node (ref "E18") (pin "14") (pinfunction "O_14") (pintype "output"))
      (node (ref "R59") (pin "1") (pinfunction "1_1") (pintype "passive"))
      (node (ref "R60") (pin "1") (pinfunction "1_1") (pintype "passive"))
    )
    (net (code "195") (name "Net-(E18D-I0)") (class "Default")
      (node (ref "D14") (pin "A") (pinfunction "A_A") (pintype "passive"))
      (node (ref "D26") (pin "A") (pinfunction "A_A") (pintype "passive"))
      (node (ref "D38") (pin "A") (pinfunction "A_A") (pintype "passive"))
      (node (ref "E18") (pin "11") (pinfunction "I0_11") (pintype "input"))
      (node (ref "R11") (pin "1") (pinfunction "1_1") (pintype "passive"))
    )
    (net (code "196") (name "Net-(E18D-O)") (class "Default")
      (node (ref "E18") (pin "13") (pinfunction "O_13") (pintype "output"))
      (node (ref "R56") (pin "1") (pinfunction "1_1") (pintype "passive"))
      (node (ref "R57") (pin "1") (pinfunction "1_1") (pintype "passive"))
    )
    (net (code "197") (name "Net-(E19A-O)") (class "Default")
      (node (ref "E19") (pin "2") (pinfunction "O_2") (pintype "open_collector"))
      (node (ref "I24") (pin "A") (pinfunction "A_A") (pintype "passive"))
      (node (ref "R135") (pin "2") (pinfunction "2_2") (pintype "passive"))
    )
    (net (code "198") (name "Net-(E19B-I)") (class "Default")
      (node (ref "E19") (pin "3") (pinfunction "I_3") (pintype "input"))
      (node (ref "E20") (pin "14") (pinfunction "O_14") (pintype "output"))
    )
    (net (code "199") (name "Net-(E19B-O)") (class "Default")
      (node (ref "E19") (pin "4") (pinfunction "O_4") (pintype "open_collector"))
      (node (ref "I23") (pin "A") (pinfunction "A_A") (pintype "passive"))
      (node (ref "R134") (pin "2") (pinfunction "2_2") (pintype "passive"))
    )
    (net (code "200") (name "Net-(E19C-I)") (class "Default")
      (node (ref "E19") (pin "5") (pinfunction "I_5") (pintype "input"))
      (node (ref "E20") (pin "13") (pinfunction "O_13") (pintype "output"))
    )
    (net (code "201") (name "Net-(E19C-O)") (class "Default")
      (node (ref "E19") (pin "6") (pinfunction "O_6") (pintype "open_collector"))
      (node (ref "I22") (pin "A") (pinfunction "A_A") (pintype "passive"))
      (node (ref "R133") (pin "2") (pinfunction "2_2") (pintype "passive"))
    )
    (net (code "202") (name "Net-(E19D-O)") (class "Default")
      (node (ref "E19") (pin "8") (pinfunction "O_8") (pintype "open_collector"))
      (node (ref "I27") (pin "A") (pinfunction "A_A") (pintype "passive"))
      (node (ref "R138") (pin "2") (pinfunction "2_2") (pintype "passive"))
    )
    (net (code "203") (name "Net-(E19E-O)") (class "Default")
      (node (ref "E19") (pin "10") (pinfunction "O_10") (pintype "open_collector"))
      (node (ref "I26") (pin "A") (pinfunction "A_A") (pintype "passive"))
      (node (ref "R137") (pin "2") (pinfunction "2_2") (pintype "passive"))
    )
    (net (code "204") (name "Net-(E19F-O)") (class "Default")
      (node (ref "E19") (pin "12") (pinfunction "O_12") (pintype "open_collector"))
      (node (ref "I25") (pin "A") (pinfunction "A_A") (pintype "passive"))
      (node (ref "R136") (pin "2") (pinfunction "2_2") (pintype "passive"))
    )
    (net (code "205") (name "Net-(E20A-O)") (class "Default")
      (node (ref "E20") (pin "3") (pinfunction "O_3") (pintype "output"))
      (node (ref "E23") (pin "11") (pinfunction "I_11") (pintype "input"))
    )
    (net (code "206") (name "Net-(E20B-O)") (class "Default")
      (node (ref "E20") (pin "2") (pinfunction "O_2") (pintype "output"))
      (node (ref "E23") (pin "13") (pinfunction "I_13") (pintype "input"))
    )
    (net (code "207") (name "Net-(E21A-I1)") (class "Default")
      (node (ref "D98") (pin "C") (pinfunction "C_C") (pintype "passive"))
      (node (ref "E21") (pin "3") (pinfunction "I1_3") (pintype "input"))
      (node (ref "R111") (pin "2") (pinfunction "2_2") (pintype "passive"))
    )
    (net (code "208") (name "Net-(E21B-I1)") (class "Default")
      (node (ref "D99") (pin "C") (pinfunction "C_C") (pintype "passive"))
      (node (ref "E21") (pin "6") (pinfunction "I1_6") (pintype "input"))
      (node (ref "R113") (pin "2") (pinfunction "2_2") (pintype "passive"))
    )
    (net (code "209") (name "Net-(E21C-I0)") (class "Default")
      (node (ref "D100") (pin "C") (pinfunction "C_C") (pintype "passive"))
      (node (ref "E21") (pin "8") (pinfunction "I0_8") (pintype "input"))
      (node (ref "R115") (pin "2") (pinfunction "2_2") (pintype "passive"))
    )
    (net (code "210") (name "Net-(E21D-I0)") (class "Default")
      (node (ref "D101") (pin "C") (pinfunction "C_C") (pintype "passive"))
      (node (ref "E21") (pin "11") (pinfunction "I0_11") (pintype "input"))
      (node (ref "R117") (pin "2") (pinfunction "2_2") (pintype "passive"))
    )
    (net (code "211") (name "Net-(E22A-I1)") (class "Default")
      (node (ref "D20") (pin "A") (pinfunction "A_A") (pintype "passive"))
      (node (ref "D32") (pin "A") (pinfunction "A_A") (pintype "passive"))
      (node (ref "D44") (pin "A") (pinfunction "A_A") (pintype "passive"))
      (node (ref "E22") (pin "5") (pinfunction "I1_5") (pintype "input"))
      (node (ref "R5") (pin "1") (pinfunction "1_1") (pintype "passive"))
    )
    (net (code "212") (name "Net-(E22A-O)") (class "Default")
      (node (ref "E22") (pin "3") (pinfunction "O_3") (pintype "output"))
      (node (ref "R38") (pin "1") (pinfunction "1_1") (pintype "passive"))
      (node (ref "R39") (pin "1") (pinfunction "1_1") (pintype "passive"))
    )
    (net (code "213") (name "Net-(E22B-I1)") (class "Default")
      (node (ref "D19") (pin "A") (pinfunction "A_A") (pintype "passive"))
      (node (ref "D31") (pin "A") (pinfunction "A_A") (pintype "passive"))
      (node (ref "D43") (pin "A") (pinfunction "A_A") (pintype "passive"))
      (node (ref "E22") (pin "7") (pinfunction "I1_7") (pintype "input"))
      (node (ref "R6") (pin "1") (pinfunction "1_1") (pintype "passive"))
    )
    (net (code "214") (name "Net-(E22B-O)") (class "Default")
      (node (ref "E22") (pin "2") (pinfunction "O_2") (pintype "output"))
      (node (ref "R41") (pin "1") (pinfunction "1_1") (pintype "passive"))
      (node (ref "R42") (pin "1") (pinfunction "1_1") (pintype "passive"))
    )
    (net (code "215") (name "Net-(E22C-I0)") (class "Default")
      (node (ref "D17") (pin "A") (pinfunction "A_A") (pintype "passive"))
      (node (ref "D29") (pin "A") (pinfunction "A_A") (pintype "passive"))
      (node (ref "D41") (pin "A") (pinfunction "A_A") (pintype "passive"))
      (node (ref "E22") (pin "9") (pinfunction "I0_9") (pintype "input"))
      (node (ref "R8") (pin "1") (pinfunction "1_1") (pintype "passive"))
    )
    (net (code "216") (name "Net-(E22C-O)") (class "Default")
      (node (ref "E22") (pin "14") (pinfunction "O_14") (pintype "output"))
      (node (ref "R47") (pin "1") (pinfunction "1_1") (pintype "passive"))
      (node (ref "R48") (pin "1") (pinfunction "1_1") (pintype "passive"))
    )
    (net (code "217") (name "Net-(E22D-I0)") (class "Default")
      (node (ref "D18") (pin "A") (pinfunction "A_A") (pintype "passive"))
      (node (ref "D30") (pin "A") (pinfunction "A_A") (pintype "passive"))
      (node (ref "D42") (pin "A") (pinfunction "A_A") (pintype "passive"))
      (node (ref "E22") (pin "11") (pinfunction "I0_11") (pintype "input"))
      (node (ref "R7") (pin "1") (pinfunction "1_1") (pintype "passive"))
    )
    (net (code "218") (name "Net-(E22D-O)") (class "Default")
      (node (ref "E22") (pin "13") (pinfunction "O_13") (pintype "output"))
      (node (ref "R44") (pin "1") (pinfunction "1_1") (pintype "passive"))
      (node (ref "R45") (pin "1") (pinfunction "1_1") (pintype "passive"))
    )
    (net (code "219") (name "Net-(E23A-I)") (class "Default")
      (node (ref "E23") (pin "1") (pinfunction "I_1") (pintype "input"))
      (node (ref "E24") (pin "14") (pinfunction "O_14") (pintype "output"))
    )
    (net (code "220") (name "Net-(E23A-O)") (class "Default")
      (node (ref "E23") (pin "2") (pinfunction "O_2") (pintype "open_collector"))
      (node (ref "I18") (pin "A") (pinfunction "A_A") (pintype "passive"))
      (node (ref "R129") (pin "2") (pinfunction "2_2") (pintype "passive"))
    )
    (net (code "221") (name "Net-(E23B-I)") (class "Default")
      (node (ref "E23") (pin "3") (pinfunction "I_3") (pintype "input"))
      (node (ref "E24") (pin "13") (pinfunction "O_13") (pintype "output"))
    )
    (net (code "222") (name "Net-(E23B-O)") (class "Default")
      (node (ref "E23") (pin "4") (pinfunction "O_4") (pintype "open_collector"))
      (node (ref "I19") (pin "A") (pinfunction "A_A") (pintype "passive"))
      (node (ref "R130") (pin "2") (pinfunction "2_2") (pintype "passive"))
    )
    (net (code "223") (name "Net-(E23E-O)") (class "Default")
      (node (ref "E23") (pin "10") (pinfunction "O_10") (pintype "open_collector"))
      (node (ref "I21") (pin "A") (pinfunction "A_A") (pintype "passive"))
      (node (ref "R132") (pin "2") (pinfunction "2_2") (pintype "passive"))
    )
    (net (code "224") (name "Net-(E23F-O)") (class "Default")
      (node (ref "E23") (pin "12") (pinfunction "O_12") (pintype "open_collector"))
      (node (ref "I20") (pin "A") (pinfunction "A_A") (pintype "passive"))
      (node (ref "R131") (pin "2") (pinfunction "2_2") (pintype "passive"))
    )
    (net (code "225") (name "Net-(E24A-O)") (class "Default")
      (node (ref "E24") (pin "3") (pinfunction "O_3") (pintype "output"))
      (node (ref "E27") (pin "11") (pinfunction "I_11") (pintype "input"))
    )
    (net (code "226") (name "Net-(E24B-O)") (class "Default")
      (node (ref "E24") (pin "2") (pinfunction "O_2") (pintype "output"))
      (node (ref "E27") (pin "13") (pinfunction "I_13") (pintype "input"))
    )
    (net (code "227") (name "Net-(E25A-I1)") (class "Default")
      (node (ref "D94") (pin "C") (pinfunction "C_C") (pintype "passive"))
      (node (ref "E25") (pin "3") (pinfunction "I1_3") (pintype "input"))
      (node (ref "R103") (pin "2") (pinfunction "2_2") (pintype "passive"))
    )
    (net (code "228") (name "Net-(E25B-I1)") (class "Default")
      (node (ref "D95") (pin "C") (pinfunction "C_C") (pintype "passive"))
      (node (ref "E25") (pin "6") (pinfunction "I1_6") (pintype "input"))
      (node (ref "R105") (pin "2") (pinfunction "2_2") (pintype "passive"))
    )
    (net (code "229") (name "Net-(E25C-I0)") (class "Default")
      (node (ref "D96") (pin "C") (pinfunction "C_C") (pintype "passive"))
      (node (ref "E25") (pin "8") (pinfunction "I0_8") (pintype "input"))
      (node (ref "R107") (pin "2") (pinfunction "2_2") (pintype "passive"))
    )
    (net (code "230") (name "Net-(E25D-I1)") (class "Default")
      (node (ref "D97") (pin "C") (pinfunction "C_C") (pintype "passive"))
      (node (ref "E25") (pin "12") (pinfunction "I1_12") (pintype "input"))
      (node (ref "R109") (pin "2") (pinfunction "2_2") (pintype "passive"))
    )
    (net (code "231") (name "Net-(E26A-I1)") (class "Default")
      (node (ref "D24") (pin "A") (pinfunction "A_A") (pintype "passive"))
      (node (ref "D36") (pin "A") (pinfunction "A_A") (pintype "passive"))
      (node (ref "D48") (pin "A") (pinfunction "A_A") (pintype "passive"))
      (node (ref "E26") (pin "5") (pinfunction "I1_5") (pintype "input"))
      (node (ref "R1") (pin "1") (pinfunction "1_1") (pintype "passive"))
    )
    (net (code "232") (name "Net-(E26A-O)") (class "Default")
      (node (ref "E26") (pin "3") (pinfunction "O_3") (pintype "output"))
      (node (ref "R26") (pin "1") (pinfunction "1_1") (pintype "passive"))
      (node (ref "R27") (pin "1") (pinfunction "1_1") (pintype "passive"))
    )
    (net (code "233") (name "Net-(E26B-I1)") (class "Default")
      (node (ref "D23") (pin "A") (pinfunction "A_A") (pintype "passive"))
      (node (ref "D35") (pin "A") (pinfunction "A_A") (pintype "passive"))
      (node (ref "D47") (pin "A") (pinfunction "A_A") (pintype "passive"))
      (node (ref "E26") (pin "7") (pinfunction "I1_7") (pintype "input"))
      (node (ref "R2") (pin "1") (pinfunction "1_1") (pintype "passive"))
    )
    (net (code "234") (name "Net-(E26B-O)") (class "Default")
      (node (ref "E26") (pin "2") (pinfunction "O_2") (pintype "output"))
      (node (ref "R29") (pin "1") (pinfunction "1_1") (pintype "passive"))
      (node (ref "R30") (pin "1") (pinfunction "1_1") (pintype "passive"))
    )
    (net (code "235") (name "Net-(E26C-I0)") (class "Default")
      (node (ref "D21") (pin "A") (pinfunction "A_A") (pintype "passive"))
      (node (ref "D33") (pin "A") (pinfunction "A_A") (pintype "passive"))
      (node (ref "D45") (pin "A") (pinfunction "A_A") (pintype "passive"))
      (node (ref "E26") (pin "9") (pinfunction "I0_9") (pintype "input"))
      (node (ref "R4") (pin "1") (pinfunction "1_1") (pintype "passive"))
    )
    (net (code "236") (name "Net-(E26C-O)") (class "Default")
      (node (ref "E26") (pin "14") (pinfunction "O_14") (pintype "output"))
      (node (ref "R35") (pin "1") (pinfunction "1_1") (pintype "passive"))
      (node (ref "R36") (pin "1") (pinfunction "1_1") (pintype "passive"))
    )
    (net (code "237") (name "Net-(E26D-I0)") (class "Default")
      (node (ref "D22") (pin "A") (pinfunction "A_A") (pintype "passive"))
      (node (ref "D34") (pin "A") (pinfunction "A_A") (pintype "passive"))
      (node (ref "D46") (pin "A") (pinfunction "A_A") (pintype "passive"))
      (node (ref "E26") (pin "11") (pinfunction "I0_11") (pintype "input"))
      (node (ref "R3") (pin "1") (pinfunction "1_1") (pintype "passive"))
    )
    (net (code "238") (name "Net-(E26D-O)") (class "Default")
      (node (ref "E26") (pin "13") (pinfunction "O_13") (pintype "output"))
      (node (ref "R32") (pin "1") (pinfunction "1_1") (pintype "passive"))
      (node (ref "R33") (pin "1") (pinfunction "1_1") (pintype "passive"))
    )
    (net (code "239") (name "Net-(E27A-I)") (class "Default")
      (node (ref "E27") (pin "1") (pinfunction "I_1") (pintype "input"))
      (node (ref "E28") (pin "3") (pinfunction "O_3") (pintype "output"))
    )
    (net (code "240") (name "Net-(E27A-O)") (class "Default")
      (node (ref "E27") (pin "2") (pinfunction "O_2") (pintype "open_collector"))
      (node (ref "I15") (pin "A") (pinfunction "A_A") (pintype "passive"))
      (node (ref "R141") (pin "2") (pinfunction "2_2") (pintype "passive"))
    )
    (net (code "241") (name "Net-(E27B-I)") (class "Default")
      (node (ref "E27") (pin "3") (pinfunction "I_3") (pintype "input"))
      (node (ref "E28") (pin "14") (pinfunction "O_14") (pintype "output"))
    )
    (net (code "242") (name "Net-(E27B-O)") (class "Default")
      (node (ref "E27") (pin "4") (pinfunction "O_4") (pintype "open_collector"))
      (node (ref "I14") (pin "A") (pinfunction "A_A") (pintype "passive"))
      (node (ref "R140") (pin "2") (pinfunction "2_2") (pintype "passive"))
    )
    (net (code "243") (name "Net-(E27C-I)") (class "Default")
      (node (ref "E27") (pin "5") (pinfunction "I_5") (pintype "input"))
      (node (ref "E28") (pin "13") (pinfunction "O_13") (pintype "output"))
    )
    (net (code "244") (name "Net-(E27C-O)") (class "Default")
      (node (ref "E27") (pin "6") (pinfunction "O_6") (pintype "open_collector"))
      (node (ref "I13") (pin "A") (pinfunction "A_A") (pintype "passive"))
      (node (ref "R139") (pin "2") (pinfunction "2_2") (pintype "passive"))
    )
    (net (code "245") (name "Net-(E27E-O)") (class "Default")
      (node (ref "E27") (pin "10") (pinfunction "O_10") (pintype "open_collector"))
      (node (ref "I17") (pin "A") (pinfunction "A_A") (pintype "passive"))
      (node (ref "R128") (pin "2") (pinfunction "2_2") (pintype "passive"))
    )
    (net (code "246") (name "Net-(E27F-O)") (class "Default")
      (node (ref "E27") (pin "12") (pinfunction "O_12") (pintype "open_collector"))
      (node (ref "I16") (pin "A") (pinfunction "A_A") (pintype "passive"))
      (node (ref "R127") (pin "2") (pinfunction "2_2") (pintype "passive"))
    )
    (net (code "247") (name "Net-(Q1-B)") (class "Default")
      (node (ref "C1") (pin "2") (pinfunction "2_2") (pintype "passive"))
      (node (ref "D1") (pin "C") (pinfunction "C_C") (pintype "passive"))
      (node (ref "Q1") (pin "2") (pinfunction "B_2") (pintype "passive"))
      (node (ref "R27") (pin "2") (pinfunction "2_2") (pintype "passive"))
    )
    (net (code "248") (name "Net-(Q1-C)") (class "Default")
      (node (ref "C1") (pin "1") (pinfunction "1_1") (pintype "passive"))
      (node (ref "I1") (pin "A") (pinfunction "A_A") (pintype "passive"))
      (node (ref "Q1") (pin "3") (pinfunction "C_3") (pintype "passive"))
      (node (ref "R25") (pin "2") (pinfunction "2_2") (pintype "passive"))
    )
    (net (code "249") (name "Net-(Q2-B)") (class "Default")
      (node (ref "C2") (pin "2") (pinfunction "2_2") (pintype "passive"))
      (node (ref "D2") (pin "C") (pinfunction "C_C") (pintype "passive"))
      (node (ref "Q2") (pin "2") (pinfunction "B_2") (pintype "passive"))
      (node (ref "R30") (pin "2") (pinfunction "2_2") (pintype "passive"))
    )
    (net (code "250") (name "Net-(Q2-C)") (class "Default")
      (node (ref "C2") (pin "1") (pinfunction "1_1") (pintype "passive"))
      (node (ref "I2") (pin "A") (pinfunction "A_A") (pintype "passive"))
      (node (ref "Q2") (pin "3") (pinfunction "C_3") (pintype "passive"))
      (node (ref "R28") (pin "2") (pinfunction "2_2") (pintype "passive"))
    )
    (net (code "251") (name "Net-(Q3-B)") (class "Default")
      (node (ref "C3") (pin "2") (pinfunction "2_2") (pintype "passive"))
      (node (ref "D3") (pin "C") (pinfunction "C_C") (pintype "passive"))
      (node (ref "Q3") (pin "2") (pinfunction "B_2") (pintype "passive"))
      (node (ref "R33") (pin "2") (pinfunction "2_2") (pintype "passive"))
    )
    (net (code "252") (name "Net-(Q3-C)") (class "Default")
      (node (ref "C3") (pin "1") (pinfunction "1_1") (pintype "passive"))
      (node (ref "I3") (pin "A") (pinfunction "A_A") (pintype "passive"))
      (node (ref "Q3") (pin "3") (pinfunction "C_3") (pintype "passive"))
      (node (ref "R31") (pin "2") (pinfunction "2_2") (pintype "passive"))
    )
    (net (code "253") (name "Net-(Q4-B)") (class "Default")
      (node (ref "C4") (pin "2") (pinfunction "2_2") (pintype "passive"))
      (node (ref "D4") (pin "C") (pinfunction "C_C") (pintype "passive"))
      (node (ref "Q4") (pin "2") (pinfunction "B_2") (pintype "passive"))
      (node (ref "R36") (pin "2") (pinfunction "2_2") (pintype "passive"))
    )
    (net (code "254") (name "Net-(Q4-C)") (class "Default")
      (node (ref "C4") (pin "1") (pinfunction "1_1") (pintype "passive"))
      (node (ref "I4") (pin "A") (pinfunction "A_A") (pintype "passive"))
      (node (ref "Q4") (pin "3") (pinfunction "C_3") (pintype "passive"))
      (node (ref "R34") (pin "2") (pinfunction "2_2") (pintype "passive"))
    )
    (net (code "255") (name "Net-(Q5-B)") (class "Default")
      (node (ref "C5") (pin "2") (pinfunction "2_2") (pintype "passive"))
      (node (ref "D5") (pin "C") (pinfunction "C_C") (pintype "passive"))
      (node (ref "Q5") (pin "2") (pinfunction "B_2") (pintype "passive"))
      (node (ref "R39") (pin "2") (pinfunction "2_2") (pintype "passive"))
    )
    (net (code "256") (name "Net-(Q5-C)") (class "Default")
      (node (ref "C5") (pin "1") (pinfunction "1_1") (pintype "passive"))
      (node (ref "I5") (pin "A") (pinfunction "A_A") (pintype "passive"))
      (node (ref "Q5") (pin "3") (pinfunction "C_3") (pintype "passive"))
      (node (ref "R37") (pin "2") (pinfunction "2_2") (pintype "passive"))
    )
    (net (code "257") (name "Net-(Q6-B)") (class "Default")
      (node (ref "C6") (pin "2") (pinfunction "2_2") (pintype "passive"))
      (node (ref "D6") (pin "C") (pinfunction "C_C") (pintype "passive"))
      (node (ref "Q6") (pin "2") (pinfunction "B_2") (pintype "passive"))
      (node (ref "R42") (pin "2") (pinfunction "2_2") (pintype "passive"))
    )
    (net (code "258") (name "Net-(Q6-C)") (class "Default")
      (node (ref "C6") (pin "1") (pinfunction "1_1") (pintype "passive"))
      (node (ref "I6") (pin "A") (pinfunction "A_A") (pintype "passive"))
      (node (ref "Q6") (pin "3") (pinfunction "C_3") (pintype "passive"))
      (node (ref "R40") (pin "2") (pinfunction "2_2") (pintype "passive"))
    )
    (net (code "259") (name "Net-(Q7-B)") (class "Default")
      (node (ref "C7") (pin "2") (pinfunction "2_2") (pintype "passive"))
      (node (ref "D7") (pin "C") (pinfunction "C_C") (pintype "passive"))
      (node (ref "Q7") (pin "2") (pinfunction "B_2") (pintype "passive"))
      (node (ref "R45") (pin "2") (pinfunction "2_2") (pintype "passive"))
    )
    (net (code "260") (name "Net-(Q7-C)") (class "Default")
      (node (ref "C7") (pin "1") (pinfunction "1_1") (pintype "passive"))
      (node (ref "I7") (pin "A") (pinfunction "A_A") (pintype "passive"))
      (node (ref "Q7") (pin "3") (pinfunction "C_3") (pintype "passive"))
      (node (ref "R43") (pin "2") (pinfunction "2_2") (pintype "passive"))
    )
    (net (code "261") (name "Net-(Q8-B)") (class "Default")
      (node (ref "C8") (pin "2") (pinfunction "2_2") (pintype "passive"))
      (node (ref "D8") (pin "C") (pinfunction "C_C") (pintype "passive"))
      (node (ref "Q8") (pin "2") (pinfunction "B_2") (pintype "passive"))
      (node (ref "R48") (pin "2") (pinfunction "2_2") (pintype "passive"))
    )
    (net (code "262") (name "Net-(Q8-C)") (class "Default")
      (node (ref "C8") (pin "1") (pinfunction "1_1") (pintype "passive"))
      (node (ref "I8") (pin "A") (pinfunction "A_A") (pintype "passive"))
      (node (ref "Q8") (pin "3") (pinfunction "C_3") (pintype "passive"))
      (node (ref "R46") (pin "2") (pinfunction "2_2") (pintype "passive"))
    )
    (net (code "263") (name "Net-(Q9-B)") (class "Default")
      (node (ref "C9") (pin "2") (pinfunction "2_2") (pintype "passive"))
      (node (ref "D9") (pin "C") (pinfunction "C_C") (pintype "passive"))
      (node (ref "Q9") (pin "2") (pinfunction "B_2") (pintype "passive"))
      (node (ref "R51") (pin "2") (pinfunction "2_2") (pintype "passive"))
    )
    (net (code "264") (name "Net-(Q9-C)") (class "Default")
      (node (ref "C9") (pin "1") (pinfunction "1_1") (pintype "passive"))
      (node (ref "I9") (pin "A") (pinfunction "A_A") (pintype "passive"))
      (node (ref "Q9") (pin "3") (pinfunction "C_3") (pintype "passive"))
      (node (ref "R49") (pin "2") (pinfunction "2_2") (pintype "passive"))
    )
    (net (code "265") (name "Net-(Q10-B)") (class "Default")
      (node (ref "C10") (pin "2") (pinfunction "2_2") (pintype "passive"))
      (node (ref "D10") (pin "C") (pinfunction "C_C") (pintype "passive"))
      (node (ref "Q10") (pin "2") (pinfunction "B_2") (pintype "passive"))
      (node (ref "R54") (pin "2") (pinfunction "2_2") (pintype "passive"))
    )
    (net (code "266") (name "Net-(Q10-C)") (class "Default")
      (node (ref "C10") (pin "1") (pinfunction "1_1") (pintype "passive"))
      (node (ref "I10") (pin "A") (pinfunction "A_A") (pintype "passive"))
      (node (ref "Q10") (pin "3") (pinfunction "C_3") (pintype "passive"))
      (node (ref "R52") (pin "2") (pinfunction "2_2") (pintype "passive"))
    )
    (net (code "267") (name "Net-(Q11-B)") (class "Default")
      (node (ref "C11") (pin "2") (pinfunction "2_2") (pintype "passive"))
      (node (ref "D11") (pin "C") (pinfunction "C_C") (pintype "passive"))
      (node (ref "Q11") (pin "2") (pinfunction "B_2") (pintype "passive"))
      (node (ref "R57") (pin "2") (pinfunction "2_2") (pintype "passive"))
    )
    (net (code "268") (name "Net-(Q11-C)") (class "Default")
      (node (ref "C11") (pin "1") (pinfunction "1_1") (pintype "passive"))
      (node (ref "I11") (pin "A") (pinfunction "A_A") (pintype "passive"))
      (node (ref "Q11") (pin "3") (pinfunction "C_3") (pintype "passive"))
      (node (ref "R55") (pin "2") (pinfunction "2_2") (pintype "passive"))
    )
    (net (code "269") (name "Net-(Q12-B)") (class "Default")
      (node (ref "C12") (pin "2") (pinfunction "2_2") (pintype "passive"))
      (node (ref "D12") (pin "C") (pinfunction "C_C") (pintype "passive"))
      (node (ref "Q12") (pin "2") (pinfunction "B_2") (pintype "passive"))
      (node (ref "R60") (pin "2") (pinfunction "2_2") (pintype "passive"))
    )
    (net (code "270") (name "Net-(Q12-C)") (class "Default")
      (node (ref "C12") (pin "1") (pinfunction "1_1") (pintype "passive"))
      (node (ref "I12") (pin "A") (pinfunction "A_A") (pintype "passive"))
      (node (ref "Q12") (pin "3") (pinfunction "C_3") (pintype "passive"))
      (node (ref "R58") (pin "2") (pinfunction "2_2") (pintype "passive"))
    )
    (net (code "271") (name "Net-(Q13-B)") (class "Default")
      (node (ref "Q13") (pin "2") (pinfunction "B_2") (pintype "passive"))
      (node (ref "R154") (pin "2") (pinfunction "2_2") (pintype "passive"))
    )
    (net (code "272") (name "Net-(Q13-E)") (class "Default")
      (node (ref "Q13") (pin "1") (pinfunction "E_1") (pintype "passive"))
      (node (ref "Q14") (pin "2") (pinfunction "B_2") (pintype "passive"))
      (node (ref "R155") (pin "1") (pinfunction "1_1") (pintype "passive"))
    )
    (net (code "273") (name "Net-(Q14-C)") (class "Default")
      (node (ref "Q14") (pin "3") (pinfunction "C_3") (pintype "passive"))
      (node (ref "Q15") (pin "2") (pinfunction "B_2") (pintype "passive"))
      (node (ref "R157") (pin "2") (pinfunction "2_2") (pintype "passive"))
    )
    (net (code "274") (name "Net-(Q14-E)") (class "Default")
      (node (ref "D116") (pin "A") (pinfunction "A_A") (pintype "passive"))
      (node (ref "Q14") (pin "1") (pinfunction "E_1") (pintype "passive"))
      (node (ref "Q15") (pin "1") (pinfunction "E_1") (pintype "passive"))
      (node (ref "R156") (pin "1") (pinfunction "1_1") (pintype "passive"))
    )
    (net (code "275") (name "Net-(Q15-C)") (class "Default")
      (node (ref "C14") (pin "2") (pinfunction "2_2") (pintype "passive"))
      (node (ref "D118") (pin "C") (pinfunction "C_C") (pintype "passive"))
      (node (ref "D120") (pin "A") (pinfunction "A_A") (pintype "passive"))
      (node (ref "Q15") (pin "3") (pinfunction "C_3") (pintype "passive"))
      (node (ref "R158") (pin "2") (pinfunction "2_2") (pintype "passive"))
    )
    (net (code "276") (name "Net-(Q16-B)") (class "Default")
      (node (ref "Q16") (pin "2") (pinfunction "B_2") (pintype "passive"))
      (node (ref "Q19") (pin "3") (pinfunction "C_3") (pintype "passive"))
      (node (ref "R167") (pin "1") (pinfunction "1_1") (pintype "passive"))
    )
    (net (code "277") (name "Net-(Q16-C)") (class "Default")
      (node (ref "I28") (pin "B") (pinfunction "B_B") (pintype "passive"))
      (node (ref "Q16") (pin "3") (pinfunction "C_3") (pintype "passive"))
      (node (ref "R168") (pin "1") (pinfunction "1_1") (pintype "passive"))
    )
    (net (code "278") (name "Net-(Q16-E)") (class "Default")
      (node (ref "D122") (pin "C") (pinfunction "C_C") (pintype "passive"))
      (node (ref "Q16") (pin "1") (pinfunction "E_1") (pintype "passive"))
      (node (ref "R168") (pin "2") (pinfunction "2_2") (pintype "passive"))
    )
    (net (code "279") (name "Net-(Q17-B)") (class "Default")
      (node (ref "Q17") (pin "2") (pinfunction "B_2") (pintype "passive"))
      (node (ref "R172") (pin "2") (pinfunction "2_2") (pintype "passive"))
    )
    (net (code "280") (name "Net-(Q17-C)") (class "Default")
      (node (ref "Q17") (pin "3") (pinfunction "C_3") (pintype "passive"))
      (node (ref "R163") (pin "1") (pinfunction "1_1") (pintype "passive"))
    )
    (net (code "281") (name "Net-(Q18-B)") (class "Default")
      (node (ref "Q18") (pin "2") (pinfunction "B_2") (pintype "passive"))
      (node (ref "R174") (pin "2") (pinfunction "2_2") (pintype "passive"))
    )
    (net (code "282") (name "Net-(Q18-C)") (class "Default")
      (node (ref "Q18") (pin "3") (pinfunction "C_3") (pintype "passive"))
      (node (ref "R165") (pin "1") (pinfunction "1_1") (pintype "passive"))
    )
    (net (code "283") (name "Net-(Q19-B)") (class "Default")
      (node (ref "Q19") (pin "2") (pinfunction "B_2") (pintype "passive"))
      (node (ref "R166") (pin "2") (pinfunction "2_2") (pintype "passive"))
    )
    (net (code "284") (name "Net-(R87-Pad1)") (class "Default")
      (node (ref "R87") (pin "1") (pinfunction "1_1") (pintype "passive"))
      (node (ref "R88") (pin "1") (pinfunction "1_1") (pintype "passive"))
      (node (ref "S3") (pin "A1") (pinfunction "A1_A1") (pintype "bidirectional"))
    )
    (net (code "285") (name "Net-(R89-Pad1)") (class "Default")
      (node (ref "R89") (pin "1") (pinfunction "1_1") (pintype "passive"))
      (node (ref "R90") (pin "1") (pinfunction "1_1") (pintype "passive"))
      (node (ref "S4") (pin "A1") (pinfunction "A1_A1") (pintype "bidirectional"))
    )
    (net (code "286") (name "Net-(R91-Pad1)") (class "Default")
      (node (ref "R91") (pin "1") (pinfunction "1_1") (pintype "passive"))
      (node (ref "R92") (pin "1") (pinfunction "1_1") (pintype "passive"))
      (node (ref "S5") (pin "A1") (pinfunction "A1_A1") (pintype "bidirectional"))
    )
    (net (code "287") (name "Net-(R93-Pad1)") (class "Default")
      (node (ref "R93") (pin "1") (pinfunction "1_1") (pintype "passive"))
      (node (ref "R94") (pin "1") (pinfunction "1_1") (pintype "passive"))
      (node (ref "S6") (pin "A1") (pinfunction "A1_A1") (pintype "bidirectional"))
    )
    (net (code "288") (name "Net-(R95-Pad1)") (class "Default")
      (node (ref "R95") (pin "1") (pinfunction "1_1") (pintype "passive"))
      (node (ref "R96") (pin "1") (pinfunction "1_1") (pintype "passive"))
      (node (ref "S7") (pin "A2") (pinfunction "A2_A2") (pintype "bidirectional"))
    )
    (net (code "289") (name "Net-(R97-Pad1)") (class "Default")
      (node (ref "R97") (pin "1") (pinfunction "1_1") (pintype "passive"))
      (node (ref "R98") (pin "1") (pinfunction "1_1") (pintype "passive"))
      (node (ref "S8") (pin "A1") (pinfunction "A1_A1") (pintype "bidirectional"))
    )
    (net (code "290") (name "Net-(S2-A1)") (class "Default")
      (node (ref "R85") (pin "1") (pinfunction "1_1") (pintype "passive"))
      (node (ref "R86") (pin "1") (pinfunction "1_1") (pintype "passive"))
      (node (ref "S2") (pin "L1") (pinfunction "A1_L1") (pintype "bidirectional"))
      (node (ref "S2") (pin "R1") (pinfunction "B1_R1") (pintype "bidirectional"))
    )
    (net (code "291") (name "Net-(S9-A1)") (class "Default")
      (node (ref "R100") (pin "1") (pinfunction "1_1") (pintype "passive"))
      (node (ref "R99") (pin "1") (pinfunction "1_1") (pintype "passive"))
      (node (ref "S9") (pin "L1") (pinfunction "A1_L1") (pintype "bidirectional"))
      (node (ref "S9") (pin "R1") (pinfunction "B1_R1") (pintype "bidirectional"))
    )
    (net (code "292") (name "Net-(S10-A1)") (class "Default")
      (node (ref "R101") (pin "1") (pinfunction "1_1") (pintype "passive"))
      (node (ref "R102") (pin "1") (pinfunction "1_1") (pintype "passive"))
      (node (ref "S10") (pin "L1") (pinfunction "A1_L1") (pintype "bidirectional"))
      (node (ref "S10") (pin "R1") (pinfunction "B1_R1") (pintype "bidirectional"))
    )
    (net (code "293") (name "Net-(S11-A1)") (class "Default")
      (node (ref "R103") (pin "1") (pinfunction "1_1") (pintype "passive"))
      (node (ref "R104") (pin "1") (pinfunction "1_1") (pintype "passive"))
      (node (ref "S11") (pin "L1") (pinfunction "A1_L1") (pintype "bidirectional"))
      (node (ref "S11") (pin "R1") (pinfunction "B1_R1") (pintype "bidirectional"))
    )
    (net (code "294") (name "Net-(S12-A1)") (class "Default")
      (node (ref "R105") (pin "1") (pinfunction "1_1") (pintype "passive"))
      (node (ref "R106") (pin "1") (pinfunction "1_1") (pintype "passive"))
      (node (ref "S12") (pin "L1") (pinfunction "A1_L1") (pintype "bidirectional"))
      (node (ref "S12") (pin "R1") (pinfunction "B1_R1") (pintype "bidirectional"))
    )
    (net (code "295") (name "Net-(S13-A1)") (class "Default")
      (node (ref "R107") (pin "1") (pinfunction "1_1") (pintype "passive"))
      (node (ref "R108") (pin "1") (pinfunction "1_1") (pintype "passive"))
      (node (ref "S13") (pin "L1") (pinfunction "A1_L1") (pintype "bidirectional"))
      (node (ref "S13") (pin "R1") (pinfunction "B1_R1") (pintype "bidirectional"))
    )
    (net (code "296") (name "Net-(S14-A1)") (class "Default")
      (node (ref "R109") (pin "1") (pinfunction "1_1") (pintype "passive"))
      (node (ref "R110") (pin "1") (pinfunction "1_1") (pintype "passive"))
      (node (ref "S14") (pin "L1") (pinfunction "A1_L1") (pintype "bidirectional"))
      (node (ref "S14") (pin "R1") (pinfunction "B1_R1") (pintype "bidirectional"))
    )
    (net (code "297") (name "Net-(S15-A1)") (class "Default")
      (node (ref "R111") (pin "1") (pinfunction "1_1") (pintype "passive"))
      (node (ref "R112") (pin "1") (pinfunction "1_1") (pintype "passive"))
      (node (ref "S15") (pin "L1") (pinfunction "A1_L1") (pintype "bidirectional"))
      (node (ref "S15") (pin "R1") (pinfunction "B1_R1") (pintype "bidirectional"))
    )
    (net (code "298") (name "Net-(S16-A1)") (class "Default")
      (node (ref "R113") (pin "1") (pinfunction "1_1") (pintype "passive"))
      (node (ref "R114") (pin "1") (pinfunction "1_1") (pintype "passive"))
      (node (ref "S16") (pin "L1") (pinfunction "A1_L1") (pintype "bidirectional"))
      (node (ref "S16") (pin "R1") (pinfunction "B1_R1") (pintype "bidirectional"))
    )
    (net (code "299") (name "Net-(S17-A1)") (class "Default")
      (node (ref "R115") (pin "1") (pinfunction "1_1") (pintype "passive"))
      (node (ref "R116") (pin "1") (pinfunction "1_1") (pintype "passive"))
      (node (ref "S17") (pin "L1") (pinfunction "A1_L1") (pintype "bidirectional"))
      (node (ref "S17") (pin "R1") (pinfunction "B1_R1") (pintype "bidirectional"))
    )
    (net (code "300") (name "Net-(S18-A1)") (class "Default")
      (node (ref "R117") (pin "1") (pinfunction "1_1") (pintype "passive"))
      (node (ref "R118") (pin "1") (pinfunction "1_1") (pintype "passive"))
      (node (ref "S18") (pin "L1") (pinfunction "A1_L1") (pintype "bidirectional"))
      (node (ref "S18") (pin "R1") (pinfunction "B1_R1") (pintype "bidirectional"))
    )
    (net (code "301") (name "Net-(S19-A1)") (class "Default")
      (node (ref "R119") (pin "1") (pinfunction "1_1") (pintype "passive"))
      (node (ref "R120") (pin "1") (pinfunction "1_1") (pintype "passive"))
      (node (ref "S19") (pin "L1") (pinfunction "A1_L1") (pintype "bidirectional"))
      (node (ref "S19") (pin "R1") (pinfunction "B1_R1") (pintype "bidirectional"))
    )
    (net (code "302") (name "Net-(S20-A1)") (class "Default")
      (node (ref "R121") (pin "1") (pinfunction "1_1") (pintype "passive"))
      (node (ref "R122") (pin "1") (pinfunction "1_1") (pintype "passive"))
      (node (ref "S20") (pin "L1") (pinfunction "A1_L1") (pintype "bidirectional"))
      (node (ref "S20") (pin "R1") (pinfunction "B1_R1") (pintype "bidirectional"))
    )
    (net (code "303") (name "Net-(S21-A1)") (class "Default")
      (node (ref "R123") (pin "1") (pinfunction "1_1") (pintype "passive"))
      (node (ref "R124") (pin "1") (pinfunction "1_1") (pintype "passive"))
      (node (ref "S21") (pin "L1") (pinfunction "A1_L1") (pintype "bidirectional"))
      (node (ref "S21") (pin "R1") (pinfunction "B1_R1") (pintype "bidirectional"))
    )
    (net (code "304") (name "Net-(S22-A1)") (class "Default")
      (node (ref "R125") (pin "1") (pinfunction "1_1") (pintype "passive"))
      (node (ref "R126") (pin "1") (pinfunction "1_1") (pintype "passive"))
      (node (ref "S22") (pin "L1") (pinfunction "A1_L1") (pintype "bidirectional"))
      (node (ref "S22") (pin "R1") (pinfunction "B1_R1") (pintype "bidirectional"))
    )
    (net (code "305") (name "PAN_LOCK") (class "Default")
      (node (ref "BLUE") (pin "1") (pinfunction "1_1") (pintype "passive"))
      (node (ref "S10") (pin "L2") (pinfunction "A2_L2") (pintype "bidirectional"))
      (node (ref "S10") (pin "R2") (pinfunction "B2_R2") (pintype "bidirectional"))
      (node (ref "S2") (pin "L2") (pinfunction "A2_L2") (pintype "bidirectional"))
      (node (ref "S2") (pin "R2") (pinfunction "B2_R2") (pintype "bidirectional"))
      (node (ref "S3") (pin "A2") (pinfunction "A2_A2") (pintype "bidirectional"))
      (node (ref "S4") (pin "A2") (pinfunction "A2_A2") (pintype "bidirectional"))
      (node (ref "S5") (pin "A2") (pinfunction "A2_A2") (pintype "bidirectional"))
      (node (ref "S6") (pin "A2") (pinfunction "A2_A2") (pintype "bidirectional"))
      (node (ref "S7") (pin "A1") (pinfunction "A1_A1") (pintype "bidirectional"))
      (node (ref "S8") (pin "A2") (pinfunction "A2_A2") (pintype "bidirectional"))
      (node (ref "S9") (pin "L2") (pinfunction "A2_L2") (pintype "bidirectional"))
      (node (ref "S9") (pin "R2") (pinfunction "B2_R2") (pintype "bidirectional"))
    )
    (net (code "306") (name "PULSE_LA") (class "Default")
      (node (ref "Q17") (pin "1") (pinfunction "E_1") (pintype "passive"))
      (node (ref "U$2") (pin "DR2") (pinfunction "1_DR2") (pintype "bidirectional"))
    )
    (net (code "307") (name "SSTP") (class "Default")
      (node (ref "D92") (pin "C") (pinfunction "C_C") (pintype "passive"))
      (node (ref "E6") (pin "5") (pinfunction "I1_5") (pintype "input"))
      (node (ref "R99") (pin "2") (pinfunction "2_2") (pintype "passive"))
    )
    (net (code "308") (name "STATE_EN") (class "Default")
      (node (ref "R143") (pin "1") (pinfunction "1_1") (pintype "passive"))
      (node (ref "R61") (pin "2") (pinfunction "2_2") (pintype "passive"))
      (node (ref "R63") (pin "2") (pinfunction "2_2") (pintype "passive"))
      (node (ref "R65") (pin "2") (pinfunction "2_2") (pintype "passive"))
      (node (ref "R67") (pin "2") (pinfunction "2_2") (pintype "passive"))
      (node (ref "R69") (pin "2") (pinfunction "2_2") (pintype "passive"))
      (node (ref "R71") (pin "2") (pinfunction "2_2") (pintype "passive"))
      (node (ref "R73") (pin "2") (pinfunction "2_2") (pintype "passive"))
      (node (ref "R75") (pin "2") (pinfunction "2_2") (pintype "passive"))
      (node (ref "R77") (pin "2") (pinfunction "2_2") (pintype "passive"))
      (node (ref "R79") (pin "2") (pinfunction "2_2") (pintype "passive"))
      (node (ref "R81") (pin "2") (pinfunction "2_2") (pintype "passive"))
      (node (ref "R83") (pin "2") (pinfunction "2_2") (pintype "passive"))
      (node (ref "S1") (pin "6") (pinfunction "6_6") (pintype "passive"))
    )
    (net (code "309") (name "STATUS_EN") (class "Default")
      (node (ref "D106") (pin "C") (pinfunction "C_C") (pintype "passive"))
      (node (ref "R148") (pin "1") (pinfunction "1_1") (pintype "passive"))
      (node (ref "S1") (pin "5") (pinfunction "5_5") (pintype "passive"))
    )
    (net (code "310") (name "STOP") (class "Default")
      (node (ref "E4") (pin "13") (pinfunction "O_13") (pintype "open_collector"))
      (node (ref "U$2") (pin "DS2") (pinfunction "1_DS2") (pintype "bidirectional"))
    )
    (net (code "311") (name "SWITCH") (class "Default")
      (node (ref "D81") (pin "A") (pinfunction "A_A") (pintype "passive"))
      (node (ref "D85") (pin "C") (pinfunction "C_C") (pintype "passive"))
      (node (ref "R85") (pin "2") (pinfunction "2_2") (pintype "passive"))
      (node (ref "R86") (pin "2") (pinfunction "2_2") (pintype "passive"))
      (node (ref "U$2") (pin "DV2") (pinfunction "1_DV2") (pintype "bidirectional"))
    )
    (net (code "312") (name "TP4") (class "Default")
      (node (ref "E13") (pin "10") (pinfunction "I1_10") (pintype "input"))
      (node (ref "E13") (pin "9") (pinfunction "I0_9") (pintype "input"))
      (node (ref "U$2") (pin "CJ2") (pinfunction "1_CJ2") (pintype "bidirectional"))
    )
    (net (code "313") (name "TS1") (class "Default")
      (node (ref "E2") (pin "7") (pinfunction "I1_7") (pintype "input"))
      (node (ref "U$2") (pin "CK2") (pinfunction "1_CK2") (pintype "bidirectional"))
    )
    (net (code "314") (name "TS3") (class "Default")
      (node (ref "E2") (pin "5") (pinfunction "I1_5") (pintype "input"))
      (node (ref "U$2") (pin "CM2") (pinfunction "1_CM2") (pintype "bidirectional"))
    )
    (net (code "315") (name "TS4") (class "Default")
      (node (ref "E11") (pin "11") (pinfunction "I0_11") (pintype "input"))
      (node (ref "U$2") (pin "CP2") (pinfunction "1_CP2") (pintype "bidirectional"))
    )
    (net (code "316") (name "U_MODE") (class "Default")
      (node (ref "E13") (pin "4") (pinfunction "I0_4") (pintype "input"))
      (node (ref "U$2") (pin "DM2") (pinfunction "1_DM2") (pintype "bidirectional"))
    )
    (net (code "317") (name "VCC") (class "Default")
      (node (ref "C18") (pin "+") (pinfunction "+_+") (pintype "passive"))
      (node (ref "C19") (pin "+") (pinfunction "+_+") (pintype "passive"))
      (node (ref "C20") (pin "+") (pinfunction "+_+") (pintype "passive"))
      (node (ref "C22") (pin "1") (pinfunction "1_1") (pintype "passive"))
      (node (ref "C23") (pin "1") (pinfunction "1_1") (pintype "passive"))
      (node (ref "C24") (pin "1") (pinfunction "1_1") (pintype "passive"))
      (node (ref "C25") (pin "1") (pinfunction "1_1") (pintype "passive"))
      (node (ref "C26") (pin "1") (pinfunction "1_1") (pintype "passive"))
      (node (ref "C27") (pin "1") (pinfunction "1_1") (pintype "passive"))
      (node (ref "C28") (pin "1") (pinfunction "1_1") (pintype "passive"))
      (node (ref "C29") (pin "1") (pinfunction "1_1") (pintype "passive"))
      (node (ref "C30") (pin "1") (pinfunction "1_1") (pintype "passive"))
      (node (ref "C31") (pin "1") (pinfunction "1_1") (pintype "passive"))
      (node (ref "C32") (pin "1") (pinfunction "1_1") (pintype "passive"))
      (node (ref "C33") (pin "1") (pinfunction "1_1") (pintype "passive"))
      (node (ref "C34") (pin "1") (pinfunction "1_1") (pintype "passive"))
      (node (ref "C35") (pin "1") (pinfunction "1_1") (pintype "passive"))
      (node (ref "C36") (pin "1") (pinfunction "1_1") (pintype "passive"))
      (node (ref "C37") (pin "1") (pinfunction "1_1") (pintype "passive"))
      (node (ref "C38") (pin "1") (pinfunction "1_1") (pintype "passive"))
      (node (ref "C39") (pin "1") (pinfunction "1_1") (pintype "passive"))
      (node (ref "R1") (pin "2") (pinfunction "2_2") (pintype "passive"))
      (node (ref "R10") (pin "2") (pinfunction "2_2") (pintype "passive"))
      (node (ref "R100") (pin "2") (pinfunction "2_2") (pintype "passive"))
      (node (ref "R102") (pin "2") (pinfunction "2_2") (pintype "passive"))
      (node (ref "R104") (pin "2") (pinfunction "2_2") (pintype "passive"))
      (node (ref "R106") (pin "2") (pinfunction "2_2") (pintype "passive"))
      (node (ref "R108") (pin "2") (pinfunction "2_2") (pintype "passive"))
      (node (ref "R11") (pin "2") (pinfunction "2_2") (pintype "passive"))
      (node (ref "R110") (pin "2") (pinfunction "2_2") (pintype "passive"))
      (node (ref "R112") (pin "2") (pinfunction "2_2") (pintype "passive"))
      (node (ref "R114") (pin "2") (pinfunction "2_2") (pintype "passive"))
      (node (ref "R116") (pin "2") (pinfunction "2_2") (pintype "passive"))
      (node (ref "R118") (pin "2") (pinfunction "2_2") (pintype "passive"))
      (node (ref "R12") (pin "2") (pinfunction "2_2") (pintype "passive"))
      (node (ref "R120") (pin "2") (pinfunction "2_2") (pintype "passive"))
      (node (ref "R122") (pin "2") (pinfunction "2_2") (pintype "passive"))
      (node (ref "R124") (pin "2") (pinfunction "2_2") (pintype "passive"))
      (node (ref "R126") (pin "2") (pinfunction "2_2") (pintype "passive"))
      (node (ref "R142") (pin "2") (pinfunction "2_2") (pintype "passive"))
      (node (ref "R143") (pin "2") (pinfunction "2_2") (pintype "passive"))
      (node (ref "R144") (pin "2") (pinfunction "2_2") (pintype "passive"))
      (node (ref "R145") (pin "2") (pinfunction "2_2") (pintype "passive"))
      (node (ref "R146") (pin "2") (pinfunction "2_2") (pintype "passive"))
      (node (ref "R147") (pin "2") (pinfunction "2_2") (pintype "passive"))
      (node (ref "R151") (pin "2") (pinfunction "2_2") (pintype "passive"))
      (node (ref "R152") (pin "2") (pinfunction "2_2") (pintype "passive"))
      (node (ref "R155") (pin "2") (pinfunction "2_2") (pintype "passive"))
      (node (ref "R156") (pin "2") (pinfunction "2_2") (pintype "passive"))
      (node (ref "R161") (pin "2") (pinfunction "2_2") (pintype "passive"))
      (node (ref "R162") (pin "2") (pinfunction "2_2") (pintype "passive"))
      (node (ref "R163") (pin "2") (pinfunction "2_2") (pintype "passive"))
      (node (ref "R164") (pin "2") (pinfunction "2_2") (pintype "passive"))
      (node (ref "R165") (pin "2") (pinfunction "2_2") (pintype "passive"))
      (node (ref "R167") (pin "2") (pinfunction "2_2") (pintype "passive"))
      (node (ref "R169") (pin "1") (pinfunction "1_1") (pintype "passive"))
      (node (ref "R170") (pin "2") (pinfunction "2_2") (pintype "passive"))
      (node (ref "R175") (pin "2") (pinfunction "2_2") (pintype "passive"))
      (node (ref "R2") (pin "2") (pinfunction "2_2") (pintype "passive"))
      (node (ref "R3") (pin "2") (pinfunction "2_2") (pintype "passive"))
      (node (ref "R4") (pin "2") (pinfunction "2_2") (pintype "passive"))
      (node (ref "R5") (pin "2") (pinfunction "2_2") (pintype "passive"))
      (node (ref "R6") (pin "2") (pinfunction "2_2") (pintype "passive"))
      (node (ref "R7") (pin "2") (pinfunction "2_2") (pintype "passive"))
      (node (ref "R8") (pin "2") (pinfunction "2_2") (pintype "passive"))
      (node (ref "R88") (pin "2") (pinfunction "2_2") (pintype "passive"))
      (node (ref "R9") (pin "2") (pinfunction "2_2") (pintype "passive"))
      (node (ref "R90") (pin "2") (pinfunction "2_2") (pintype "passive"))
      (node (ref "R92") (pin "2") (pinfunction "2_2") (pintype "passive"))
      (node (ref "R94") (pin "2") (pinfunction "2_2") (pintype "passive"))
      (node (ref "R96") (pin "2") (pinfunction "2_2") (pintype "passive"))
      (node (ref "R98") (pin "2") (pinfunction "2_2") (pintype "passive"))
      (node (ref "U$2") (pin "AA2") (pinfunction "1_AA2") (pintype "bidirectional"))
      (node (ref "U$2") (pin "BA2") (pinfunction "1_BA2") (pintype "bidirectional"))
      (node (ref "U$2") (pin "CA2") (pinfunction "1_CA2") (pintype "bidirectional"))
    )
    (net (code "318") (name "WILL_START") (class "Default")
      (node (ref "E10") (pin "2") (pinfunction "O_2") (pintype "output"))
      (node (ref "E11") (pin "7") (pinfunction "I1_7") (pintype "input"))
      (node (ref "E12") (pin "13") (pinfunction "I1_13") (pintype "input"))
      (node (ref "R153") (pin "1") (pinfunction "1_1") (pintype "passive"))
      (node (ref "R175") (pin "1") (pinfunction "1_1") (pintype "passive"))
    )
    (net (code "319") (name "unconnected-(S2-A3-PadL3)") (class "Default")
      (node (ref "S2") (pin "L3") (pinfunction "A3_L3") (pintype "bidirectional"))
    )
    (net (code "320") (name "unconnected-(S2-B3-PadR3)") (class "Default")
      (node (ref "S2") (pin "R3") (pinfunction "B3_R3") (pintype "bidirectional"))
    )
    (net (code "321") (name "unconnected-(S3-PadA3)") (class "Default")
      (node (ref "S3") (pin "A3") (pinfunction "A3_A3") (pintype "bidirectional"))
    )
    (net (code "322") (name "unconnected-(S4-PadA3)") (class "Default")
      (node (ref "S4") (pin "A3") (pinfunction "A3_A3") (pintype "bidirectional"))
    )
    (net (code "323") (name "unconnected-(S5-PadA3)") (class "Default")
      (node (ref "S5") (pin "A3") (pinfunction "A3_A3") (pintype "bidirectional"))
    )
    (net (code "324") (name "unconnected-(S6-PadA3)") (class "Default")
      (node (ref "S6") (pin "A3") (pinfunction "A3_A3") (pintype "bidirectional"))
    )
    (net (code "325") (name "unconnected-(S7-PadA3)") (class "Default")
      (node (ref "S7") (pin "A3") (pinfunction "A3_A3") (pintype "bidirectional"))
    )
    (net (code "326") (name "unconnected-(S8-PadA3)") (class "Default")
      (node (ref "S8") (pin "A3") (pinfunction "A3_A3") (pintype "bidirectional"))
    )
    (net (code "327") (name "unconnected-(S9-A3-PadL3)") (class "Default")
      (node (ref "S9") (pin "L3") (pinfunction "A3_L3") (pintype "bidirectional"))
    )
    (net (code "328") (name "unconnected-(S9-B3-PadR3)") (class "Default")
      (node (ref "S9") (pin "R3") (pinfunction "B3_R3") (pintype "bidirectional"))
    )
    (net (code "329") (name "unconnected-(S10-A3-PadL3)") (class "Default")
      (node (ref "S10") (pin "L3") (pinfunction "A3_L3") (pintype "bidirectional"))
    )
    (net (code "330") (name "unconnected-(S10-B3-PadR3)") (class "Default")
      (node (ref "S10") (pin "R3") (pinfunction "B3_R3") (pintype "bidirectional"))
    )
    (net (code "331") (name "unconnected-(S11-A3-PadL3)") (class "Default")
      (node (ref "S11") (pin "L3") (pinfunction "A3_L3") (pintype "bidirectional"))
    )
    (net (code "332") (name "unconnected-(S11-B3-PadR3)") (class "Default")
      (node (ref "S11") (pin "R3") (pinfunction "B3_R3") (pintype "bidirectional"))
    )
    (net (code "333") (name "unconnected-(S12-A3-PadL3)") (class "Default")
      (node (ref "S12") (pin "L3") (pinfunction "A3_L3") (pintype "bidirectional"))
    )
    (net (code "334") (name "unconnected-(S12-B3-PadR3)") (class "Default")
      (node (ref "S12") (pin "R3") (pinfunction "B3_R3") (pintype "bidirectional"))
    )
    (net (code "335") (name "unconnected-(S13-A3-PadL3)") (class "Default")
      (node (ref "S13") (pin "L3") (pinfunction "A3_L3") (pintype "bidirectional"))
    )
    (net (code "336") (name "unconnected-(S13-B3-PadR3)") (class "Default")
      (node (ref "S13") (pin "R3") (pinfunction "B3_R3") (pintype "bidirectional"))
    )
    (net (code "337") (name "unconnected-(S14-A3-PadL3)") (class "Default")
      (node (ref "S14") (pin "L3") (pinfunction "A3_L3") (pintype "bidirectional"))
    )
    (net (code "338") (name "unconnected-(S14-B3-PadR3)") (class "Default")
      (node (ref "S14") (pin "R3") (pinfunction "B3_R3") (pintype "bidirectional"))
    )
    (net (code "339") (name "unconnected-(S15-A3-PadL3)") (class "Default")
      (node (ref "S15") (pin "L3") (pinfunction "A3_L3") (pintype "bidirectional"))
    )
    (net (code "340") (name "unconnected-(S15-B3-PadR3)") (class "Default")
      (node (ref "S15") (pin "R3") (pinfunction "B3_R3") (pintype "bidirectional"))
    )
    (net (code "341") (name "unconnected-(S16-A3-PadL3)") (class "Default")
      (node (ref "S16") (pin "L3") (pinfunction "A3_L3") (pintype "bidirectional"))
    )
    (net (code "342") (name "unconnected-(S16-B3-PadR3)") (class "Default")
      (node (ref "S16") (pin "R3") (pinfunction "B3_R3") (pintype "bidirectional"))
    )
    (net (code "343") (name "unconnected-(S17-A3-PadL3)") (class "Default")
      (node (ref "S17") (pin "L3") (pinfunction "A3_L3") (pintype "bidirectional"))
    )
    (net (code "344") (name "unconnected-(S17-B3-PadR3)") (class "Default")
      (node (ref "S17") (pin "R3") (pinfunction "B3_R3") (pintype "bidirectional"))
    )
    (net (code "345") (name "unconnected-(S18-A3-PadL3)") (class "Default")
      (node (ref "S18") (pin "L3") (pinfunction "A3_L3") (pintype "bidirectional"))
    )
    (net (code "346") (name "unconnected-(S18-B3-PadR3)") (class "Default")
      (node (ref "S18") (pin "R3") (pinfunction "B3_R3") (pintype "bidirectional"))
    )
    (net (code "347") (name "unconnected-(S19-A3-PadL3)") (class "Default")
      (node (ref "S19") (pin "L3") (pinfunction "A3_L3") (pintype "bidirectional"))
    )
    (net (code "348") (name "unconnected-(S19-B3-PadR3)") (class "Default")
      (node (ref "S19") (pin "R3") (pinfunction "B3_R3") (pintype "bidirectional"))
    )
    (net (code "349") (name "unconnected-(S20-A3-PadL3)") (class "Default")
      (node (ref "S20") (pin "L3") (pinfunction "A3_L3") (pintype "bidirectional"))
    )
    (net (code "350") (name "unconnected-(S20-B3-PadR3)") (class "Default")
      (node (ref "S20") (pin "R3") (pinfunction "B3_R3") (pintype "bidirectional"))
    )
    (net (code "351") (name "unconnected-(S21-A3-PadL3)") (class "Default")
      (node (ref "S21") (pin "L3") (pinfunction "A3_L3") (pintype "bidirectional"))
    )
    (net (code "352") (name "unconnected-(S21-B3-PadR3)") (class "Default")
      (node (ref "S21") (pin "R3") (pinfunction "B3_R3") (pintype "bidirectional"))
    )
    (net (code "353") (name "unconnected-(S22-A3-PadL3)") (class "Default")
      (node (ref "S22") (pin "L3") (pinfunction "A3_L3") (pintype "bidirectional"))
    )
    (net (code "354") (name "unconnected-(S22-B3-PadR3)") (class "Default")
      (node (ref "S22") (pin "R3") (pinfunction "B3_R3") (pintype "bidirectional"))
    )
    (net (code "355") (name "~{RUN}") (class "Default")
      (node (ref "E11") (pin "6") (pinfunction "I0_6") (pintype "input"))
      (node (ref "E9") (pin "1") (pinfunction "I_1") (pintype "input"))
      (node (ref "U$2") (pin "BU2") (pinfunction "1_BU2") (pintype "bidirectional"))
    )
  )
)
